# ntc08.net
KiCad netlist of a schematic drawn in EAGLE
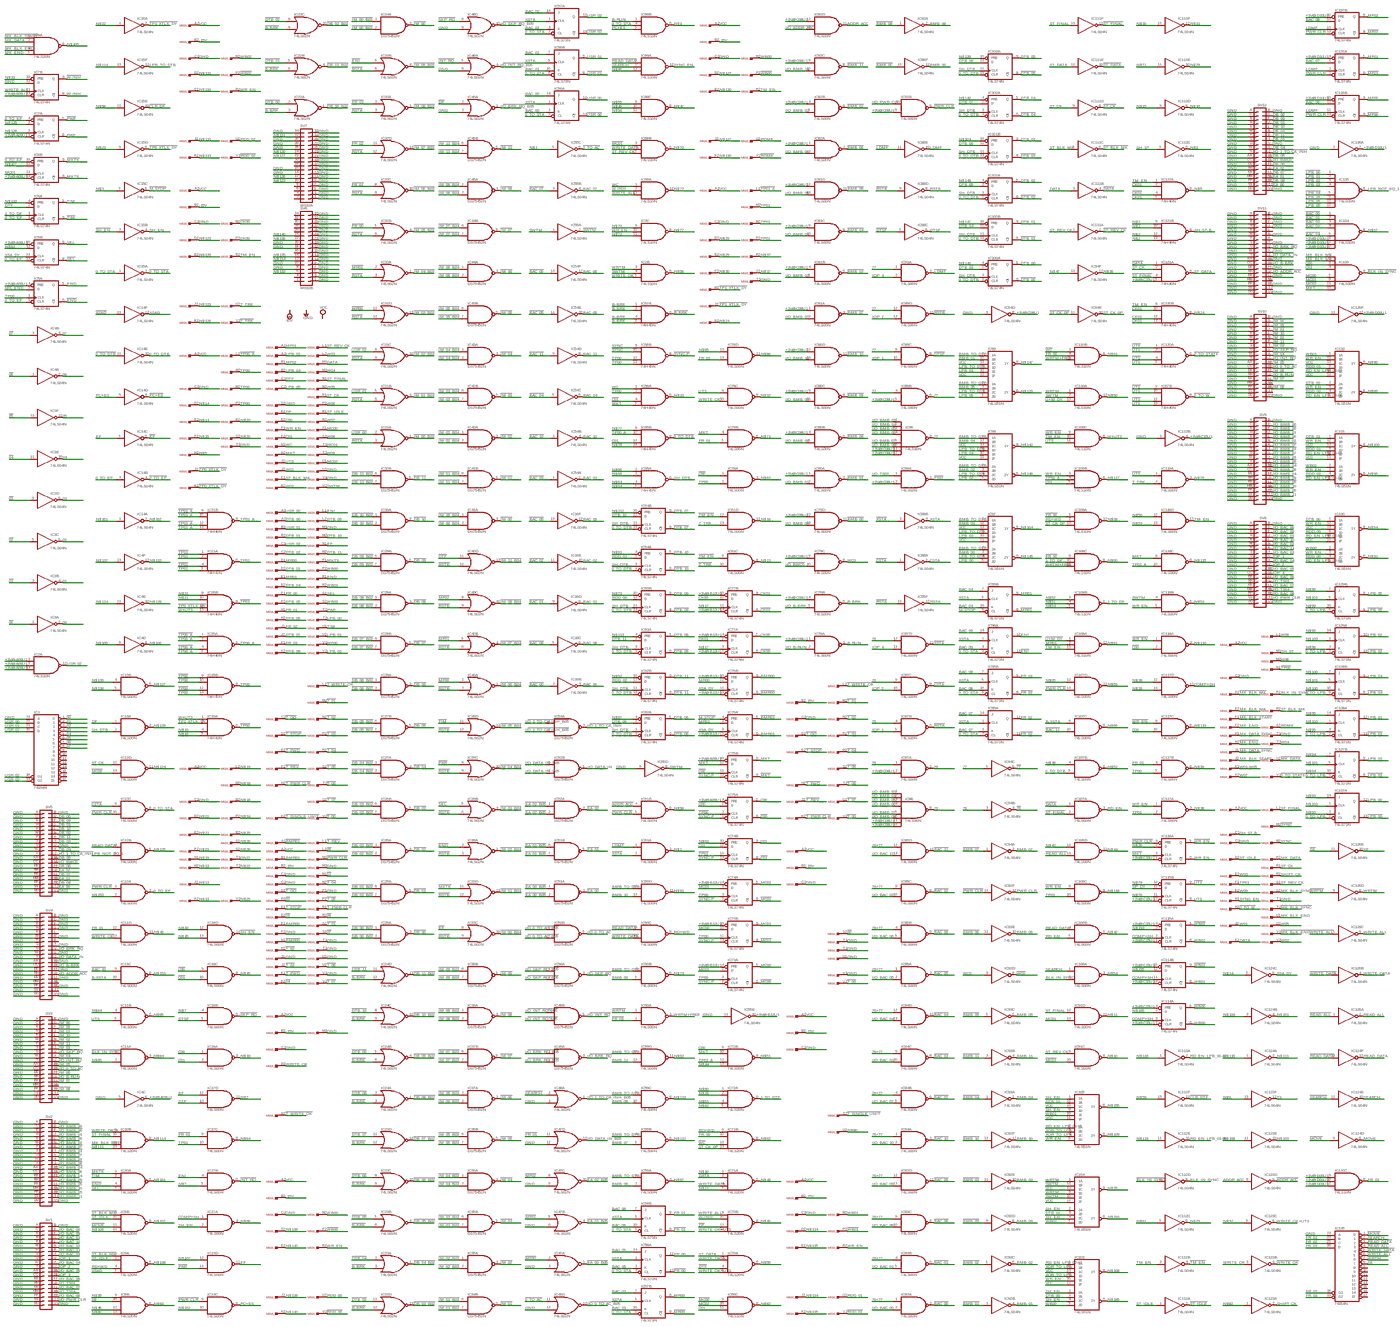
[diagram p0: schematic, sheet 1, overview]
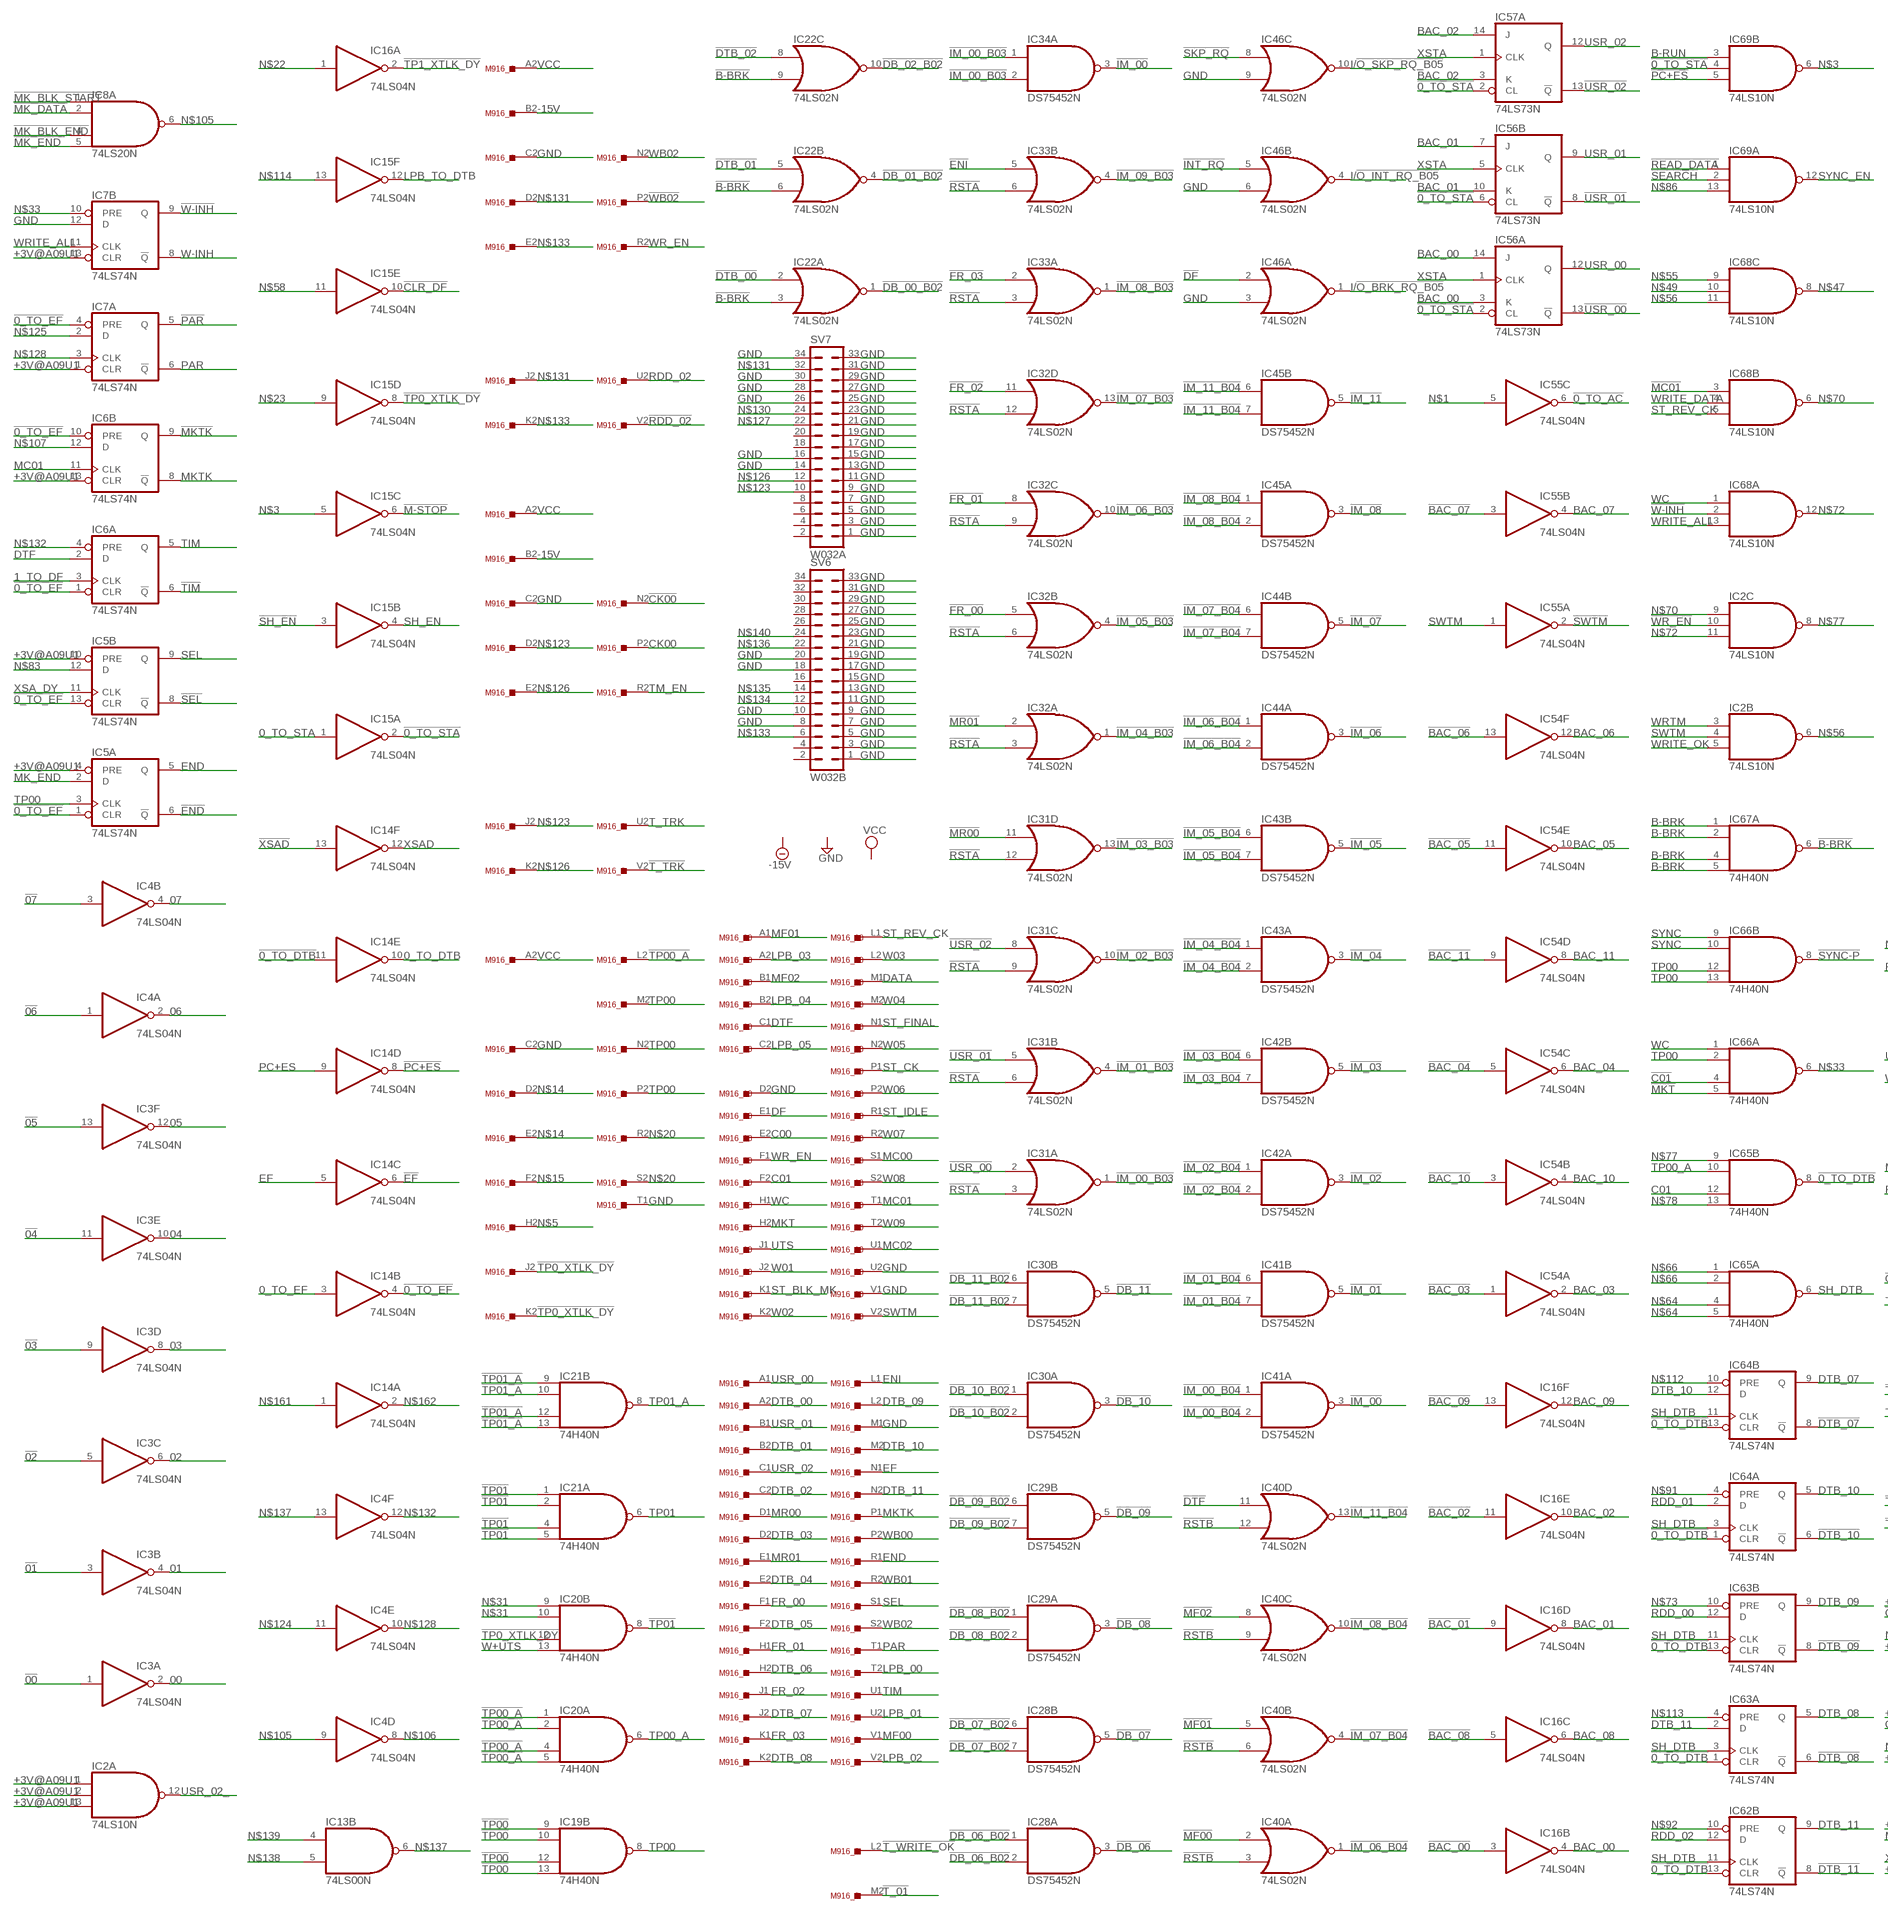
[diagram p1: schematic, sheet 1, part 1 of 4]
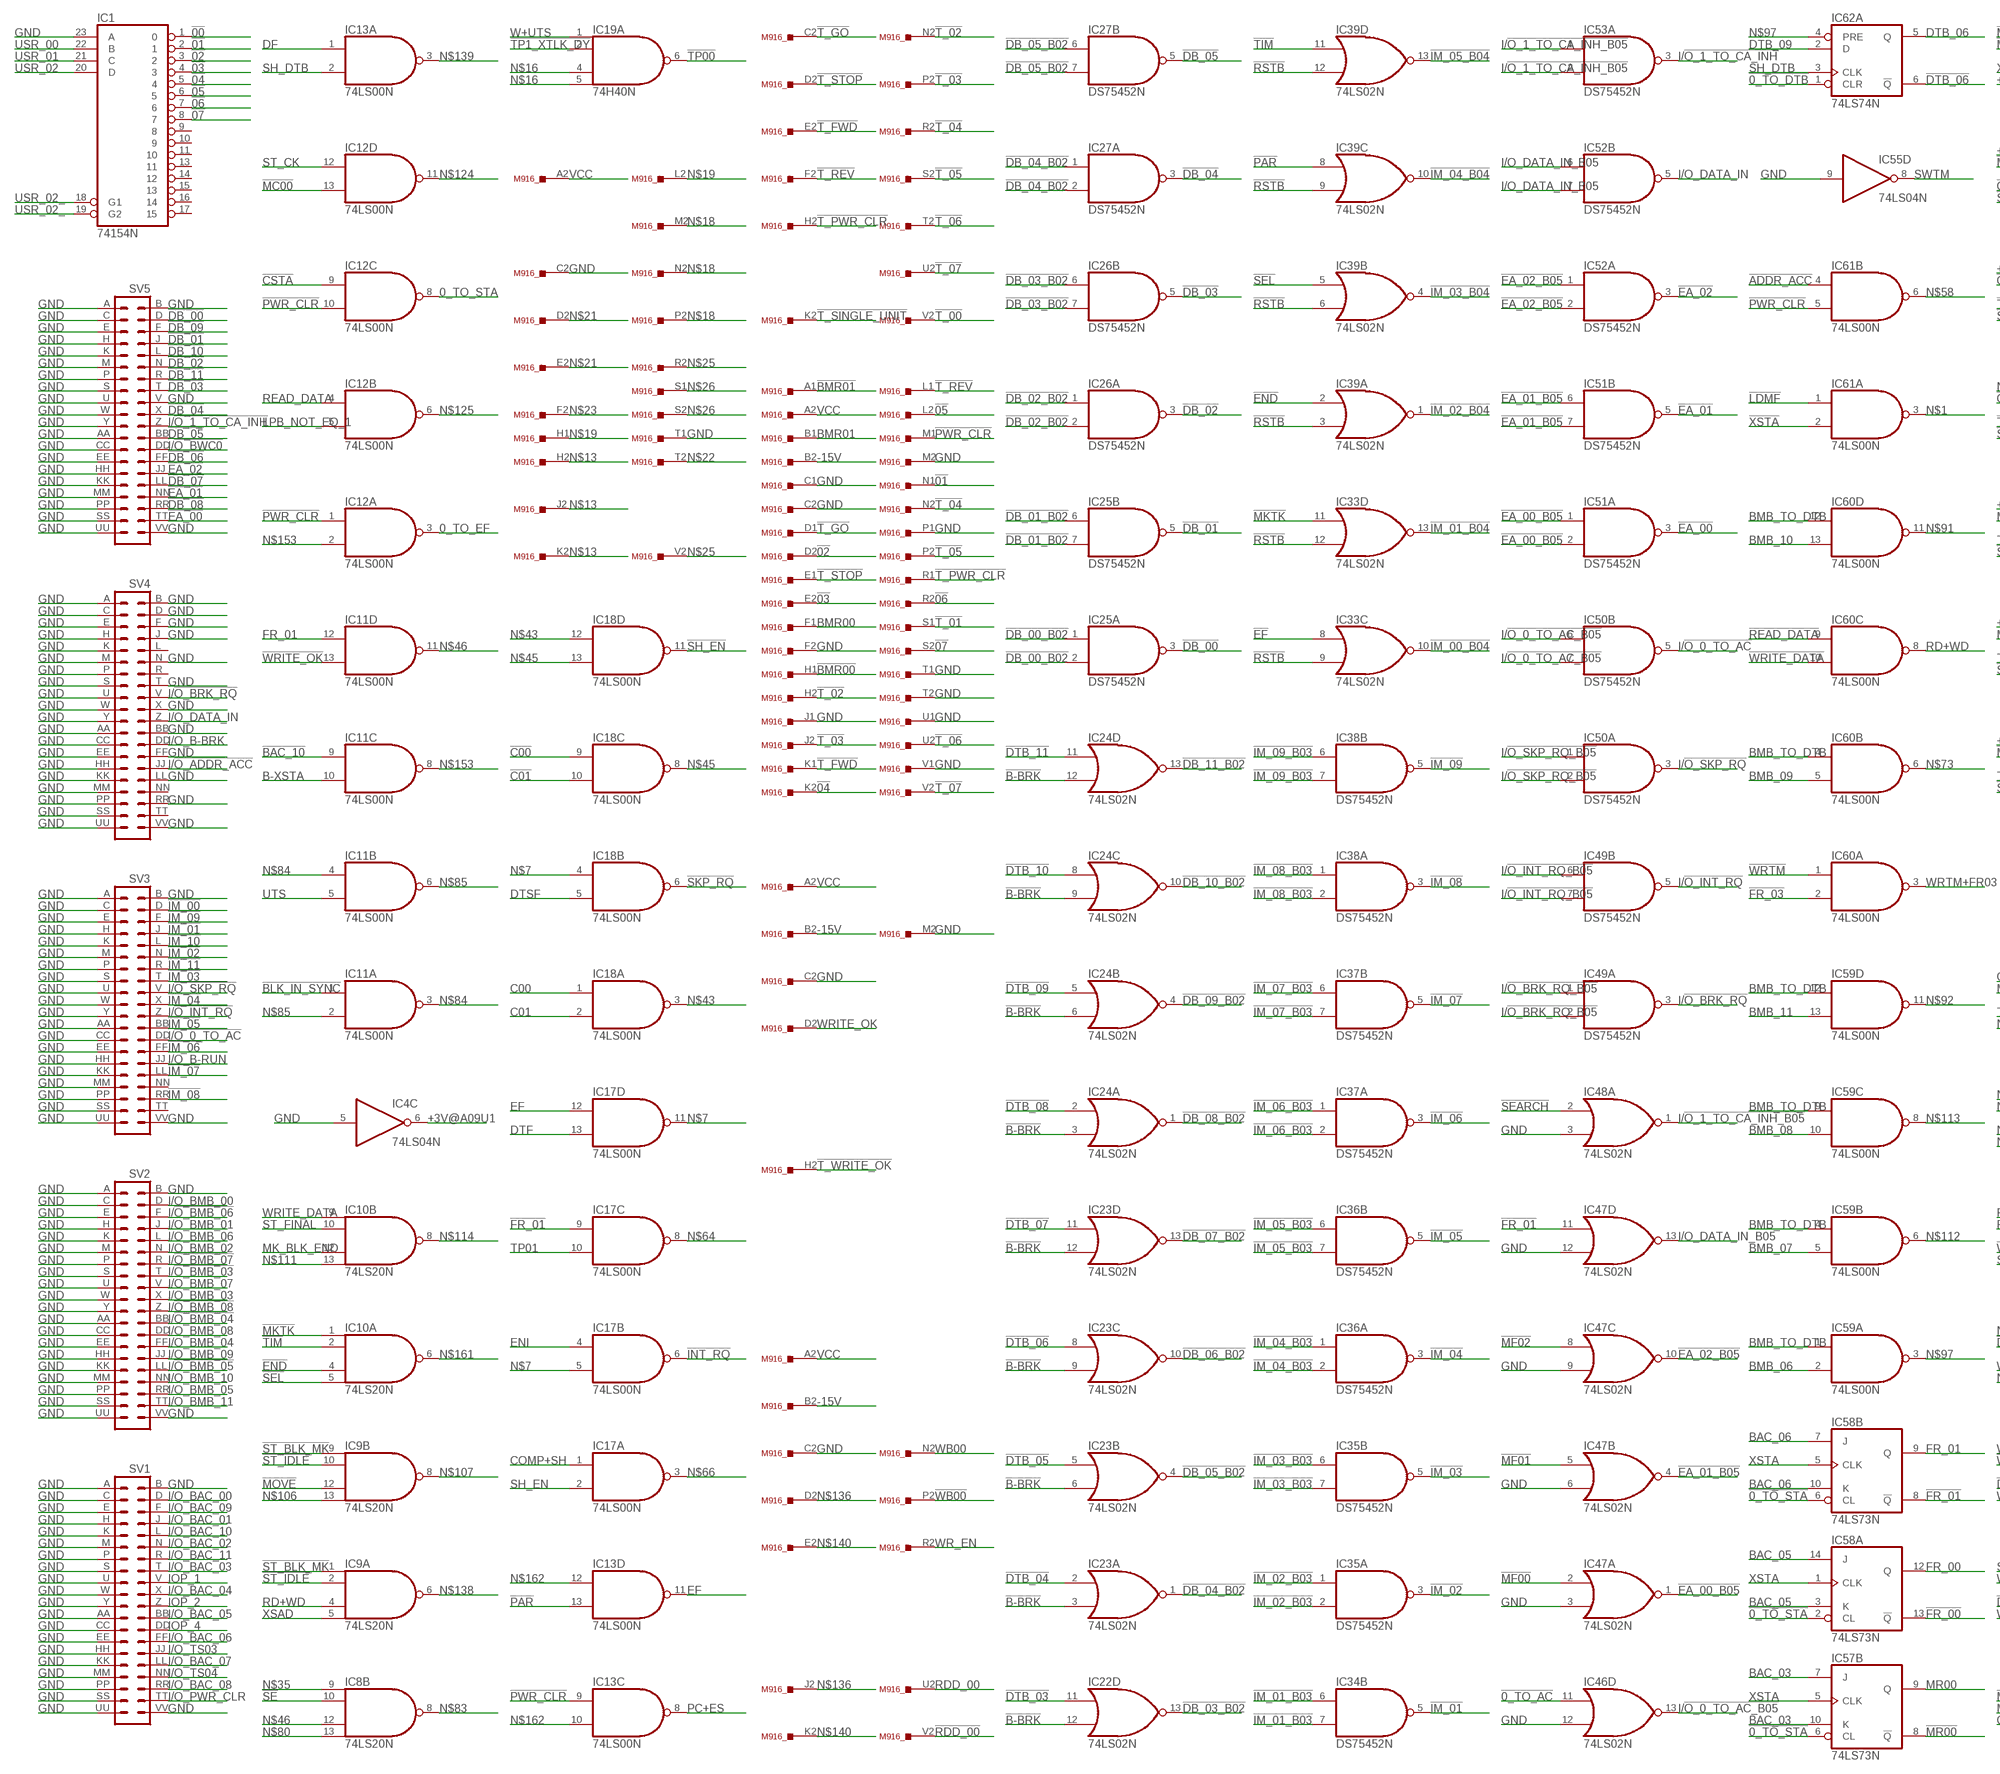
[diagram p2: schematic, sheet 1, part 2 of 4]
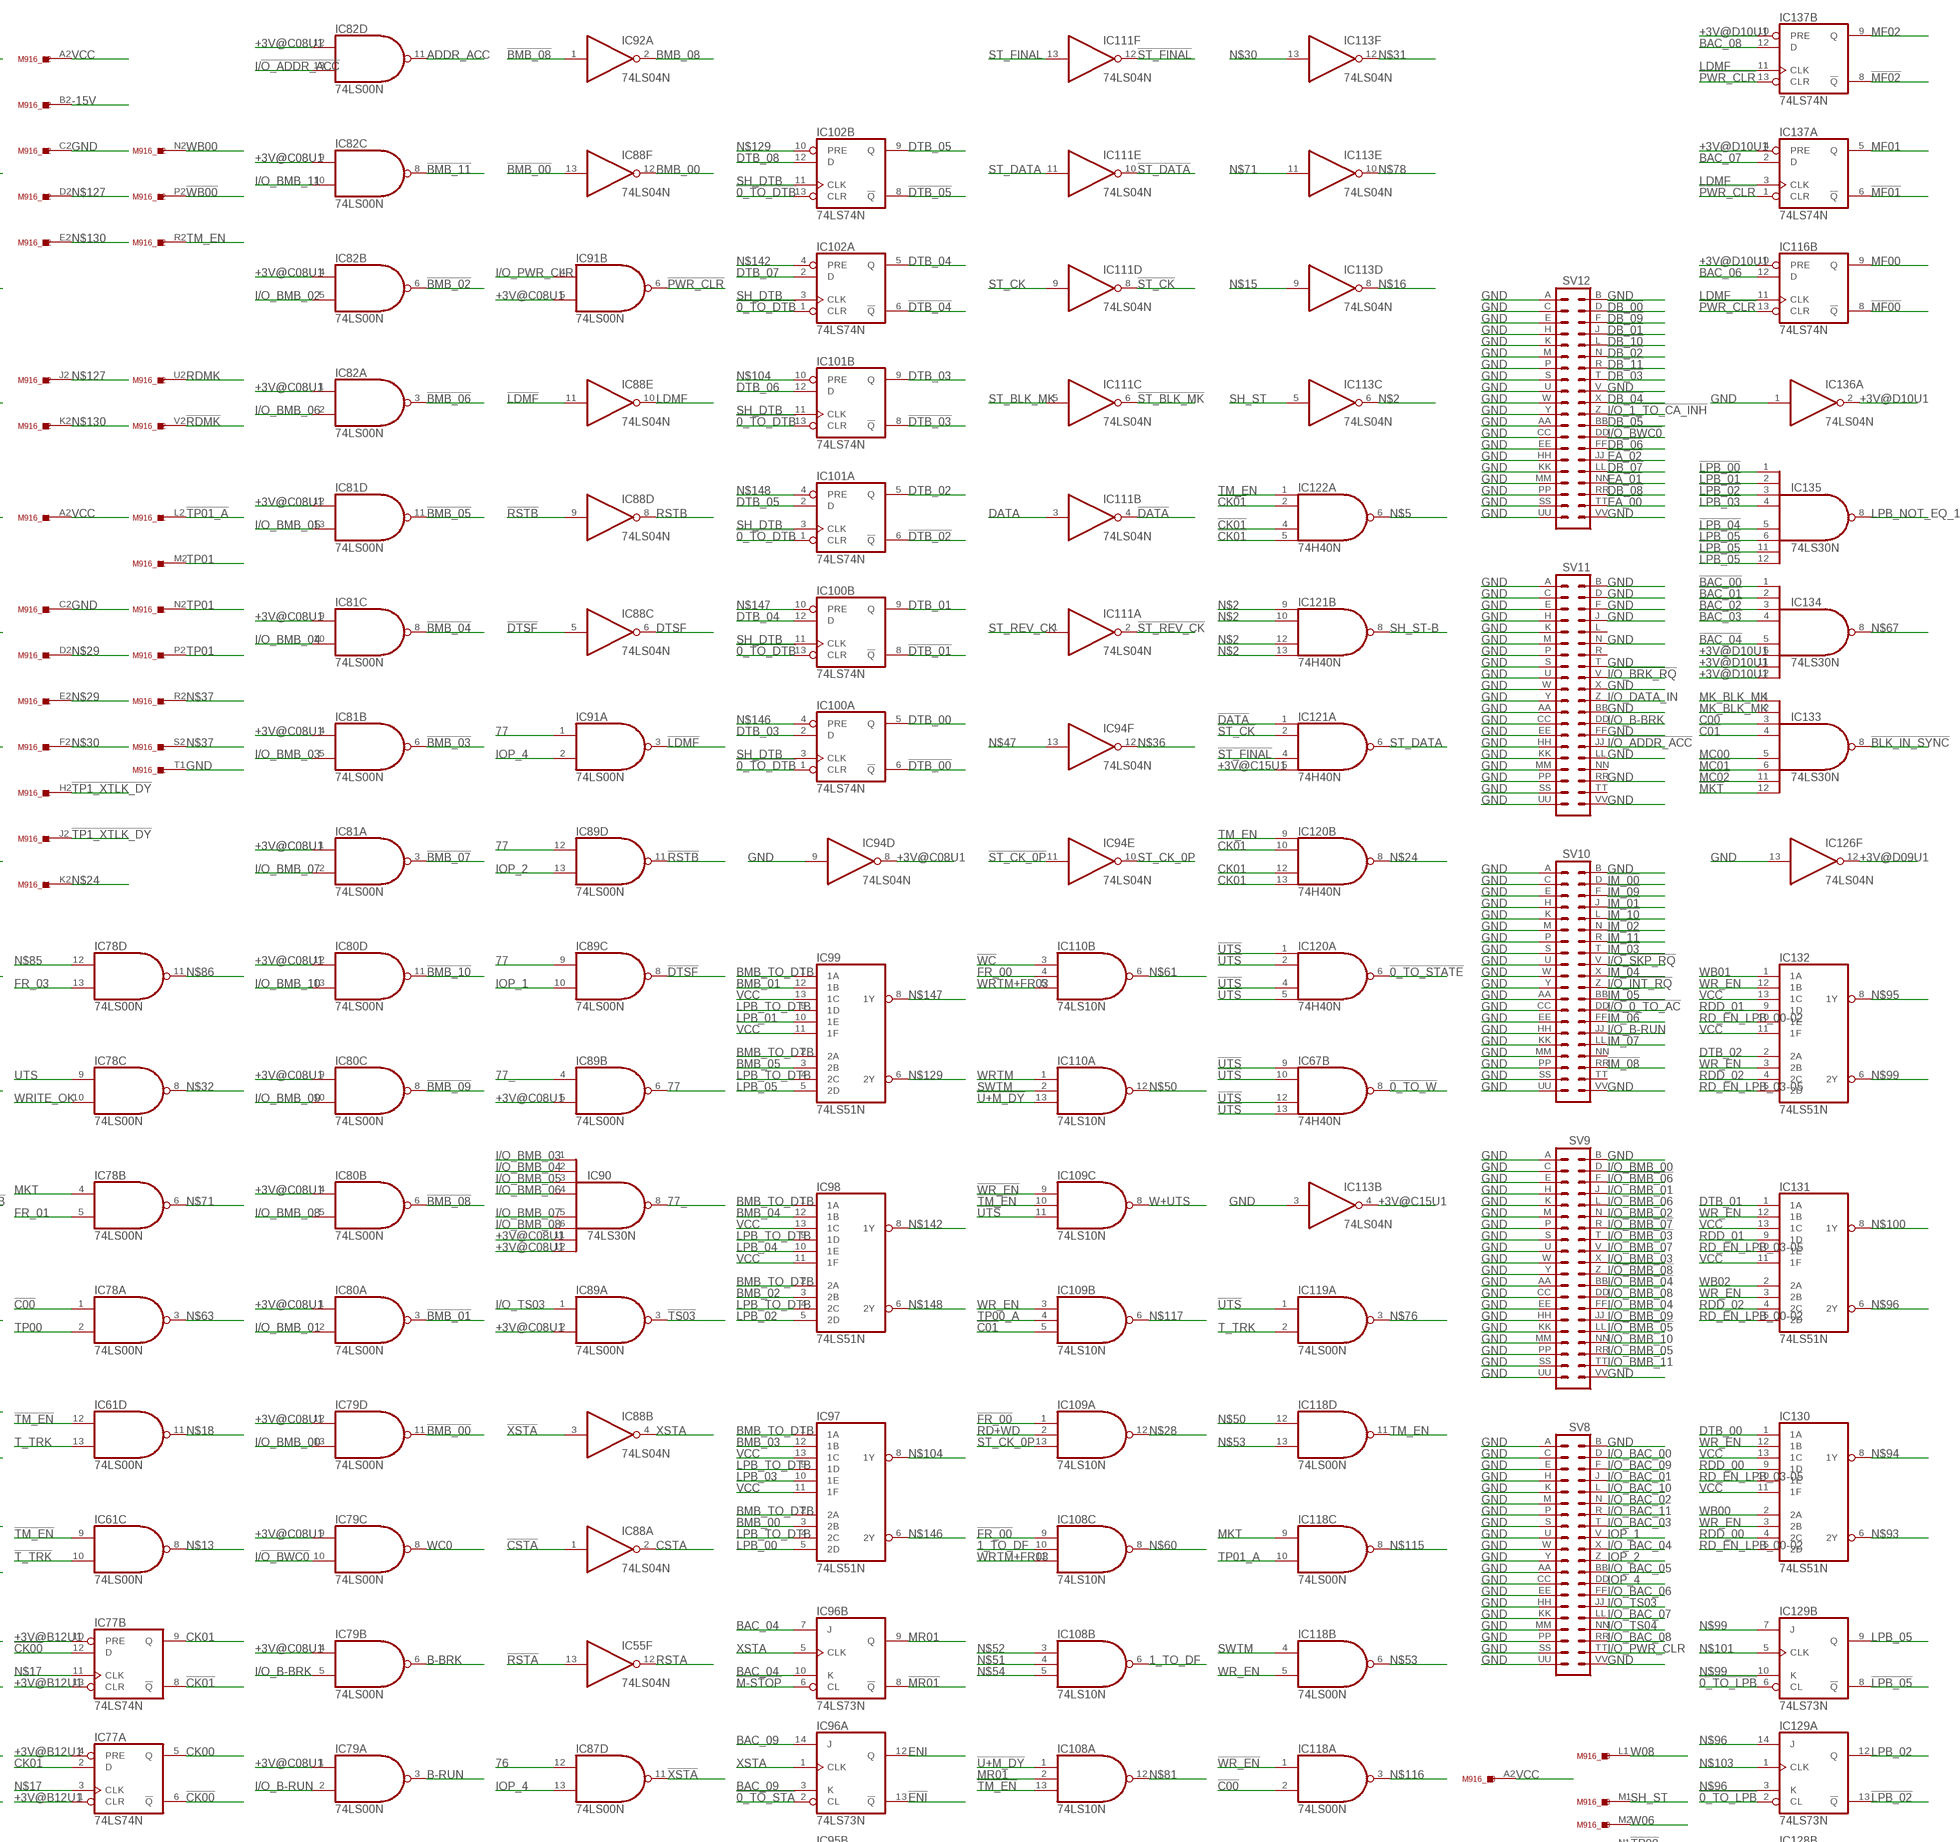
[diagram p3: schematic, sheet 1, part 3 of 4]
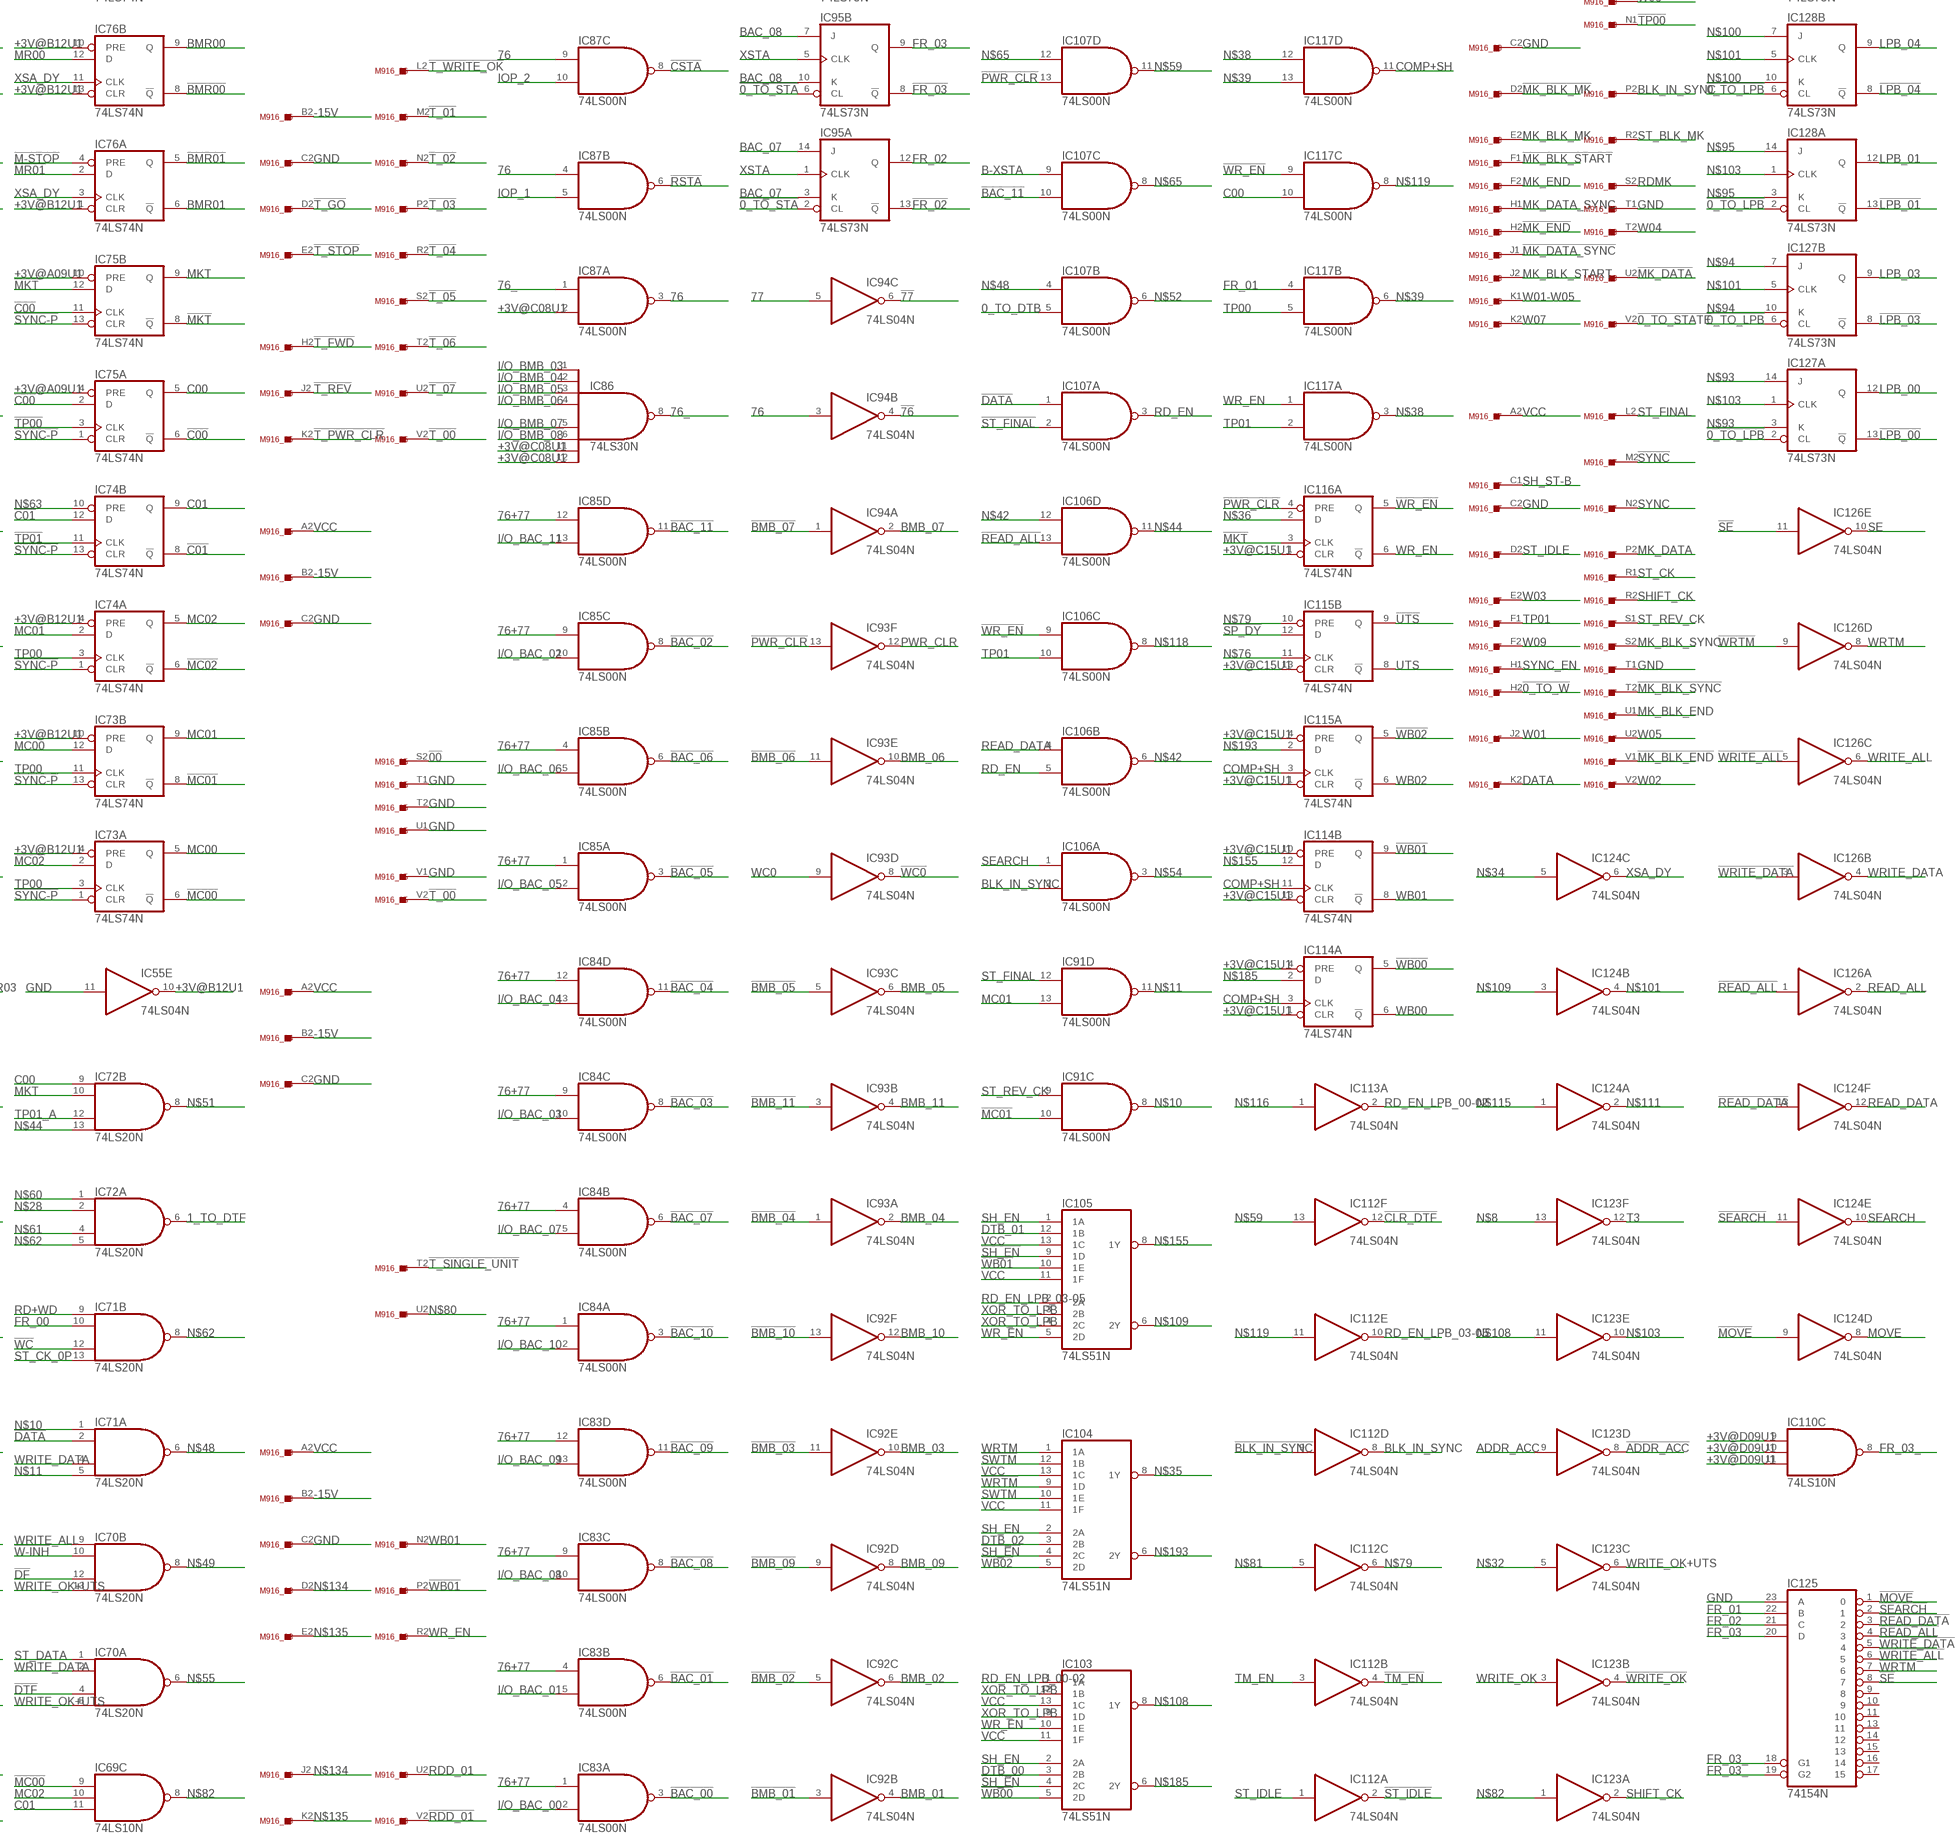
[diagram p4: schematic, sheet 1, part 4 of 4]
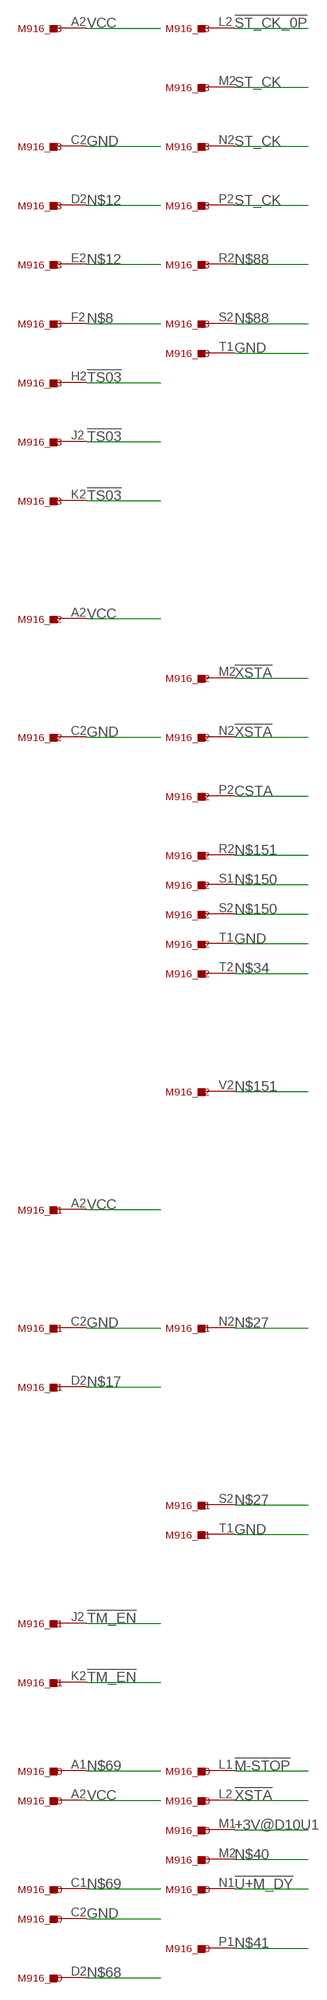
[diagram p5: schematic, sheet 2, part 1 of 2]
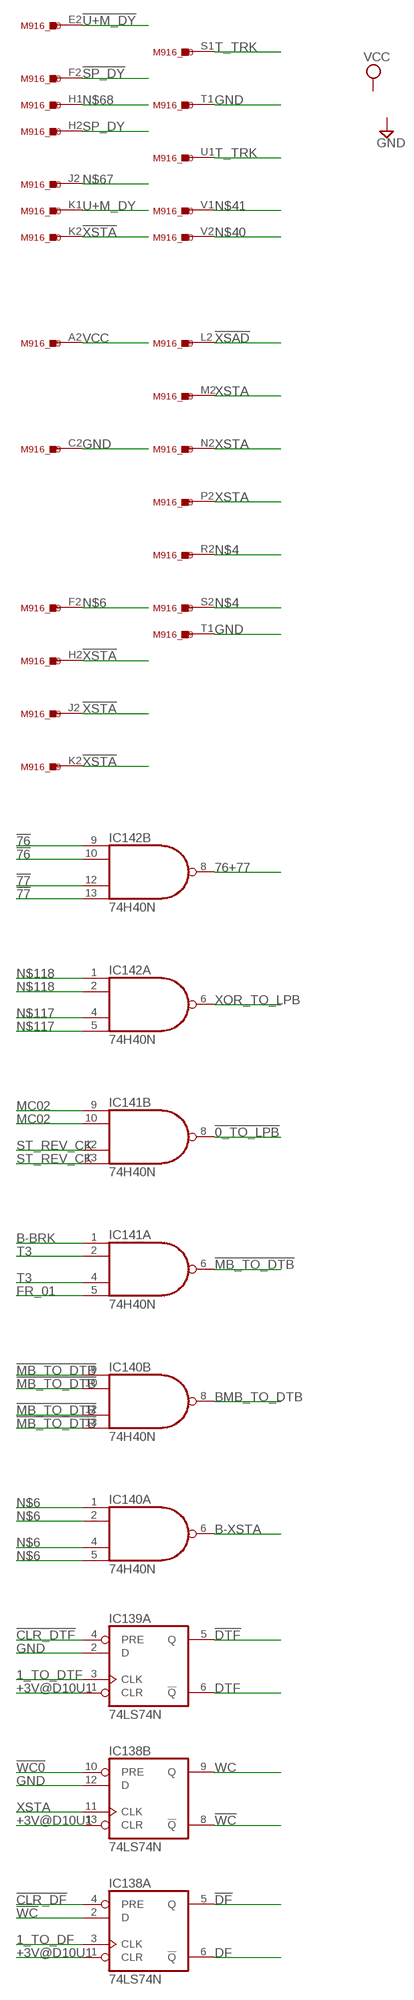
[diagram p6: schematic, sheet 2, part 2 of 2]

(export (version "E")
  (design (tool "Eeschema 10.0.6"))
  (components
    (comp (ref "IC1")
      (value "74154N")
      (footprint "eagle-import:DIL24-6")
      (libsource (lib "eagle-import") (part "74154N"))
    )
    (comp (ref "IC2")
      (value "74LS10N")
      (footprint "eagle-import:DIL14")
      (libsource (lib "eagle-import") (part "7410NLS"))
    )
    (comp (ref "IC3")
      (value "74LS04N")
      (footprint "eagle-import:DIL14")
      (libsource (lib "eagle-import") (part "7404NLS"))
    )
    (comp (ref "IC4")
      (value "74LS04N")
      (footprint "eagle-import:DIL14")
      (libsource (lib "eagle-import") (part "7404NLS"))
    )
    (comp (ref "IC5")
      (value "74LS74N")
      (footprint "eagle-import:DIL14")
      (libsource (lib "eagle-import") (part "7474NLS"))
    )
    (comp (ref "IC6")
      (value "74LS74N")
      (footprint "eagle-import:DIL14")
      (libsource (lib "eagle-import") (part "7474NLS"))
    )
    (comp (ref "IC7")
      (value "74LS74N")
      (footprint "eagle-import:DIL14")
      (libsource (lib "eagle-import") (part "7474NLS"))
    )
    (comp (ref "IC8")
      (value "74LS20N")
      (footprint "eagle-import:DIL14")
      (libsource (lib "eagle-import") (part "7420NLS"))
    )
    (comp (ref "IC9")
      (value "74LS20N")
      (footprint "eagle-import:DIL14")
      (libsource (lib "eagle-import") (part "7420NLS"))
    )
    (comp (ref "IC10")
      (value "74LS20N")
      (footprint "eagle-import:DIL14")
      (libsource (lib "eagle-import") (part "7420NLS"))
    )
    (comp (ref "IC11")
      (value "74LS00N")
      (footprint "eagle-import:DIL14")
      (libsource (lib "eagle-import") (part "7400NLS"))
    )
    (comp (ref "IC12")
      (value "74LS00N")
      (footprint "eagle-import:DIL14")
      (libsource (lib "eagle-import") (part "7400NLS"))
    )
    (comp (ref "IC13")
      (value "74LS00N")
      (footprint "eagle-import:DIL14")
      (libsource (lib "eagle-import") (part "7400NLS"))
    )
    (comp (ref "IC14")
      (value "74LS04N")
      (footprint "eagle-import:DIL14")
      (libsource (lib "eagle-import") (part "7404NLS"))
    )
    (comp (ref "IC15")
      (value "74LS04N")
      (footprint "eagle-import:DIL14")
      (libsource (lib "eagle-import") (part "7404NLS"))
    )
    (comp (ref "IC16")
      (value "74LS04N")
      (footprint "eagle-import:DIL14")
      (libsource (lib "eagle-import") (part "7404NLS"))
    )
    (comp (ref "IC17")
      (value "74LS00N")
      (footprint "eagle-import:DIL14")
      (libsource (lib "eagle-import") (part "7400NLS"))
    )
    (comp (ref "IC18")
      (value "74LS00N")
      (footprint "eagle-import:DIL14")
      (libsource (lib "eagle-import") (part "7400NLS"))
    )
    (comp (ref "IC19")
      (value "74H40N")
      (footprint "eagle-import:DIL14")
      (libsource (lib "eagle-import") (part "7420NS"))
    )
    (comp (ref "IC20")
      (value "74H40N")
      (footprint "eagle-import:DIL14")
      (libsource (lib "eagle-import") (part "7420NS"))
    )
    (comp (ref "IC21")
      (value "74H40N")
      (footprint "eagle-import:DIL14")
      (libsource (lib "eagle-import") (part "7420NS"))
    )
    (comp (ref "IC22")
      (value "74LS02N")
      (footprint "eagle-import:DIL14")
      (libsource (lib "eagle-import") (part "7402NLS"))
    )
    (comp (ref "IC23")
      (value "74LS02N")
      (footprint "eagle-import:DIL14")
      (libsource (lib "eagle-import") (part "7402NLS"))
    )
    (comp (ref "IC24")
      (value "74LS02N")
      (footprint "eagle-import:DIL14")
      (libsource (lib "eagle-import") (part "7402NLS"))
    )
    (comp (ref "IC25")
      (value "DS75452N")
      (footprint "eagle-import:DIL08")
      (libsource (lib "eagle-import") (part "DS75452N"))
    )
    (comp (ref "IC26")
      (value "DS75452N")
      (footprint "eagle-import:DIL08")
      (libsource (lib "eagle-import") (part "DS75452N"))
    )
    (comp (ref "IC27")
      (value "DS75452N")
      (footprint "eagle-import:DIL08")
      (libsource (lib "eagle-import") (part "DS75452N"))
    )
    (comp (ref "IC28")
      (value "DS75452N")
      (footprint "eagle-import:DIL08")
      (libsource (lib "eagle-import") (part "DS75452N"))
    )
    (comp (ref "IC29")
      (value "DS75452N")
      (footprint "eagle-import:DIL08")
      (libsource (lib "eagle-import") (part "DS75452N"))
    )
    (comp (ref "IC30")
      (value "DS75452N")
      (footprint "eagle-import:DIL08")
      (libsource (lib "eagle-import") (part "DS75452N"))
    )
    (comp (ref "IC31")
      (value "74LS02N")
      (footprint "eagle-import:DIL14")
      (libsource (lib "eagle-import") (part "7402NLS"))
    )
    (comp (ref "IC32")
      (value "74LS02N")
      (footprint "eagle-import:DIL14")
      (libsource (lib "eagle-import") (part "7402NLS"))
    )
    (comp (ref "IC33")
      (value "74LS02N")
      (footprint "eagle-import:DIL14")
      (libsource (lib "eagle-import") (part "7402NLS"))
    )
    (comp (ref "IC34")
      (value "DS75452N")
      (footprint "eagle-import:DIL08")
      (libsource (lib "eagle-import") (part "DS75452N"))
    )
    (comp (ref "IC35")
      (value "DS75452N")
      (footprint "eagle-import:DIL08")
      (libsource (lib "eagle-import") (part "DS75452N"))
    )
    (comp (ref "IC36")
      (value "DS75452N")
      (footprint "eagle-import:DIL08")
      (libsource (lib "eagle-import") (part "DS75452N"))
    )
    (comp (ref "IC37")
      (value "DS75452N")
      (footprint "eagle-import:DIL08")
      (libsource (lib "eagle-import") (part "DS75452N"))
    )
    (comp (ref "IC38")
      (value "DS75452N")
      (footprint "eagle-import:DIL08")
      (libsource (lib "eagle-import") (part "DS75452N"))
    )
    (comp (ref "IC39")
      (value "74LS02N")
      (footprint "eagle-import:DIL14")
      (libsource (lib "eagle-import") (part "7402NLS"))
    )
    (comp (ref "IC40")
      (value "74LS02N")
      (footprint "eagle-import:DIL14")
      (libsource (lib "eagle-import") (part "7402NLS"))
    )
    (comp (ref "IC41")
      (value "DS75452N")
      (footprint "eagle-import:DIL08")
      (libsource (lib "eagle-import") (part "DS75452N"))
    )
    (comp (ref "IC42")
      (value "DS75452N")
      (footprint "eagle-import:DIL08")
      (libsource (lib "eagle-import") (part "DS75452N"))
    )
    (comp (ref "IC43")
      (value "DS75452N")
      (footprint "eagle-import:DIL08")
      (libsource (lib "eagle-import") (part "DS75452N"))
    )
    (comp (ref "IC44")
      (value "DS75452N")
      (footprint "eagle-import:DIL08")
      (libsource (lib "eagle-import") (part "DS75452N"))
    )
    (comp (ref "IC45")
      (value "DS75452N")
      (footprint "eagle-import:DIL08")
      (libsource (lib "eagle-import") (part "DS75452N"))
    )
    (comp (ref "IC46")
      (value "74LS02N")
      (footprint "eagle-import:DIL14")
      (libsource (lib "eagle-import") (part "7402NLS"))
    )
    (comp (ref "IC47")
      (value "74LS02N")
      (footprint "eagle-import:DIL14")
      (libsource (lib "eagle-import") (part "7402NLS"))
    )
    (comp (ref "IC48")
      (value "74LS02N")
      (footprint "eagle-import:DIL14")
      (libsource (lib "eagle-import") (part "7402NLS"))
    )
    (comp (ref "IC49")
      (value "DS75452N")
      (footprint "eagle-import:DIL08")
      (libsource (lib "eagle-import") (part "DS75452N"))
    )
    (comp (ref "IC50")
      (value "DS75452N")
      (footprint "eagle-import:DIL08")
      (libsource (lib "eagle-import") (part "DS75452N"))
    )
    (comp (ref "IC51")
      (value "DS75452N")
      (footprint "eagle-import:DIL08")
      (libsource (lib "eagle-import") (part "DS75452N"))
    )
    (comp (ref "IC52")
      (value "DS75452N")
      (footprint "eagle-import:DIL08")
      (libsource (lib "eagle-import") (part "DS75452N"))
    )
    (comp (ref "IC53")
      (value "DS75452N")
      (footprint "eagle-import:DIL08")
      (libsource (lib "eagle-import") (part "DS75452N"))
    )
    (comp (ref "IC54")
      (value "74LS04N")
      (footprint "eagle-import:DIL14")
      (libsource (lib "eagle-import") (part "7404NLS"))
    )
    (comp (ref "IC55")
      (value "74LS04N")
      (footprint "eagle-import:DIL14")
      (libsource (lib "eagle-import") (part "7404NLS"))
    )
    (comp (ref "IC56")
      (value "74LS73N")
      (footprint "eagle-import:DIL14")
      (libsource (lib "eagle-import") (part "7473NLS"))
    )
    (comp (ref "IC57")
      (value "74LS73N")
      (footprint "eagle-import:DIL14")
      (libsource (lib "eagle-import") (part "7473NLS"))
    )
    (comp (ref "IC58")
      (value "74LS73N")
      (footprint "eagle-import:DIL14")
      (libsource (lib "eagle-import") (part "7473NLS"))
    )
    (comp (ref "IC59")
      (value "74LS00N")
      (footprint "eagle-import:DIL14")
      (libsource (lib "eagle-import") (part "7400NLS"))
    )
    (comp (ref "IC60")
      (value "74LS00N")
      (footprint "eagle-import:DIL14")
      (libsource (lib "eagle-import") (part "7400NLS"))
    )
    (comp (ref "IC61")
      (value "74LS00N")
      (footprint "eagle-import:DIL14")
      (libsource (lib "eagle-import") (part "7400NLS"))
    )
    (comp (ref "IC62")
      (value "74LS74N")
      (footprint "eagle-import:DIL14")
      (libsource (lib "eagle-import") (part "7474NLS"))
    )
    (comp (ref "IC63")
      (value "74LS74N")
      (footprint "eagle-import:DIL14")
      (libsource (lib "eagle-import") (part "7474NLS"))
    )
    (comp (ref "IC64")
      (value "74LS74N")
      (footprint "eagle-import:DIL14")
      (libsource (lib "eagle-import") (part "7474NLS"))
    )
    (comp (ref "IC65")
      (value "74H40N")
      (footprint "eagle-import:DIL14")
      (libsource (lib "eagle-import") (part "7420NS"))
    )
    (comp (ref "IC66")
      (value "74H40N")
      (footprint "eagle-import:DIL14")
      (libsource (lib "eagle-import") (part "7420NS"))
    )
    (comp (ref "IC67")
      (value "74H40N")
      (footprint "eagle-import:DIL14")
      (libsource (lib "eagle-import") (part "7420NS"))
    )
    (comp (ref "IC68")
      (value "74LS10N")
      (footprint "eagle-import:DIL14")
      (libsource (lib "eagle-import") (part "7410NLS"))
    )
    (comp (ref "IC69")
      (value "74LS10N")
      (footprint "eagle-import:DIL14")
      (libsource (lib "eagle-import") (part "7410NLS"))
    )
    (comp (ref "IC70")
      (value "74LS20N")
      (footprint "eagle-import:DIL14")
      (libsource (lib "eagle-import") (part "7420NLS"))
    )
    (comp (ref "IC71")
      (value "74LS20N")
      (footprint "eagle-import:DIL14")
      (libsource (lib "eagle-import") (part "7420NLS"))
    )
    (comp (ref "IC72")
      (value "74LS20N")
      (footprint "eagle-import:DIL14")
      (libsource (lib "eagle-import") (part "7420NLS"))
    )
    (comp (ref "IC73")
      (value "74LS74N")
      (footprint "eagle-import:DIL14")
      (libsource (lib "eagle-import") (part "7474NLS"))
    )
    (comp (ref "IC74")
      (value "74LS74N")
      (footprint "eagle-import:DIL14")
      (libsource (lib "eagle-import") (part "7474NLS"))
    )
    (comp (ref "IC75")
      (value "74LS74N")
      (footprint "eagle-import:DIL14")
      (libsource (lib "eagle-import") (part "7474NLS"))
    )
    (comp (ref "IC76")
      (value "74LS74N")
      (footprint "eagle-import:DIL14")
      (libsource (lib "eagle-import") (part "7474NLS"))
    )
    (comp (ref "IC77")
      (value "74LS74N")
      (footprint "eagle-import:DIL14")
      (libsource (lib "eagle-import") (part "7474NLS"))
    )
    (comp (ref "IC78")
      (value "74LS00N")
      (footprint "eagle-import:DIL14")
      (libsource (lib "eagle-import") (part "7400NLS"))
    )
    (comp (ref "IC79")
      (value "74LS00N")
      (footprint "eagle-import:DIL14")
      (libsource (lib "eagle-import") (part "7400NLS"))
    )
    (comp (ref "IC80")
      (value "74LS00N")
      (footprint "eagle-import:DIL14")
      (libsource (lib "eagle-import") (part "7400NLS"))
    )
    (comp (ref "IC81")
      (value "74LS00N")
      (footprint "eagle-import:DIL14")
      (libsource (lib "eagle-import") (part "7400NLS"))
    )
    (comp (ref "IC82")
      (value "74LS00N")
      (footprint "eagle-import:DIL14")
      (libsource (lib "eagle-import") (part "7400NLS"))
    )
    (comp (ref "IC83")
      (value "74LS00N")
      (footprint "eagle-import:DIL14")
      (libsource (lib "eagle-import") (part "7400NLS"))
    )
    (comp (ref "IC84")
      (value "74LS00N")
      (footprint "eagle-import:DIL14")
      (libsource (lib "eagle-import") (part "7400NLS"))
    )
    (comp (ref "IC85")
      (value "74LS00N")
      (footprint "eagle-import:DIL14")
      (libsource (lib "eagle-import") (part "7400NLS"))
    )
    (comp (ref "IC86")
      (value "74LS30N")
      (footprint "eagle-import:DIL14")
      (libsource (lib "eagle-import") (part "7430NLS"))
    )
    (comp (ref "IC87")
      (value "74LS00N")
      (footprint "eagle-import:DIL14")
      (libsource (lib "eagle-import") (part "7400NLS"))
    )
    (comp (ref "IC88")
      (value "74LS04N")
      (footprint "eagle-import:DIL14")
      (libsource (lib "eagle-import") (part "7404NLS"))
    )
    (comp (ref "IC89")
      (value "74LS00N")
      (footprint "eagle-import:DIL14")
      (libsource (lib "eagle-import") (part "7400NLS"))
    )
    (comp (ref "IC90")
      (value "74LS30N")
      (footprint "eagle-import:DIL14")
      (libsource (lib "eagle-import") (part "7430NLS"))
    )
    (comp (ref "IC91")
      (value "74LS00N")
      (footprint "eagle-import:DIL14")
      (libsource (lib "eagle-import") (part "7400NLS"))
    )
    (comp (ref "IC92")
      (value "74LS04N")
      (footprint "eagle-import:DIL14")
      (libsource (lib "eagle-import") (part "7404NLS"))
    )
    (comp (ref "IC93")
      (value "74LS04N")
      (footprint "eagle-import:DIL14")
      (libsource (lib "eagle-import") (part "7404NLS"))
    )
    (comp (ref "IC94")
      (value "74LS04N")
      (footprint "eagle-import:DIL14")
      (libsource (lib "eagle-import") (part "7404NLS"))
    )
    (comp (ref "IC95")
      (value "74LS73N")
      (footprint "eagle-import:DIL14")
      (libsource (lib "eagle-import") (part "7473NLS"))
    )
    (comp (ref "IC96")
      (value "74LS73N")
      (footprint "eagle-import:DIL14")
      (libsource (lib "eagle-import") (part "7473NLS"))
    )
    (comp (ref "IC97")
      (value "74LS51N")
      (footprint "eagle-import:DIL14")
      (libsource (lib "eagle-import") (part "7451NLS"))
    )
    (comp (ref "IC98")
      (value "74LS51N")
      (footprint "eagle-import:DIL14")
      (libsource (lib "eagle-import") (part "7451NLS"))
    )
    (comp (ref "IC99")
      (value "74LS51N")
      (footprint "eagle-import:DIL14")
      (libsource (lib "eagle-import") (part "7451NLS"))
    )
    (comp (ref "IC100")
      (value "74LS74N")
      (footprint "eagle-import:DIL14")
      (libsource (lib "eagle-import") (part "7474NLS"))
    )
    (comp (ref "IC101")
      (value "74LS74N")
      (footprint "eagle-import:DIL14")
      (libsource (lib "eagle-import") (part "7474NLS"))
    )
    (comp (ref "IC102")
      (value "74LS74N")
      (footprint "eagle-import:DIL14")
      (libsource (lib "eagle-import") (part "7474NLS"))
    )
    (comp (ref "IC103")
      (value "74LS51N")
      (footprint "eagle-import:DIL14")
      (libsource (lib "eagle-import") (part "7451NLS"))
    )
    (comp (ref "IC104")
      (value "74LS51N")
      (footprint "eagle-import:DIL14")
      (libsource (lib "eagle-import") (part "7451NLS"))
    )
    (comp (ref "IC105")
      (value "74LS51N")
      (footprint "eagle-import:DIL14")
      (libsource (lib "eagle-import") (part "7451NLS"))
    )
    (comp (ref "IC106")
      (value "74LS00N")
      (footprint "eagle-import:DIL14")
      (libsource (lib "eagle-import") (part "7400NLS"))
    )
    (comp (ref "IC107")
      (value "74LS00N")
      (footprint "eagle-import:DIL14")
      (libsource (lib "eagle-import") (part "7400NLS"))
    )
    (comp (ref "IC108")
      (value "74LS10N")
      (footprint "eagle-import:DIL14")
      (libsource (lib "eagle-import") (part "7410NLS"))
    )
    (comp (ref "IC109")
      (value "74LS10N")
      (footprint "eagle-import:DIL14")
      (libsource (lib "eagle-import") (part "7410NLS"))
    )
    (comp (ref "IC110")
      (value "74LS10N")
      (footprint "eagle-import:DIL14")
      (libsource (lib "eagle-import") (part "7410NLS"))
    )
    (comp (ref "IC111")
      (value "74LS04N")
      (footprint "eagle-import:DIL14")
      (libsource (lib "eagle-import") (part "7404NLS"))
    )
    (comp (ref "IC112")
      (value "74LS04N")
      (footprint "eagle-import:DIL14")
      (libsource (lib "eagle-import") (part "7404NLS"))
    )
    (comp (ref "IC113")
      (value "74LS04N")
      (footprint "eagle-import:DIL14")
      (libsource (lib "eagle-import") (part "7404NLS"))
    )
    (comp (ref "IC114")
      (value "74LS74N")
      (footprint "eagle-import:DIL14")
      (libsource (lib "eagle-import") (part "7474NLS"))
    )
    (comp (ref "IC115")
      (value "74LS74N")
      (footprint "eagle-import:DIL14")
      (libsource (lib "eagle-import") (part "7474NLS"))
    )
    (comp (ref "IC116")
      (value "74LS74N")
      (footprint "eagle-import:DIL14")
      (libsource (lib "eagle-import") (part "7474NLS"))
    )
    (comp (ref "IC117")
      (value "74LS00N")
      (footprint "eagle-import:DIL14")
      (libsource (lib "eagle-import") (part "7400NLS"))
    )
    (comp (ref "IC118")
      (value "74LS00N")
      (footprint "eagle-import:DIL14")
      (libsource (lib "eagle-import") (part "7400NLS"))
    )
    (comp (ref "IC119")
      (value "74LS00N")
      (footprint "eagle-import:DIL14")
      (libsource (lib "eagle-import") (part "7400NLS"))
    )
    (comp (ref "IC120")
      (value "74H40N")
      (footprint "eagle-import:DIL14")
      (libsource (lib "eagle-import") (part "7420NS"))
    )
    (comp (ref "IC121")
      (value "74H40N")
      (footprint "eagle-import:DIL14")
      (libsource (lib "eagle-import") (part "7420NS"))
    )
    (comp (ref "IC122")
      (value "74H40N")
      (footprint "eagle-import:DIL14")
      (libsource (lib "eagle-import") (part "7420NS"))
    )
    (comp (ref "IC123")
      (value "74LS04N")
      (footprint "eagle-import:DIL14")
      (libsource (lib "eagle-import") (part "7404NLS"))
    )
    (comp (ref "IC124")
      (value "74LS04N")
      (footprint "eagle-import:DIL14")
      (libsource (lib "eagle-import") (part "7404NLS"))
    )
    (comp (ref "IC125")
      (value "74154N")
      (footprint "eagle-import:DIL24-6")
      (libsource (lib "eagle-import") (part "74154N"))
    )
    (comp (ref "IC126")
      (value "74LS04N")
      (footprint "eagle-import:DIL14")
      (libsource (lib "eagle-import") (part "7404NLS"))
    )
    (comp (ref "IC127")
      (value "74LS73N")
      (footprint "eagle-import:DIL14")
      (libsource (lib "eagle-import") (part "7473NLS"))
    )
    (comp (ref "IC128")
      (value "74LS73N")
      (footprint "eagle-import:DIL14")
      (libsource (lib "eagle-import") (part "7473NLS"))
    )
    (comp (ref "IC129")
      (value "74LS73N")
      (footprint "eagle-import:DIL14")
      (libsource (lib "eagle-import") (part "7473NLS"))
    )
    (comp (ref "IC130")
      (value "74LS51N")
      (footprint "eagle-import:DIL14")
      (libsource (lib "eagle-import") (part "7451NLS"))
    )
    (comp (ref "IC131")
      (value "74LS51N")
      (footprint "eagle-import:DIL14")
      (libsource (lib "eagle-import") (part "7451NLS"))
    )
    (comp (ref "IC132")
      (value "74LS51N")
      (footprint "eagle-import:DIL14")
      (libsource (lib "eagle-import") (part "7451NLS"))
    )
    (comp (ref "IC133")
      (value "74LS30N")
      (footprint "eagle-import:DIL14")
      (libsource (lib "eagle-import") (part "7430NLS"))
    )
    (comp (ref "IC134")
      (value "74LS30N")
      (footprint "eagle-import:DIL14")
      (libsource (lib "eagle-import") (part "7430NLS"))
    )
    (comp (ref "IC135")
      (value "74LS30N")
      (footprint "eagle-import:DIL14")
      (libsource (lib "eagle-import") (part "7430NLS"))
    )
    (comp (ref "IC136")
      (value "74LS04N")
      (footprint "eagle-import:DIL14")
      (libsource (lib "eagle-import") (part "7404NLS"))
    )
    (comp (ref "IC137")
      (value "74LS74N")
      (footprint "eagle-import:DIL14")
      (libsource (lib "eagle-import") (part "7474NLS"))
    )
    (comp (ref "M916_1")
      (value "M302")
      (footprint "eagle-import:H807")
      (libsource (lib "eagle-import") (part "M916"))
    )
    (comp (ref "M916_2")
      (value "M602")
      (footprint "eagle-import:H807")
      (libsource (lib "eagle-import") (part "M916"))
    )
    (comp (ref "M916_3")
      (value "G888")
      (footprint "eagle-import:H807")
      (libsource (lib "eagle-import") (part "M916"))
    )
    (comp (ref "M916_4")
      (value "M302")
      (footprint "eagle-import:H807")
      (libsource (lib "eagle-import") (part "M916"))
    )
    (comp (ref "M916_5")
      (value "G888")
      (footprint "eagle-import:H807")
      (libsource (lib "eagle-import") (part "M916"))
    )
    (comp (ref "M916_6")
      (value "G888")
      (footprint "eagle-import:H807")
      (libsource (lib "eagle-import") (part "M916"))
    )
    (comp (ref "M916_7")
      (value "M633")
      (footprint "eagle-import:H807")
      (libsource (lib "eagle-import") (part "M916"))
    )
    (comp (ref "M916_8")
      (value "W023")
      (footprint "eagle-import:H807")
      (libsource (lib "eagle-import") (part "M916"))
    )
    (comp (ref "M916_9")
      (value "M916")
      (footprint "eagle-import:H807")
      (libsource (lib "eagle-import") (part "M916"))
    )
    (comp (ref "M916_10")
      (value "M916")
      (footprint "eagle-import:H807")
      (libsource (lib "eagle-import") (part "M916"))
    )
    (comp (ref "M916_11")
      (value "M602")
      (footprint "eagle-import:H807")
      (libsource (lib "eagle-import") (part "M916"))
    )
    (comp (ref "M916_12")
      (value "G888")
      (footprint "eagle-import:H807")
      (libsource (lib "eagle-import") (part "M916"))
    )
    (comp (ref "M916_13")
      (value "G888")
      (footprint "eagle-import:H807")
      (libsource (lib "eagle-import") (part "M916"))
    )
    (comp (ref "M916_14")
      (value "G879")
      (footprint "eagle-import:H807")
      (libsource (lib "eagle-import") (part "M916"))
    )
    (comp (ref "M916_15")
      (value "M633")
      (footprint "eagle-import:H807")
      (libsource (lib "eagle-import") (part "M916"))
    )
    (comp (ref "M916_16")
      (value "W005")
      (footprint "eagle-import:H807")
      (libsource (lib "eagle-import") (part "M916"))
    )
    (comp (ref "M916_17")
      (value "M228B")
      (footprint "eagle-import:H807")
      (libsource (lib "eagle-import") (part "M916"))
    )
    (comp (ref "M916_18")
      (value "M228A")
      (footprint "eagle-import:H807")
      (libsource (lib "eagle-import") (part "M916"))
    )
    (comp (ref "SV1")
      (value "DEC40PINV")
      (footprint "eagle-import:DEC40PINV")
      (libsource (lib "eagle-import") (part "DEC40PINV"))
    )
    (comp (ref "SV2")
      (value "DEC40PINV")
      (footprint "eagle-import:DEC40PINV")
      (libsource (lib "eagle-import") (part "DEC40PINV"))
    )
    (comp (ref "SV3")
      (value "DEC40PINV")
      (footprint "eagle-import:DEC40PINV")
      (libsource (lib "eagle-import") (part "DEC40PINV"))
    )
    (comp (ref "SV4")
      (value "DEC40PINV")
      (footprint "eagle-import:DEC40PINV")
      (libsource (lib "eagle-import") (part "DEC40PINV"))
    )
    (comp (ref "SV5")
      (value "DEC40PINV")
      (footprint "eagle-import:DEC40PINV")
      (libsource (lib "eagle-import") (part "DEC40PINV"))
    )
    (comp (ref "SV6")
      (value "W032B")
      (footprint "eagle-import:MA17-2")
      (libsource (lib "eagle-import") (part "MA17-2"))
    )
    (comp (ref "SV7")
      (value "W032A")
      (footprint "eagle-import:MA17-2")
      (libsource (lib "eagle-import") (part "MA17-2"))
    )
    (comp (ref "SV8")
      (value "DEC40PINV")
      (footprint "eagle-import:DEC40PINV")
      (libsource (lib "eagle-import") (part "DEC40PINV"))
    )
    (comp (ref "SV9")
      (value "DEC40PINV")
      (footprint "eagle-import:DEC40PINV")
      (libsource (lib "eagle-import") (part "DEC40PINV"))
    )
    (comp (ref "SV10")
      (value "DEC40PINV")
      (footprint "eagle-import:DEC40PINV")
      (libsource (lib "eagle-import") (part "DEC40PINV"))
    )
    (comp (ref "SV11")
      (value "DEC40PINV")
      (footprint "eagle-import:DEC40PINV")
      (libsource (lib "eagle-import") (part "DEC40PINV"))
    )
    (comp (ref "SV12")
      (value "DEC40PINV")
      (footprint "eagle-import:DEC40PINV")
      (libsource (lib "eagle-import") (part "DEC40PINV"))
    )
    (comp (ref "IC138")
      (value "74LS74N")
      (footprint "eagle-import:DIL14")
      (libsource (lib "eagle-import") (part "7474NLS"))
    )
    (comp (ref "IC139")
      (value "74LS74N")
      (footprint "eagle-import:DIL14")
      (libsource (lib "eagle-import") (part "7474NLS"))
    )
    (comp (ref "IC140")
      (value "74H40N")
      (footprint "eagle-import:DIL14")
      (libsource (lib "eagle-import") (part "7420NS"))
    )
    (comp (ref "IC141")
      (value "74H40N")
      (footprint "eagle-import:DIL14")
      (libsource (lib "eagle-import") (part "7420NS"))
    )
    (comp (ref "IC142")
      (value "74H40N")
      (footprint "eagle-import:DIL14")
      (libsource (lib "eagle-import") (part "7420NS"))
    )
    (comp (ref "M916_19")
      (value "M602")
      (footprint "eagle-import:H807")
      (libsource (lib "eagle-import") (part "M916"))
    )
    (comp (ref "M916_20")
      (value "M307")
      (footprint "eagle-import:H807")
      (libsource (lib "eagle-import") (part "M916"))
    )
    (comp (ref "M916_21")
      (value "M401")
      (footprint "eagle-import:H807")
      (libsource (lib "eagle-import") (part "M916"))
    )
    (comp (ref "M916_22")
      (value "M302")
      (footprint "eagle-import:H807")
      (libsource (lib "eagle-import") (part "M916"))
    )
    (comp (ref "M916_23")
      (value "M602")
      (footprint "eagle-import:H807")
      (libsource (lib "eagle-import") (part "M916"))
    )
  )
  (nets
    (net (code "1") (name "+3V@A09U1") (class "Default")
      (node (ref "IC2") (pin "1") (pinfunction "I0_1") (pintype "input"))
      (node (ref "IC2") (pin "13") (pinfunction "I2_13") (pintype "input"))
      (node (ref "IC2") (pin "2") (pinfunction "I1_2") (pintype "input"))
      (node (ref "IC4") (pin "6") (pinfunction "O_6") (pintype "output"))
      (node (ref "IC5") (pin "10") (pinfunction "PRE_10") (pintype "input"))
      (node (ref "IC5") (pin "4") (pinfunction "PRE_4") (pintype "input"))
      (node (ref "IC6") (pin "13") (pinfunction "CLR_13") (pintype "input"))
      (node (ref "IC7") (pin "1") (pinfunction "CLR_1") (pintype "input"))
      (node (ref "IC7") (pin "13") (pinfunction "CLR_13") (pintype "input"))
      (node (ref "IC75") (pin "10") (pinfunction "PRE_10") (pintype "input"))
      (node (ref "IC75") (pin "4") (pinfunction "PRE_4") (pintype "input"))
    )
    (net (code "2") (name "+3V@B12U1") (class "Default")
      (node (ref "IC55") (pin "10") (pinfunction "O_10") (pintype "output"))
      (node (ref "IC73") (pin "10") (pinfunction "PRE_10") (pintype "input"))
      (node (ref "IC73") (pin "4") (pinfunction "PRE_4") (pintype "input"))
      (node (ref "IC74") (pin "4") (pinfunction "PRE_4") (pintype "input"))
      (node (ref "IC76") (pin "1") (pinfunction "CLR_1") (pintype "input"))
      (node (ref "IC76") (pin "10") (pinfunction "PRE_10") (pintype "input"))
      (node (ref "IC76") (pin "13") (pinfunction "CLR_13") (pintype "input"))
      (node (ref "IC77") (pin "1") (pinfunction "CLR_1") (pintype "input"))
      (node (ref "IC77") (pin "10") (pinfunction "PRE_10") (pintype "input"))
      (node (ref "IC77") (pin "13") (pinfunction "CLR_13") (pintype "input"))
      (node (ref "IC77") (pin "4") (pinfunction "PRE_4") (pintype "input"))
    )
    (net (code "3") (name "+3V@C08U1") (class "Default")
      (node (ref "IC79") (pin "1") (pinfunction "I0_1") (pintype "input"))
      (node (ref "IC79") (pin "12") (pinfunction "I0_12") (pintype "input"))
      (node (ref "IC79") (pin "4") (pinfunction "I0_4") (pintype "input"))
      (node (ref "IC79") (pin "9") (pinfunction "I0_9") (pintype "input"))
      (node (ref "IC80") (pin "1") (pinfunction "I0_1") (pintype "input"))
      (node (ref "IC80") (pin "12") (pinfunction "I0_12") (pintype "input"))
      (node (ref "IC80") (pin "4") (pinfunction "I0_4") (pintype "input"))
      (node (ref "IC80") (pin "9") (pinfunction "I0_9") (pintype "input"))
      (node (ref "IC81") (pin "1") (pinfunction "I0_1") (pintype "input"))
      (node (ref "IC81") (pin "12") (pinfunction "I0_12") (pintype "input"))
      (node (ref "IC81") (pin "4") (pinfunction "I0_4") (pintype "input"))
      (node (ref "IC81") (pin "9") (pinfunction "I0_9") (pintype "input"))
      (node (ref "IC82") (pin "1") (pinfunction "I0_1") (pintype "input"))
      (node (ref "IC82") (pin "12") (pinfunction "I0_12") (pintype "input"))
      (node (ref "IC82") (pin "4") (pinfunction "I0_4") (pintype "input"))
      (node (ref "IC82") (pin "9") (pinfunction "I0_9") (pintype "input"))
      (node (ref "IC86") (pin "11") (pinfunction "I6_11") (pintype "input"))
      (node (ref "IC86") (pin "12") (pinfunction "I7_12") (pintype "input"))
      (node (ref "IC87") (pin "2") (pinfunction "I1_2") (pintype "input"))
      (node (ref "IC89") (pin "2") (pinfunction "I1_2") (pintype "input"))
      (node (ref "IC89") (pin "5") (pinfunction "I1_5") (pintype "input"))
      (node (ref "IC90") (pin "11") (pinfunction "I6_11") (pintype "input"))
      (node (ref "IC90") (pin "12") (pinfunction "I7_12") (pintype "input"))
      (node (ref "IC91") (pin "5") (pinfunction "I1_5") (pintype "input"))
      (node (ref "IC94") (pin "8") (pinfunction "O_8") (pintype "output"))
    )
    (net (code "4") (name "+3V@C15U1") (class "Default")
      (node (ref "IC113") (pin "4") (pinfunction "O_4") (pintype "output"))
      (node (ref "IC114") (pin "1") (pinfunction "CLR_1") (pintype "input"))
      (node (ref "IC114") (pin "10") (pinfunction "PRE_10") (pintype "input"))
      (node (ref "IC114") (pin "13") (pinfunction "CLR_13") (pintype "input"))
      (node (ref "IC114") (pin "4") (pinfunction "PRE_4") (pintype "input"))
      (node (ref "IC115") (pin "1") (pinfunction "CLR_1") (pintype "input"))
      (node (ref "IC115") (pin "13") (pinfunction "CLR_13") (pintype "input"))
      (node (ref "IC115") (pin "4") (pinfunction "PRE_4") (pintype "input"))
      (node (ref "IC116") (pin "1") (pinfunction "CLR_1") (pintype "input"))
      (node (ref "IC121") (pin "5") (pinfunction "I3_5") (pintype "input"))
    )
    (net (code "5") (name "+3V@D09U1") (class "Default")
      (node (ref "IC110") (pin "10") (pinfunction "I1_10") (pintype "input"))
      (node (ref "IC110") (pin "11") (pinfunction "I2_11") (pintype "input"))
      (node (ref "IC110") (pin "9") (pinfunction "I0_9") (pintype "input"))
      (node (ref "IC126") (pin "12") (pinfunction "O_12") (pintype "output"))
    )
    (net (code "6") (name "+3V@D10U1") (class "Default")
      (node (ref "IC116") (pin "10") (pinfunction "PRE_10") (pintype "input"))
      (node (ref "IC134") (pin "11") (pinfunction "I6_11") (pintype "input"))
      (node (ref "IC134") (pin "12") (pinfunction "I7_12") (pintype "input"))
      (node (ref "IC134") (pin "6") (pinfunction "I5_6") (pintype "input"))
      (node (ref "IC136") (pin "2") (pinfunction "O_2") (pintype "output"))
      (node (ref "IC137") (pin "10") (pinfunction "PRE_10") (pintype "input"))
      (node (ref "IC137") (pin "4") (pinfunction "PRE_4") (pintype "input"))
      (node (ref "IC138") (pin "1") (pinfunction "CLR_1") (pintype "input"))
      (node (ref "IC138") (pin "13") (pinfunction "CLR_13") (pintype "input"))
      (node (ref "IC139") (pin "1") (pinfunction "CLR_1") (pintype "input"))
      (node (ref "M916_20") (pin "M1") (pinfunction "P$2_M1") (pintype "bidirectional"))
    )
    (net (code "7") (name "-15V") (class "Default")
      (node (ref "M916_12") (pin "B2") (pinfunction "P$2_B2") (pintype "bidirectional"))
      (node (ref "M916_13") (pin "B2") (pinfunction "P$2_B2") (pintype "bidirectional"))
      (node (ref "M916_14") (pin "B2") (pinfunction "P$2_B2") (pintype "bidirectional"))
      (node (ref "M916_15") (pin "B2") (pinfunction "P$2_B2") (pintype "bidirectional"))
      (node (ref "M916_16") (pin "B2") (pinfunction "P$2_B2") (pintype "bidirectional"))
      (node (ref "M916_3") (pin "B2") (pinfunction "P$2_B2") (pintype "bidirectional"))
      (node (ref "M916_4") (pin "B2") (pinfunction "P$2_B2") (pintype "bidirectional"))
      (node (ref "M916_5") (pin "B2") (pinfunction "P$2_B2") (pintype "bidirectional"))
      (node (ref "M916_6") (pin "B2") (pinfunction "P$2_B2") (pintype "bidirectional"))
      (node (ref "M916_7") (pin "B2") (pinfunction "P$2_B2") (pintype "bidirectional"))
    )
    (net (code "8") (name "00") (class "Default")
      (node (ref "IC3") (pin "2") (pinfunction "O_2") (pintype "output"))
    )
    (net (code "9") (name "0_TO_DTB") (class "Default")
      (node (ref "IC107") (pin "5") (pinfunction "I1_5") (pintype "input"))
      (node (ref "IC14") (pin "10") (pinfunction "O_10") (pintype "output"))
    )
    (net (code "10") (name "0_TO_EF") (class "Default")
      (node (ref "IC12") (pin "3") (pinfunction "O_3") (pintype "output"))
      (node (ref "IC14") (pin "3") (pinfunction "I_3") (pintype "input"))
    )
    (net (code "11") (name "0_TO_STA") (class "Default")
      (node (ref "IC12") (pin "8") (pinfunction "O_8") (pintype "output"))
      (node (ref "IC15") (pin "1") (pinfunction "I_1") (pintype "input"))
    )
    (net (code "12") (name "01") (class "Default")
      (node (ref "IC3") (pin "4") (pinfunction "O_4") (pintype "output"))
    )
    (net (code "13") (name "1_TO_DF") (class "Default")
      (node (ref "IC108") (pin "10") (pinfunction "I1_10") (pintype "input"))
      (node (ref "IC108") (pin "6") (pinfunction "O_6") (pintype "output"))
      (node (ref "IC138") (pin "3") (pinfunction "CLK_3") (pintype "input"))
      (node (ref "IC6") (pin "3") (pinfunction "CLK_3") (pintype "input"))
    )
    (net (code "14") (name "1_TO_DTF") (class "Default")
      (node (ref "IC139") (pin "3") (pinfunction "CLK_3") (pintype "input"))
      (node (ref "IC72") (pin "6") (pinfunction "O_6") (pintype "output"))
    )
    (net (code "15") (name "02") (class "Default")
      (node (ref "IC3") (pin "6") (pinfunction "O_6") (pintype "output"))
    )
    (net (code "16") (name "03") (class "Default")
      (node (ref "IC3") (pin "8") (pinfunction "O_8") (pintype "output"))
    )
    (net (code "17") (name "04") (class "Default")
      (node (ref "IC3") (pin "10") (pinfunction "O_10") (pintype "output"))
    )
    (net (code "18") (name "05") (class "Default")
      (node (ref "IC3") (pin "12") (pinfunction "O_12") (pintype "output"))
    )
    (net (code "19") (name "06") (class "Default")
      (node (ref "IC4") (pin "2") (pinfunction "O_2") (pintype "output"))
    )
    (net (code "20") (name "07") (class "Default")
      (node (ref "IC4") (pin "4") (pinfunction "O_4") (pintype "output"))
    )
    (net (code "21") (name "76") (class "Default")
      (node (ref "IC87") (pin "12") (pinfunction "I0_12") (pintype "input"))
      (node (ref "IC87") (pin "3") (pinfunction "O_3") (pintype "output"))
      (node (ref "IC87") (pin "4") (pinfunction "I0_4") (pintype "input"))
      (node (ref "IC87") (pin "9") (pinfunction "I0_9") (pintype "input"))
      (node (ref "IC94") (pin "3") (pinfunction "I_3") (pintype "input"))
    )
    (net (code "22") (name "76+77") (class "Default")
      (node (ref "IC142") (pin "8") (pinfunction "O_8") (pintype "output"))
      (node (ref "IC83") (pin "1") (pinfunction "I0_1") (pintype "input"))
      (node (ref "IC83") (pin "12") (pinfunction "I0_12") (pintype "input"))
      (node (ref "IC83") (pin "4") (pinfunction "I0_4") (pintype "input"))
      (node (ref "IC83") (pin "9") (pinfunction "I0_9") (pintype "input"))
      (node (ref "IC84") (pin "1") (pinfunction "I0_1") (pintype "input"))
      (node (ref "IC84") (pin "12") (pinfunction "I0_12") (pintype "input"))
      (node (ref "IC84") (pin "4") (pinfunction "I0_4") (pintype "input"))
      (node (ref "IC84") (pin "9") (pinfunction "I0_9") (pintype "input"))
      (node (ref "IC85") (pin "1") (pinfunction "I0_1") (pintype "input"))
      (node (ref "IC85") (pin "12") (pinfunction "I0_12") (pintype "input"))
      (node (ref "IC85") (pin "4") (pinfunction "I0_4") (pintype "input"))
      (node (ref "IC85") (pin "9") (pinfunction "I0_9") (pintype "input"))
    )
    (net (code "23") (name "76_") (class "Default")
      (node (ref "IC86") (pin "8") (pinfunction "O_8") (pintype "output"))
      (node (ref "IC87") (pin "1") (pinfunction "I0_1") (pintype "input"))
    )
    (net (code "24") (name "77") (class "Default")
      (node (ref "IC89") (pin "12") (pinfunction "I0_12") (pintype "input"))
      (node (ref "IC89") (pin "6") (pinfunction "O_6") (pintype "output"))
      (node (ref "IC89") (pin "9") (pinfunction "I0_9") (pintype "input"))
      (node (ref "IC91") (pin "1") (pinfunction "I0_1") (pintype "input"))
      (node (ref "IC94") (pin "5") (pinfunction "I_5") (pintype "input"))
    )
    (net (code "25") (name "77_") (class "Default")
      (node (ref "IC89") (pin "4") (pinfunction "I0_4") (pintype "input"))
      (node (ref "IC90") (pin "8") (pinfunction "O_8") (pintype "output"))
    )
    (net (code "26") (name "ADDR_ACC") (class "Default")
      (node (ref "IC123") (pin "9") (pinfunction "I_9") (pintype "input"))
      (node (ref "IC82") (pin "11") (pinfunction "O_11") (pintype "output"))
    )
    (net (code "27") (name "B-BRK") (class "Default")
      (node (ref "IC141") (pin "1") (pinfunction "I0_1") (pintype "input"))
      (node (ref "IC67") (pin "1") (pinfunction "I0_1") (pintype "input"))
      (node (ref "IC67") (pin "2") (pinfunction "I1_2") (pintype "input"))
      (node (ref "IC67") (pin "4") (pinfunction "I2_4") (pintype "input"))
      (node (ref "IC67") (pin "5") (pinfunction "I3_5") (pintype "input"))
      (node (ref "IC79") (pin "6") (pinfunction "O_6") (pintype "output"))
    )
    (net (code "28") (name "B-RUN") (class "Default")
      (node (ref "IC69") (pin "3") (pinfunction "I0_3") (pintype "input"))
      (node (ref "IC79") (pin "3") (pinfunction "O_3") (pintype "output"))
    )
    (net (code "29") (name "B-XSTA") (class "Default")
      (node (ref "IC107") (pin "9") (pinfunction "I0_9") (pintype "input"))
      (node (ref "IC11") (pin "10") (pinfunction "I1_10") (pintype "input"))
      (node (ref "IC140") (pin "6") (pinfunction "O_6") (pintype "output"))
    )
    (net (code "30") (name "BAC_00") (class "Default")
      (node (ref "IC16") (pin "4") (pinfunction "O_4") (pintype "output"))
      (node (ref "IC56") (pin "14") (pinfunction "J_14") (pintype "input"))
      (node (ref "IC56") (pin "3") (pinfunction "K_3") (pintype "input"))
    )
    (net (code "31") (name "BAC_01") (class "Default")
      (node (ref "IC16") (pin "8") (pinfunction "O_8") (pintype "output"))
      (node (ref "IC56") (pin "10") (pinfunction "K_10") (pintype "input"))
      (node (ref "IC56") (pin "7") (pinfunction "J_7") (pintype "input"))
    )
    (net (code "32") (name "BAC_02") (class "Default")
      (node (ref "IC16") (pin "10") (pinfunction "O_10") (pintype "output"))
      (node (ref "IC57") (pin "14") (pinfunction "J_14") (pintype "input"))
      (node (ref "IC57") (pin "3") (pinfunction "K_3") (pintype "input"))
    )
    (net (code "33") (name "BAC_03") (class "Default")
      (node (ref "IC54") (pin "2") (pinfunction "O_2") (pintype "output"))
      (node (ref "IC57") (pin "10") (pinfunction "K_10") (pintype "input"))
      (node (ref "IC57") (pin "7") (pinfunction "J_7") (pintype "input"))
    )
    (net (code "34") (name "BAC_04") (class "Default")
      (node (ref "IC54") (pin "6") (pinfunction "O_6") (pintype "output"))
      (node (ref "IC96") (pin "10") (pinfunction "K_10") (pintype "input"))
      (node (ref "IC96") (pin "7") (pinfunction "J_7") (pintype "input"))
    )
    (net (code "35") (name "BAC_05") (class "Default")
      (node (ref "IC54") (pin "10") (pinfunction "O_10") (pintype "output"))
      (node (ref "IC58") (pin "14") (pinfunction "J_14") (pintype "input"))
      (node (ref "IC58") (pin "3") (pinfunction "K_3") (pintype "input"))
    )
    (net (code "36") (name "BAC_06") (class "Default")
      (node (ref "IC116") (pin "12") (pinfunction "D_12") (pintype "input"))
      (node (ref "IC54") (pin "12") (pinfunction "O_12") (pintype "output"))
      (node (ref "IC58") (pin "10") (pinfunction "K_10") (pintype "input"))
      (node (ref "IC58") (pin "7") (pinfunction "J_7") (pintype "input"))
    )
    (net (code "37") (name "BAC_07") (class "Default")
      (node (ref "IC137") (pin "2") (pinfunction "D_2") (pintype "input"))
      (node (ref "IC55") (pin "4") (pinfunction "O_4") (pintype "output"))
      (node (ref "IC95") (pin "14") (pinfunction "J_14") (pintype "input"))
      (node (ref "IC95") (pin "3") (pinfunction "K_3") (pintype "input"))
    )
    (net (code "38") (name "BAC_08") (class "Default")
      (node (ref "IC137") (pin "12") (pinfunction "D_12") (pintype "input"))
      (node (ref "IC16") (pin "6") (pinfunction "O_6") (pintype "output"))
      (node (ref "IC95") (pin "10") (pinfunction "K_10") (pintype "input"))
      (node (ref "IC95") (pin "7") (pinfunction "J_7") (pintype "input"))
    )
    (net (code "39") (name "BAC_09") (class "Default")
      (node (ref "IC16") (pin "12") (pinfunction "O_12") (pintype "output"))
      (node (ref "IC96") (pin "14") (pinfunction "J_14") (pintype "input"))
      (node (ref "IC96") (pin "3") (pinfunction "K_3") (pintype "input"))
    )
    (net (code "40") (name "BAC_10") (class "Default")
      (node (ref "IC54") (pin "4") (pinfunction "O_4") (pintype "output"))
    )
    (net (code "41") (name "BAC_11") (class "Default")
      (node (ref "IC54") (pin "8") (pinfunction "O_8") (pintype "output"))
    )
    (net (code "42") (name "BLK_IN_SYNC") (class "Default")
      (node (ref "IC106") (pin "2") (pinfunction "I1_2") (pintype "input"))
      (node (ref "IC112") (pin "8") (pinfunction "O_8") (pintype "output"))
      (node (ref "M916_18") (pin "P2") (pinfunction "P$2_P2") (pintype "bidirectional"))
    )
    (net (code "43") (name "BMB_00") (class "Default")
      (node (ref "IC88") (pin "12") (pinfunction "O_12") (pintype "output"))
      (node (ref "IC97") (pin "3") (pinfunction "2B_3") (pintype "input"))
    )
    (net (code "44") (name "BMB_01") (class "Default")
      (node (ref "IC92") (pin "4") (pinfunction "O_4") (pintype "output"))
      (node (ref "IC99") (pin "12") (pinfunction "1B_12") (pintype "input"))
    )
    (net (code "45") (name "BMB_02") (class "Default")
      (node (ref "IC92") (pin "6") (pinfunction "O_6") (pintype "output"))
      (node (ref "IC98") (pin "3") (pinfunction "2B_3") (pintype "input"))
    )
    (net (code "46") (name "BMB_03") (class "Default")
      (node (ref "IC92") (pin "10") (pinfunction "O_10") (pintype "output"))
      (node (ref "IC97") (pin "12") (pinfunction "1B_12") (pintype "input"))
    )
    (net (code "47") (name "BMB_04") (class "Default")
      (node (ref "IC93") (pin "2") (pinfunction "O_2") (pintype "output"))
      (node (ref "IC98") (pin "12") (pinfunction "1B_12") (pintype "input"))
    )
    (net (code "48") (name "BMB_05") (class "Default")
      (node (ref "IC93") (pin "6") (pinfunction "O_6") (pintype "output"))
      (node (ref "IC99") (pin "3") (pinfunction "2B_3") (pintype "input"))
    )
    (net (code "49") (name "BMB_06") (class "Default")
      (node (ref "IC59") (pin "2") (pinfunction "I1_2") (pintype "input"))
      (node (ref "IC93") (pin "10") (pinfunction "O_10") (pintype "output"))
    )
    (net (code "50") (name "BMB_07") (class "Default")
      (node (ref "IC59") (pin "5") (pinfunction "I1_5") (pintype "input"))
      (node (ref "IC94") (pin "2") (pinfunction "O_2") (pintype "output"))
    )
    (net (code "51") (name "BMB_08") (class "Default")
      (node (ref "IC59") (pin "10") (pinfunction "I1_10") (pintype "input"))
      (node (ref "IC92") (pin "2") (pinfunction "O_2") (pintype "output"))
    )
    (net (code "52") (name "BMB_09") (class "Default")
      (node (ref "IC60") (pin "5") (pinfunction "I1_5") (pintype "input"))
      (node (ref "IC92") (pin "8") (pinfunction "O_8") (pintype "output"))
    )
    (net (code "53") (name "BMB_10") (class "Default")
      (node (ref "IC60") (pin "13") (pinfunction "I1_13") (pintype "input"))
      (node (ref "IC92") (pin "12") (pinfunction "O_12") (pintype "output"))
    )
    (net (code "54") (name "BMB_11") (class "Default")
      (node (ref "IC59") (pin "13") (pinfunction "I1_13") (pintype "input"))
      (node (ref "IC93") (pin "4") (pinfunction "O_4") (pintype "output"))
    )
    (net (code "55") (name "BMB_TO_DTB") (class "Default")
      (node (ref "IC140") (pin "8") (pinfunction "O_8") (pintype "output"))
      (node (ref "IC59") (pin "1") (pinfunction "I0_1") (pintype "input"))
      (node (ref "IC59") (pin "12") (pinfunction "I0_12") (pintype "input"))
      (node (ref "IC59") (pin "4") (pinfunction "I0_4") (pintype "input"))
      (node (ref "IC59") (pin "9") (pinfunction "I0_9") (pintype "input"))
      (node (ref "IC60") (pin "12") (pinfunction "I0_12") (pintype "input"))
      (node (ref "IC60") (pin "4") (pinfunction "I0_4") (pintype "input"))
      (node (ref "IC97") (pin "1") (pinfunction "1A_1") (pintype "input"))
      (node (ref "IC97") (pin "2") (pinfunction "2A_2") (pintype "input"))
      (node (ref "IC98") (pin "1") (pinfunction "1A_1") (pintype "input"))
      (node (ref "IC98") (pin "2") (pinfunction "2A_2") (pintype "input"))
      (node (ref "IC99") (pin "1") (pinfunction "1A_1") (pintype "input"))
      (node (ref "IC99") (pin "2") (pinfunction "2A_2") (pintype "input"))
    )
    (net (code "56") (name "BMR00") (class "Default")
      (node (ref "IC76") (pin "9") (pinfunction "Q_9") (pintype "output"))
      (node (ref "M916_7") (pin "F1") (pinfunction "P$2_F1") (pintype "bidirectional"))
    )
    (net (code "57") (name "BMR01") (class "Default")
      (node (ref "IC76") (pin "6") (pinfunction "~{Q}_6") (pintype "output"))
      (node (ref "M916_7") (pin "B1") (pinfunction "P$2_B1") (pintype "bidirectional"))
    )
    (net (code "58") (name "C00") (class "Default")
      (node (ref "IC117") (pin "10") (pinfunction "I1_10") (pintype "input"))
      (node (ref "IC133") (pin "3") (pinfunction "I2_3") (pintype "input"))
      (node (ref "IC18") (pin "1") (pinfunction "I0_1") (pintype "input"))
      (node (ref "IC72") (pin "9") (pinfunction "I0_9") (pintype "input"))
      (node (ref "IC75") (pin "5") (pinfunction "Q_5") (pintype "output"))
      (node (ref "M916_10") (pin "E2") (pinfunction "P$2_E2") (pintype "bidirectional"))
    )
    (net (code "59") (name "C01") (class "Default")
      (node (ref "IC18") (pin "2") (pinfunction "I1_2") (pintype "input"))
      (node (ref "IC65") (pin "12") (pinfunction "I2_12") (pintype "input"))
      (node (ref "IC69") (pin "11") (pinfunction "I2_11") (pintype "input"))
      (node (ref "IC74") (pin "9") (pinfunction "Q_9") (pintype "output"))
      (node (ref "M916_10") (pin "F2") (pinfunction "P$2_F2") (pintype "bidirectional"))
    )
    (net (code "60") (name "CK00") (class "Default")
      (node (ref "IC77") (pin "5") (pinfunction "Q_5") (pintype "output"))
      (node (ref "M916_3") (pin "P2") (pinfunction "P$2_P2") (pintype "bidirectional"))
    )
    (net (code "61") (name "CK01") (class "Default")
      (node (ref "IC120") (pin "10") (pinfunction "I1_10") (pintype "input"))
      (node (ref "IC120") (pin "12") (pinfunction "I2_12") (pintype "input"))
      (node (ref "IC120") (pin "13") (pinfunction "I3_13") (pintype "input"))
      (node (ref "IC77") (pin "2") (pinfunction "D_2") (pintype "input"))
      (node (ref "IC77") (pin "9") (pinfunction "Q_9") (pintype "output"))
    )
    (net (code "62") (name "COMP+SH") (class "Default")
      (node (ref "IC114") (pin "11") (pinfunction "CLK_11") (pintype "input"))
      (node (ref "IC114") (pin "3") (pinfunction "CLK_3") (pintype "input"))
      (node (ref "IC115") (pin "3") (pinfunction "CLK_3") (pintype "input"))
      (node (ref "IC117") (pin "11") (pinfunction "O_11") (pintype "output"))
      (node (ref "IC17") (pin "1") (pinfunction "I0_1") (pintype "input"))
    )
    (net (code "63") (name "CSTA") (class "Default")
      (node (ref "IC88") (pin "2") (pinfunction "O_2") (pintype "output"))
      (node (ref "M916_22") (pin "P2") (pinfunction "P$2_P2") (pintype "bidirectional"))
    )
    (net (code "64") (name "DATA") (class "Default")
      (node (ref "IC111") (pin "3") (pinfunction "I_3") (pintype "input"))
      (node (ref "M916_10") (pin "M1") (pinfunction "P$2_M1") (pintype "bidirectional"))
      (node (ref "M916_17") (pin "K2") (pinfunction "P$2_K2") (pintype "bidirectional"))
    )
    (net (code "65") (name "DF") (class "Default")
      (node (ref "IC13") (pin "1") (pinfunction "I0_1") (pintype "input"))
      (node (ref "IC138") (pin "6") (pinfunction "~{Q}_6") (pintype "output"))
      (node (ref "M916_10") (pin "E1") (pinfunction "P$2_E1") (pintype "bidirectional"))
    )
    (net (code "66") (name "DTB_00") (class "Default")
      (node (ref "IC100") (pin "5") (pinfunction "Q_5") (pintype "output"))
      (node (ref "IC103") (pin "3") (pinfunction "2B_3") (pintype "input"))
      (node (ref "IC130") (pin "1") (pinfunction "1A_1") (pintype "input"))
      (node (ref "M916_9") (pin "A2") (pinfunction "P$2_A2") (pintype "bidirectional"))
    )
    (net (code "67") (name "DTB_01") (class "Default")
      (node (ref "IC100") (pin "9") (pinfunction "Q_9") (pintype "output"))
      (node (ref "IC105") (pin "12") (pinfunction "1B_12") (pintype "input"))
      (node (ref "IC131") (pin "1") (pinfunction "1A_1") (pintype "input"))
      (node (ref "M916_9") (pin "B2") (pinfunction "P$2_B2") (pintype "bidirectional"))
    )
    (net (code "68") (name "DTB_02") (class "Default")
      (node (ref "IC101") (pin "5") (pinfunction "Q_5") (pintype "output"))
      (node (ref "IC104") (pin "3") (pinfunction "2B_3") (pintype "input"))
      (node (ref "IC132") (pin "2") (pinfunction "2A_2") (pintype "input"))
      (node (ref "M916_9") (pin "C2") (pinfunction "P$2_C2") (pintype "bidirectional"))
    )
    (net (code "69") (name "DTB_03") (class "Default")
      (node (ref "IC100") (pin "2") (pinfunction "D_2") (pintype "input"))
      (node (ref "IC101") (pin "9") (pinfunction "Q_9") (pintype "output"))
      (node (ref "M916_9") (pin "D2") (pinfunction "P$2_D2") (pintype "bidirectional"))
    )
    (net (code "70") (name "DTB_04") (class "Default")
      (node (ref "IC100") (pin "12") (pinfunction "D_12") (pintype "input"))
      (node (ref "IC102") (pin "5") (pinfunction "Q_5") (pintype "output"))
      (node (ref "M916_9") (pin "E2") (pinfunction "P$2_E2") (pintype "bidirectional"))
    )
    (net (code "71") (name "DTB_05") (class "Default")
      (node (ref "IC101") (pin "2") (pinfunction "D_2") (pintype "input"))
      (node (ref "IC102") (pin "9") (pinfunction "Q_9") (pintype "output"))
      (node (ref "M916_9") (pin "F2") (pinfunction "P$2_F2") (pintype "bidirectional"))
    )
    (net (code "72") (name "DTB_06") (class "Default")
      (node (ref "IC101") (pin "12") (pinfunction "D_12") (pintype "input"))
      (node (ref "IC62") (pin "5") (pinfunction "Q_5") (pintype "output"))
      (node (ref "M916_9") (pin "H2") (pinfunction "P$2_H2") (pintype "bidirectional"))
    )
    (net (code "73") (name "DTB_07") (class "Default")
      (node (ref "IC102") (pin "2") (pinfunction "D_2") (pintype "input"))
      (node (ref "IC64") (pin "9") (pinfunction "Q_9") (pintype "output"))
      (node (ref "M916_9") (pin "J2") (pinfunction "P$2_J2") (pintype "bidirectional"))
    )
    (net (code "74") (name "DTB_08") (class "Default")
      (node (ref "IC102") (pin "12") (pinfunction "D_12") (pintype "input"))
      (node (ref "IC63") (pin "5") (pinfunction "Q_5") (pintype "output"))
      (node (ref "M916_9") (pin "K2") (pinfunction "P$2_K2") (pintype "bidirectional"))
    )
    (net (code "75") (name "DTB_09") (class "Default")
      (node (ref "IC62") (pin "2") (pinfunction "D_2") (pintype "input"))
      (node (ref "IC63") (pin "9") (pinfunction "Q_9") (pintype "output"))
      (node (ref "M916_9") (pin "L2") (pinfunction "P$2_L2") (pintype "bidirectional"))
    )
    (net (code "76") (name "DTB_10") (class "Default")
      (node (ref "IC64") (pin "12") (pinfunction "D_12") (pintype "input"))
      (node (ref "IC64") (pin "5") (pinfunction "Q_5") (pintype "output"))
      (node (ref "M916_9") (pin "M2") (pinfunction "P$2_M2") (pintype "bidirectional"))
    )
    (net (code "77") (name "DTB_11") (class "Default")
      (node (ref "IC62") (pin "9") (pinfunction "Q_9") (pintype "output"))
      (node (ref "IC63") (pin "2") (pinfunction "D_2") (pintype "input"))
      (node (ref "M916_9") (pin "N2") (pinfunction "P$2_N2") (pintype "bidirectional"))
    )
    (net (code "78") (name "DTF") (class "Default")
      (node (ref "IC139") (pin "6") (pinfunction "~{Q}_6") (pintype "output"))
      (node (ref "IC17") (pin "13") (pinfunction "I1_13") (pintype "input"))
      (node (ref "IC6") (pin "2") (pinfunction "D_2") (pintype "input"))
      (node (ref "M916_10") (pin "C1") (pinfunction "P$2_C1") (pintype "bidirectional"))
    )
    (net (code "79") (name "DTSF") (class "Default")
      (node (ref "IC18") (pin "5") (pinfunction "I1_5") (pintype "input"))
      (node (ref "IC88") (pin "6") (pinfunction "O_6") (pintype "output"))
    )
    (net (code "80") (name "EF") (class "Default")
      (node (ref "IC13") (pin "11") (pinfunction "O_11") (pintype "output"))
      (node (ref "IC14") (pin "5") (pinfunction "I_5") (pintype "input"))
      (node (ref "IC17") (pin "12") (pinfunction "I0_12") (pintype "input"))
      (node (ref "M916_9") (pin "N1") (pinfunction "P$2_N1") (pintype "bidirectional"))
    )
    (net (code "81") (name "END") (class "Default")
      (node (ref "IC5") (pin "5") (pinfunction "Q_5") (pintype "output"))
      (node (ref "M916_9") (pin "R1") (pinfunction "P$2_R1") (pintype "bidirectional"))
    )
    (net (code "82") (name "ENI") (class "Default")
      (node (ref "IC17") (pin "4") (pinfunction "I0_4") (pintype "input"))
      (node (ref "IC96") (pin "12") (pinfunction "Q_12") (pintype "output"))
      (node (ref "M916_9") (pin "L1") (pinfunction "P$2_L1") (pintype "bidirectional"))
    )
    (net (code "83") (name "FR_00") (class "Default")
      (node (ref "IC110") (pin "4") (pinfunction "I1_4") (pintype "input"))
      (node (ref "IC58") (pin "12") (pinfunction "Q_12") (pintype "output"))
      (node (ref "IC71") (pin "10") (pinfunction "I1_10") (pintype "input"))
      (node (ref "M916_9") (pin "F1") (pinfunction "P$2_F1") (pintype "bidirectional"))
    )
    (net (code "84") (name "FR_01") (class "Default")
      (node (ref "IC11") (pin "12") (pinfunction "I0_12") (pintype "input"))
      (node (ref "IC117") (pin "4") (pinfunction "I0_4") (pintype "input"))
      (node (ref "IC125") (pin "22") (pinfunction "B_22") (pintype "input"))
      (node (ref "IC141") (pin "5") (pinfunction "I3_5") (pintype "input"))
      (node (ref "IC58") (pin "9") (pinfunction "Q_9") (pintype "output"))
      (node (ref "IC78") (pin "5") (pinfunction "I1_5") (pintype "input"))
      (node (ref "M916_9") (pin "H1") (pinfunction "P$2_H1") (pintype "bidirectional"))
    )
    (net (code "85") (name "FR_02") (class "Default")
      (node (ref "IC125") (pin "21") (pinfunction "C_21") (pintype "input"))
      (node (ref "IC95") (pin "12") (pinfunction "Q_12") (pintype "output"))
      (node (ref "M916_9") (pin "J1") (pinfunction "P$2_J1") (pintype "bidirectional"))
    )
    (net (code "86") (name "FR_03") (class "Default")
      (node (ref "IC125") (pin "20") (pinfunction "D_20") (pintype "input"))
      (node (ref "IC78") (pin "13") (pinfunction "I1_13") (pintype "input"))
      (node (ref "IC95") (pin "9") (pinfunction "Q_9") (pintype "output"))
      (node (ref "M916_9") (pin "K1") (pinfunction "P$2_K1") (pintype "bidirectional"))
    )
    (net (code "87") (name "FR_03_") (class "Default")
      (node (ref "IC110") (pin "8") (pinfunction "O_8") (pintype "output"))
      (node (ref "IC125") (pin "18") (pinfunction "G1_18") (pintype "input"))
      (node (ref "IC125") (pin "19") (pinfunction "G2_19") (pintype "input"))
    )
    (net (code "88") (name "GND") (class "Default")
      (node (ref "IC1") (pin "23") (pinfunction "A_23") (pintype "input"))
      (node (ref "IC113") (pin "3") (pinfunction "I_3") (pintype "input"))
      (node (ref "IC125") (pin "23") (pinfunction "A_23") (pintype "input"))
      (node (ref "IC126") (pin "13") (pinfunction "I_13") (pintype "input"))
      (node (ref "IC136") (pin "1") (pinfunction "I_1") (pintype "input"))
      (node (ref "IC138") (pin "12") (pinfunction "D_12") (pintype "input"))
      (node (ref "IC139") (pin "2") (pinfunction "D_2") (pintype "input"))
      (node (ref "IC4") (pin "5") (pinfunction "I_5") (pintype "input"))
      (node (ref "IC46") (pin "12") (pinfunction "I1_12") (pintype "input"))
      (node (ref "IC46") (pin "3") (pinfunction "I1_3") (pintype "input"))
      (node (ref "IC46") (pin "6") (pinfunction "I1_6") (pintype "input"))
      (node (ref "IC46") (pin "9") (pinfunction "I1_9") (pintype "input"))
      (node (ref "IC47") (pin "12") (pinfunction "I1_12") (pintype "input"))
      (node (ref "IC47") (pin "3") (pinfunction "I1_3") (pintype "input"))
      (node (ref "IC47") (pin "6") (pinfunction "I1_6") (pintype "input"))
      (node (ref "IC47") (pin "9") (pinfunction "I1_9") (pintype "input"))
      (node (ref "IC48") (pin "3") (pinfunction "I1_3") (pintype "input"))
      (node (ref "IC55") (pin "11") (pinfunction "I_11") (pintype "input"))
      (node (ref "IC55") (pin "9") (pinfunction "I_9") (pintype "input"))
      (node (ref "IC7") (pin "12") (pinfunction "D_12") (pintype "input"))
      (node (ref "IC94") (pin "9") (pinfunction "I_9") (pintype "input"))
      (node (ref "M916_1") (pin "C2") (pinfunction "P$2_C2") (pintype "bidirectional"))
      (node (ref "M916_1") (pin "T1") (pinfunction "P$2_T1") (pintype "bidirectional"))
      (node (ref "M916_10") (pin "D2") (pinfunction "P$2_D2") (pintype "bidirectional"))
      (node (ref "M916_10") (pin "U2") (pinfunction "P$2_U2") (pintype "bidirectional"))
      (node (ref "M916_10") (pin "V1") (pinfunction "P$2_V1") (pintype "bidirectional"))
      (node (ref "M916_11") (pin "C2") (pinfunction "P$2_C2") (pintype "bidirectional"))
      (node (ref "M916_11") (pin "T1") (pinfunction "P$2_T1") (pintype "bidirectional"))
      (node (ref "M916_12") (pin "C2") (pinfunction "P$2_C2") (pintype "bidirectional"))
      (node (ref "M916_13") (pin "C2") (pinfunction "P$2_C2") (pintype "bidirectional"))
      (node (ref "M916_14") (pin "C2") (pinfunction "P$2_C2") (pintype "bidirectional"))
      (node (ref "M916_15") (pin "C2") (pinfunction "P$2_C2") (pintype "bidirectional"))
      (node (ref "M916_15") (pin "T1") (pinfunction "P$2_T1") (pintype "bidirectional"))
      (node (ref "M916_15") (pin "T2") (pinfunction "P$2_T2") (pintype "bidirectional"))
      (node (ref "M916_15") (pin "U1") (pinfunction "P$2_U1") (pintype "bidirectional"))
      (node (ref "M916_15") (pin "V1") (pinfunction "P$2_V1") (pintype "bidirectional"))
      (node (ref "M916_16") (pin "C2") (pinfunction "P$2_C2") (pintype "bidirectional"))
      (node (ref "M916_17") (pin "C2") (pinfunction "P$2_C2") (pintype "bidirectional"))
      (node (ref "M916_17") (pin "T1") (pinfunction "P$2_T1") (pintype "bidirectional"))
      (node (ref "M916_18") (pin "C2") (pinfunction "P$2_C2") (pintype "bidirectional"))
      (node (ref "M916_18") (pin "T1") (pinfunction "P$2_T1") (pintype "bidirectional"))
      (node (ref "M916_19") (pin "C2") (pinfunction "P$2_C2") (pintype "bidirectional"))
      (node (ref "M916_19") (pin "T1") (pinfunction "P$2_T1") (pintype "bidirectional"))
      (node (ref "M916_2") (pin "C2") (pinfunction "P$2_C2") (pintype "bidirectional"))
      (node (ref "M916_2") (pin "T1") (pinfunction "P$2_T1") (pintype "bidirectional"))
      (node (ref "M916_20") (pin "C2") (pinfunction "P$2_C2") (pintype "bidirectional"))
      (node (ref "M916_20") (pin "T1") (pinfunction "P$2_T1") (pintype "bidirectional"))
      (node (ref "M916_21") (pin "C2") (pinfunction "P$2_C2") (pintype "bidirectional"))
      (node (ref "M916_21") (pin "T1") (pinfunction "P$2_T1") (pintype "bidirectional"))
      (node (ref "M916_22") (pin "C2") (pinfunction "P$2_C2") (pintype "bidirectional"))
      (node (ref "M916_22") (pin "T1") (pinfunction "P$2_T1") (pintype "bidirectional"))
      (node (ref "M916_23") (pin "C2") (pinfunction "P$2_C2") (pintype "bidirectional"))
      (node (ref "M916_23") (pin "T1") (pinfunction "P$2_T1") (pintype "bidirectional"))
      (node (ref "M916_3") (pin "C2") (pinfunction "P$2_C2") (pintype "bidirectional"))
      (node (ref "M916_4") (pin "C2") (pinfunction "P$2_C2") (pintype "bidirectional"))
      (node (ref "M916_5") (pin "C2") (pinfunction "P$2_C2") (pintype "bidirectional"))
      (node (ref "M916_6") (pin "C2") (pinfunction "P$2_C2") (pintype "bidirectional"))
      (node (ref "M916_6") (pin "M2") (pinfunction "P$2_M2") (pintype "bidirectional"))
      (node (ref "M916_7") (pin "C1") (pinfunction "P$2_C1") (pintype "bidirectional"))
      (node (ref "M916_7") (pin "C2") (pinfunction "P$2_C2") (pintype "bidirectional"))
      (node (ref "M916_7") (pin "F2") (pinfunction "P$2_F2") (pintype "bidirectional"))
      (node (ref "M916_7") (pin "J1") (pinfunction "P$2_J1") (pintype "bidirectional"))
      (node (ref "M916_7") (pin "M2") (pinfunction "P$2_M2") (pintype "bidirectional"))
      (node (ref "M916_7") (pin "P1") (pinfunction "P$2_P1") (pintype "bidirectional"))
      (node (ref "M916_7") (pin "T1") (pinfunction "P$2_T1") (pintype "bidirectional"))
      (node (ref "M916_7") (pin "T2") (pinfunction "P$2_T2") (pintype "bidirectional"))
      (node (ref "M916_7") (pin "U1") (pinfunction "P$2_U1") (pintype "bidirectional"))
      (node (ref "M916_7") (pin "V1") (pinfunction "P$2_V1") (pintype "bidirectional"))
      (node (ref "M916_9") (pin "M1") (pinfunction "P$2_M1") (pintype "bidirectional"))
      (node (ref "SV1") (pin "A") (pinfunction "1_A") (pintype "bidirectional"))
      (node (ref "SV1") (pin "AA") (pinfunction "23_AA") (pintype "bidirectional"))
      (node (ref "SV1") (pin "B") (pinfunction "2_B") (pintype "bidirectional"))
      (node (ref "SV1") (pin "C") (pinfunction "3_C") (pintype "bidirectional"))
      (node (ref "SV1") (pin "CC") (pinfunction "25_CC") (pintype "bidirectional"))
      (node (ref "SV1") (pin "E") (pinfunction "5_E") (pintype "bidirectional"))
      (node (ref "SV1") (pin "EE") (pinfunction "27_EE") (pintype "bidirectional"))
      (node (ref "SV1") (pin "H") (pinfunction "7_H") (pintype "bidirectional"))
      (node (ref "SV1") (pin "HH") (pinfunction "29_HH") (pintype "bidirectional"))
      (node (ref "SV1") (pin "K") (pinfunction "9_K") (pintype "bidirectional"))
      (node (ref "SV1") (pin "KK") (pinfunction "31_KK") (pintype "bidirectional"))
      (node (ref "SV1") (pin "M") (pinfunction "11_M") (pintype "bidirectional"))
      (node (ref "SV1") (pin "MM") (pinfunction "33_MM") (pintype "bidirectional"))
      (node (ref "SV1") (pin "P") (pinfunction "13_P") (pintype "bidirectional"))
      (node (ref "SV1") (pin "PP") (pinfunction "35_PP") (pintype "bidirectional"))
      (node (ref "SV1") (pin "S") (pinfunction "15_S") (pintype "bidirectional"))
      (node (ref "SV1") (pin "SS") (pinfunction "37_SS") (pintype "bidirectional"))
      (node (ref "SV1") (pin "U") (pinfunction "17_U") (pintype "bidirectional"))
      (node (ref "SV1") (pin "UU") (pinfunction "39_UU") (pintype "bidirectional"))
      (node (ref "SV1") (pin "VV") (pinfunction "40_VV") (pintype "bidirectional"))
      (node (ref "SV1") (pin "W") (pinfunction "19_W") (pintype "bidirectional"))
      (node (ref "SV1") (pin "Y") (pinfunction "21_Y") (pintype "bidirectional"))
      (node (ref "SV10") (pin "A") (pinfunction "1_A") (pintype "bidirectional"))
      (node (ref "SV10") (pin "AA") (pinfunction "23_AA") (pintype "bidirectional"))
      (node (ref "SV10") (pin "B") (pinfunction "2_B") (pintype "bidirectional"))
      (node (ref "SV10") (pin "C") (pinfunction "3_C") (pintype "bidirectional"))
      (node (ref "SV10") (pin "CC") (pinfunction "25_CC") (pintype "bidirectional"))
      (node (ref "SV10") (pin "E") (pinfunction "5_E") (pintype "bidirectional"))
      (node (ref "SV10") (pin "EE") (pinfunction "27_EE") (pintype "bidirectional"))
      (node (ref "SV10") (pin "H") (pinfunction "7_H") (pintype "bidirectional"))
      (node (ref "SV10") (pin "HH") (pinfunction "29_HH") (pintype "bidirectional"))
      (node (ref "SV10") (pin "K") (pinfunction "9_K") (pintype "bidirectional"))
      (node (ref "SV10") (pin "KK") (pinfunction "31_KK") (pintype "bidirectional"))
      (node (ref "SV10") (pin "M") (pinfunction "11_M") (pintype "bidirectional"))
      (node (ref "SV10") (pin "MM") (pinfunction "33_MM") (pintype "bidirectional"))
      (node (ref "SV10") (pin "P") (pinfunction "13_P") (pintype "bidirectional"))
      (node (ref "SV10") (pin "PP") (pinfunction "35_PP") (pintype "bidirectional"))
      (node (ref "SV10") (pin "S") (pinfunction "15_S") (pintype "bidirectional"))
      (node (ref "SV10") (pin "SS") (pinfunction "37_SS") (pintype "bidirectional"))
      (node (ref "SV10") (pin "U") (pinfunction "17_U") (pintype "bidirectional"))
      (node (ref "SV10") (pin "UU") (pinfunction "39_UU") (pintype "bidirectional"))
      (node (ref "SV10") (pin "VV") (pinfunction "40_VV") (pintype "bidirectional"))
      (node (ref "SV10") (pin "W") (pinfunction "19_W") (pintype "bidirectional"))
      (node (ref "SV10") (pin "Y") (pinfunction "21_Y") (pintype "bidirectional"))
      (node (ref "SV11") (pin "A") (pinfunction "1_A") (pintype "bidirectional"))
      (node (ref "SV11") (pin "AA") (pinfunction "23_AA") (pintype "bidirectional"))
      (node (ref "SV11") (pin "B") (pinfunction "2_B") (pintype "bidirectional"))
      (node (ref "SV11") (pin "BB") (pinfunction "24_BB") (pintype "bidirectional"))
      (node (ref "SV11") (pin "C") (pinfunction "3_C") (pintype "bidirectional"))
      (node (ref "SV11") (pin "CC") (pinfunction "25_CC") (pintype "bidirectional"))
      (node (ref "SV11") (pin "D") (pinfunction "4_D") (pintype "bidirectional"))
      (node (ref "SV11") (pin "E") (pinfunction "5_E") (pintype "bidirectional"))
      (node (ref "SV11") (pin "EE") (pinfunction "27_EE") (pintype "bidirectional"))
      (node (ref "SV11") (pin "F") (pinfunction "6_F") (pintype "bidirectional"))
      (node (ref "SV11") (pin "FF") (pinfunction "28_FF") (pintype "bidirectional"))
      (node (ref "SV11") (pin "H") (pinfunction "7_H") (pintype "bidirectional"))
      (node (ref "SV11") (pin "HH") (pinfunction "29_HH") (pintype "bidirectional"))
      (node (ref "SV11") (pin "J") (pinfunction "8_J") (pintype "bidirectional"))
      (node (ref "SV11") (pin "K") (pinfunction "9_K") (pintype "bidirectional"))
      (node (ref "SV11") (pin "KK") (pinfunction "31_KK") (pintype "bidirectional"))
      (node (ref "SV11") (pin "LL") (pinfunction "32_LL") (pintype "bidirectional"))
      (node (ref "SV11") (pin "M") (pinfunction "11_M") (pintype "bidirectional"))
      (node (ref "SV11") (pin "MM") (pinfunction "33_MM") (pintype "bidirectional"))
      (node (ref "SV11") (pin "N") (pinfunction "12_N") (pintype "bidirectional"))
      (node (ref "SV11") (pin "P") (pinfunction "13_P") (pintype "bidirectional"))
      (node (ref "SV11") (pin "PP") (pinfunction "35_PP") (pintype "bidirectional"))
      (node (ref "SV11") (pin "RR") (pinfunction "36_RR") (pintype "bidirectional"))
      (node (ref "SV11") (pin "S") (pinfunction "15_S") (pintype "bidirectional"))
      (node (ref "SV11") (pin "SS") (pinfunction "37_SS") (pintype "bidirectional"))
      (node (ref "SV11") (pin "T") (pinfunction "16_T") (pintype "bidirectional"))
      (node (ref "SV11") (pin "U") (pinfunction "17_U") (pintype "bidirectional"))
      (node (ref "SV11") (pin "UU") (pinfunction "39_UU") (pintype "bidirectional"))
      (node (ref "SV11") (pin "VV") (pinfunction "40_VV") (pintype "bidirectional"))
      (node (ref "SV11") (pin "W") (pinfunction "19_W") (pintype "bidirectional"))
      (node (ref "SV11") (pin "X") (pinfunction "20_X") (pintype "bidirectional"))
      (node (ref "SV11") (pin "Y") (pinfunction "21_Y") (pintype "bidirectional"))
      (node (ref "SV12") (pin "A") (pinfunction "1_A") (pintype "bidirectional"))
      (node (ref "SV12") (pin "AA") (pinfunction "23_AA") (pintype "bidirectional"))
      (node (ref "SV12") (pin "B") (pinfunction "2_B") (pintype "bidirectional"))
      (node (ref "SV12") (pin "C") (pinfunction "3_C") (pintype "bidirectional"))
      (node (ref "SV12") (pin "CC") (pinfunction "25_CC") (pintype "bidirectional"))
      (node (ref "SV12") (pin "E") (pinfunction "5_E") (pintype "bidirectional"))
      (node (ref "SV12") (pin "EE") (pinfunction "27_EE") (pintype "bidirectional"))
      (node (ref "SV12") (pin "H") (pinfunction "7_H") (pintype "bidirectional"))
      (node (ref "SV12") (pin "HH") (pinfunction "29_HH") (pintype "bidirectional"))
      (node (ref "SV12") (pin "K") (pinfunction "9_K") (pintype "bidirectional"))
      (node (ref "SV12") (pin "KK") (pinfunction "31_KK") (pintype "bidirectional"))
      (node (ref "SV12") (pin "M") (pinfunction "11_M") (pintype "bidirectional"))
      (node (ref "SV12") (pin "MM") (pinfunction "33_MM") (pintype "bidirectional"))
      (node (ref "SV12") (pin "P") (pinfunction "13_P") (pintype "bidirectional"))
      (node (ref "SV12") (pin "PP") (pinfunction "35_PP") (pintype "bidirectional"))
      (node (ref "SV12") (pin "S") (pinfunction "15_S") (pintype "bidirectional"))
      (node (ref "SV12") (pin "SS") (pinfunction "37_SS") (pintype "bidirectional"))
      (node (ref "SV12") (pin "U") (pinfunction "17_U") (pintype "bidirectional"))
      (node (ref "SV12") (pin "UU") (pinfunction "39_UU") (pintype "bidirectional"))
      (node (ref "SV12") (pin "V") (pinfunction "18_V") (pintype "bidirectional"))
      (node (ref "SV12") (pin "VV") (pinfunction "40_VV") (pintype "bidirectional"))
      (node (ref "SV12") (pin "W") (pinfunction "19_W") (pintype "bidirectional"))
      (node (ref "SV12") (pin "Y") (pinfunction "21_Y") (pintype "bidirectional"))
      (node (ref "SV2") (pin "A") (pinfunction "1_A") (pintype "bidirectional"))
      (node (ref "SV2") (pin "AA") (pinfunction "23_AA") (pintype "bidirectional"))
      (node (ref "SV2") (pin "B") (pinfunction "2_B") (pintype "bidirectional"))
      (node (ref "SV2") (pin "C") (pinfunction "3_C") (pintype "bidirectional"))
      (node (ref "SV2") (pin "CC") (pinfunction "25_CC") (pintype "bidirectional"))
      (node (ref "SV2") (pin "E") (pinfunction "5_E") (pintype "bidirectional"))
      (node (ref "SV2") (pin "EE") (pinfunction "27_EE") (pintype "bidirectional"))
      (node (ref "SV2") (pin "H") (pinfunction "7_H") (pintype "bidirectional"))
      (node (ref "SV2") (pin "HH") (pinfunction "29_HH") (pintype "bidirectional"))
      (node (ref "SV2") (pin "K") (pinfunction "9_K") (pintype "bidirectional"))
      (node (ref "SV2") (pin "KK") (pinfunction "31_KK") (pintype "bidirectional"))
      (node (ref "SV2") (pin "M") (pinfunction "11_M") (pintype "bidirectional"))
      (node (ref "SV2") (pin "MM") (pinfunction "33_MM") (pintype "bidirectional"))
      (node (ref "SV2") (pin "P") (pinfunction "13_P") (pintype "bidirectional"))
      (node (ref "SV2") (pin "PP") (pinfunction "35_PP") (pintype "bidirectional"))
      (node (ref "SV2") (pin "S") (pinfunction "15_S") (pintype "bidirectional"))
      (node (ref "SV2") (pin "SS") (pinfunction "37_SS") (pintype "bidirectional"))
      (node (ref "SV2") (pin "U") (pinfunction "17_U") (pintype "bidirectional"))
      (node (ref "SV2") (pin "UU") (pinfunction "39_UU") (pintype "bidirectional"))
      (node (ref "SV2") (pin "VV") (pinfunction "40_VV") (pintype "bidirectional"))
      (node (ref "SV2") (pin "W") (pinfunction "19_W") (pintype "bidirectional"))
      (node (ref "SV2") (pin "Y") (pinfunction "21_Y") (pintype "bidirectional"))
      (node (ref "SV3") (pin "A") (pinfunction "1_A") (pintype "bidirectional"))
      (node (ref "SV3") (pin "AA") (pinfunction "23_AA") (pintype "bidirectional"))
      (node (ref "SV3") (pin "B") (pinfunction "2_B") (pintype "bidirectional"))
      (node (ref "SV3") (pin "C") (pinfunction "3_C") (pintype "bidirectional"))
      (node (ref "SV3") (pin "CC") (pinfunction "25_CC") (pintype "bidirectional"))
      (node (ref "SV3") (pin "E") (pinfunction "5_E") (pintype "bidirectional"))
      (node (ref "SV3") (pin "EE") (pinfunction "27_EE") (pintype "bidirectional"))
      (node (ref "SV3") (pin "H") (pinfunction "7_H") (pintype "bidirectional"))
      (node (ref "SV3") (pin "HH") (pinfunction "29_HH") (pintype "bidirectional"))
      (node (ref "SV3") (pin "K") (pinfunction "9_K") (pintype "bidirectional"))
      (node (ref "SV3") (pin "KK") (pinfunction "31_KK") (pintype "bidirectional"))
      (node (ref "SV3") (pin "M") (pinfunction "11_M") (pintype "bidirectional"))
      (node (ref "SV3") (pin "MM") (pinfunction "33_MM") (pintype "bidirectional"))
      (node (ref "SV3") (pin "P") (pinfunction "13_P") (pintype "bidirectional"))
      (node (ref "SV3") (pin "PP") (pinfunction "35_PP") (pintype "bidirectional"))
      (node (ref "SV3") (pin "S") (pinfunction "15_S") (pintype "bidirectional"))
      (node (ref "SV3") (pin "SS") (pinfunction "37_SS") (pintype "bidirectional"))
      (node (ref "SV3") (pin "U") (pinfunction "17_U") (pintype "bidirectional"))
      (node (ref "SV3") (pin "UU") (pinfunction "39_UU") (pintype "bidirectional"))
      (node (ref "SV3") (pin "VV") (pinfunction "40_VV") (pintype "bidirectional"))
      (node (ref "SV3") (pin "W") (pinfunction "19_W") (pintype "bidirectional"))
      (node (ref "SV3") (pin "Y") (pinfunction "21_Y") (pintype "bidirectional"))
      (node (ref "SV4") (pin "A") (pinfunction "1_A") (pintype "bidirectional"))
      (node (ref "SV4") (pin "AA") (pinfunction "23_AA") (pintype "bidirectional"))
      (node (ref "SV4") (pin "B") (pinfunction "2_B") (pintype "bidirectional"))
      (node (ref "SV4") (pin "BB") (pinfunction "24_BB") (pintype "bidirectional"))
      (node (ref "SV4") (pin "C") (pinfunction "3_C") (pintype "bidirectional"))
      (node (ref "SV4") (pin "CC") (pinfunction "25_CC") (pintype "bidirectional"))
      (node (ref "SV4") (pin "D") (pinfunction "4_D") (pintype "bidirectional"))
      (node (ref "SV4") (pin "E") (pinfunction "5_E") (pintype "bidirectional"))
      (node (ref "SV4") (pin "EE") (pinfunction "27_EE") (pintype "bidirectional"))
      (node (ref "SV4") (pin "F") (pinfunction "6_F") (pintype "bidirectional"))
      (node (ref "SV4") (pin "FF") (pinfunction "28_FF") (pintype "bidirectional"))
      (node (ref "SV4") (pin "H") (pinfunction "7_H") (pintype "bidirectional"))
      (node (ref "SV4") (pin "HH") (pinfunction "29_HH") (pintype "bidirectional"))
      (node (ref "SV4") (pin "J") (pinfunction "8_J") (pintype "bidirectional"))
      (node (ref "SV4") (pin "K") (pinfunction "9_K") (pintype "bidirectional"))
      (node (ref "SV4") (pin "KK") (pinfunction "31_KK") (pintype "bidirectional"))
      (node (ref "SV4") (pin "LL") (pinfunction "32_LL") (pintype "bidirectional"))
      (node (ref "SV4") (pin "M") (pinfunction "11_M") (pintype "bidirectional"))
      (node (ref "SV4") (pin "MM") (pinfunction "33_MM") (pintype "bidirectional"))
      (node (ref "SV4") (pin "N") (pinfunction "12_N") (pintype "bidirectional"))
      (node (ref "SV4") (pin "P") (pinfunction "13_P") (pintype "bidirectional"))
      (node (ref "SV4") (pin "PP") (pinfunction "35_PP") (pintype "bidirectional"))
      (node (ref "SV4") (pin "RR") (pinfunction "36_RR") (pintype "bidirectional"))
      (node (ref "SV4") (pin "S") (pinfunction "15_S") (pintype "bidirectional"))
      (node (ref "SV4") (pin "SS") (pinfunction "37_SS") (pintype "bidirectional"))
      (node (ref "SV4") (pin "T") (pinfunction "16_T") (pintype "bidirectional"))
      (node (ref "SV4") (pin "U") (pinfunction "17_U") (pintype "bidirectional"))
      (node (ref "SV4") (pin "UU") (pinfunction "39_UU") (pintype "bidirectional"))
      (node (ref "SV4") (pin "VV") (pinfunction "40_VV") (pintype "bidirectional"))
      (node (ref "SV4") (pin "W") (pinfunction "19_W") (pintype "bidirectional"))
      (node (ref "SV4") (pin "X") (pinfunction "20_X") (pintype "bidirectional"))
      (node (ref "SV4") (pin "Y") (pinfunction "21_Y") (pintype "bidirectional"))
      (node (ref "SV5") (pin "A") (pinfunction "1_A") (pintype "bidirectional"))
      (node (ref "SV5") (pin "AA") (pinfunction "23_AA") (pintype "bidirectional"))
      (node (ref "SV5") (pin "B") (pinfunction "2_B") (pintype "bidirectional"))
      (node (ref "SV5") (pin "C") (pinfunction "3_C") (pintype "bidirectional"))
      (node (ref "SV5") (pin "CC") (pinfunction "25_CC") (pintype "bidirectional"))
      (node (ref "SV5") (pin "E") (pinfunction "5_E") (pintype "bidirectional"))
      (node (ref "SV5") (pin "EE") (pinfunction "27_EE") (pintype "bidirectional"))
      (node (ref "SV5") (pin "H") (pinfunction "7_H") (pintype "bidirectional"))
      (node (ref "SV5") (pin "HH") (pinfunction "29_HH") (pintype "bidirectional"))
      (node (ref "SV5") (pin "K") (pinfunction "9_K") (pintype "bidirectional"))
      (node (ref "SV5") (pin "KK") (pinfunction "31_KK") (pintype "bidirectional"))
      (node (ref "SV5") (pin "M") (pinfunction "11_M") (pintype "bidirectional"))
      (node (ref "SV5") (pin "MM") (pinfunction "33_MM") (pintype "bidirectional"))
      (node (ref "SV5") (pin "P") (pinfunction "13_P") (pintype "bidirectional"))
      (node (ref "SV5") (pin "PP") (pinfunction "35_PP") (pintype "bidirectional"))
      (node (ref "SV5") (pin "S") (pinfunction "15_S") (pintype "bidirectional"))
      (node (ref "SV5") (pin "SS") (pinfunction "37_SS") (pintype "bidirectional"))
      (node (ref "SV5") (pin "U") (pinfunction "17_U") (pintype "bidirectional"))
      (node (ref "SV5") (pin "UU") (pinfunction "39_UU") (pintype "bidirectional"))
      (node (ref "SV5") (pin "V") (pinfunction "18_V") (pintype "bidirectional"))
      (node (ref "SV5") (pin "VV") (pinfunction "40_VV") (pintype "bidirectional"))
      (node (ref "SV5") (pin "W") (pinfunction "19_W") (pintype "bidirectional"))
      (node (ref "SV5") (pin "Y") (pinfunction "21_Y") (pintype "bidirectional"))
      (node (ref "SV6") (pin "1") (pinfunction "1_1") (pintype "passive"))
      (node (ref "SV6") (pin "10") (pinfunction "10_10") (pintype "passive"))
      (node (ref "SV6") (pin "11") (pinfunction "11_11") (pintype "passive"))
      (node (ref "SV6") (pin "13") (pinfunction "13_13") (pintype "passive"))
      (node (ref "SV6") (pin "15") (pinfunction "15_15") (pintype "passive"))
      (node (ref "SV6") (pin "17") (pinfunction "17_17") (pintype "passive"))
      (node (ref "SV6") (pin "18") (pinfunction "18_18") (pintype "passive"))
      (node (ref "SV6") (pin "19") (pinfunction "19_19") (pintype "passive"))
      (node (ref "SV6") (pin "20") (pinfunction "20_20") (pintype "passive"))
      (node (ref "SV6") (pin "21") (pinfunction "21_21") (pintype "passive"))
      (node (ref "SV6") (pin "23") (pinfunction "23_23") (pintype "passive"))
      (node (ref "SV6") (pin "25") (pinfunction "25_25") (pintype "passive"))
      (node (ref "SV6") (pin "27") (pinfunction "27_27") (pintype "passive"))
      (node (ref "SV6") (pin "29") (pinfunction "29_29") (pintype "passive"))
      (node (ref "SV6") (pin "3") (pinfunction "3_3") (pintype "passive"))
      (node (ref "SV6") (pin "31") (pinfunction "31_31") (pintype "passive"))
      (node (ref "SV6") (pin "33") (pinfunction "33_33") (pintype "passive"))
      (node (ref "SV6") (pin "5") (pinfunction "5_5") (pintype "passive"))
      (node (ref "SV6") (pin "7") (pinfunction "7_7") (pintype "passive"))
      (node (ref "SV6") (pin "8") (pinfunction "8_8") (pintype "passive"))
      (node (ref "SV6") (pin "9") (pinfunction "9_9") (pintype "passive"))
      (node (ref "SV7") (pin "1") (pinfunction "1_1") (pintype "passive"))
      (node (ref "SV7") (pin "11") (pinfunction "11_11") (pintype "passive"))
      (node (ref "SV7") (pin "13") (pinfunction "13_13") (pintype "passive"))
      (node (ref "SV7") (pin "14") (pinfunction "14_14") (pintype "passive"))
      (node (ref "SV7") (pin "15") (pinfunction "15_15") (pintype "passive"))
      (node (ref "SV7") (pin "16") (pinfunction "16_16") (pintype "passive"))
      (node (ref "SV7") (pin "17") (pinfunction "17_17") (pintype "passive"))
      (node (ref "SV7") (pin "19") (pinfunction "19_19") (pintype "passive"))
      (node (ref "SV7") (pin "21") (pinfunction "21_21") (pintype "passive"))
      (node (ref "SV7") (pin "23") (pinfunction "23_23") (pintype "passive"))
      (node (ref "SV7") (pin "25") (pinfunction "25_25") (pintype "passive"))
      (node (ref "SV7") (pin "26") (pinfunction "26_26") (pintype "passive"))
      (node (ref "SV7") (pin "27") (pinfunction "27_27") (pintype "passive"))
      (node (ref "SV7") (pin "28") (pinfunction "28_28") (pintype "passive"))
      (node (ref "SV7") (pin "29") (pinfunction "29_29") (pintype "passive"))
      (node (ref "SV7") (pin "3") (pinfunction "3_3") (pintype "passive"))
      (node (ref "SV7") (pin "30") (pinfunction "30_30") (pintype "passive"))
      (node (ref "SV7") (pin "31") (pinfunction "31_31") (pintype "passive"))
      (node (ref "SV7") (pin "33") (pinfunction "33_33") (pintype "passive"))
      (node (ref "SV7") (pin "34") (pinfunction "34_34") (pintype "passive"))
      (node (ref "SV7") (pin "5") (pinfunction "5_5") (pintype "passive"))
      (node (ref "SV7") (pin "7") (pinfunction "7_7") (pintype "passive"))
      (node (ref "SV7") (pin "9") (pinfunction "9_9") (pintype "passive"))
      (node (ref "SV8") (pin "A") (pinfunction "1_A") (pintype "bidirectional"))
      (node (ref "SV8") (pin "AA") (pinfunction "23_AA") (pintype "bidirectional"))
      (node (ref "SV8") (pin "B") (pinfunction "2_B") (pintype "bidirectional"))
      (node (ref "SV8") (pin "C") (pinfunction "3_C") (pintype "bidirectional"))
      (node (ref "SV8") (pin "CC") (pinfunction "25_CC") (pintype "bidirectional"))
      (node (ref "SV8") (pin "E") (pinfunction "5_E") (pintype "bidirectional"))
      (node (ref "SV8") (pin "EE") (pinfunction "27_EE") (pintype "bidirectional"))
      (node (ref "SV8") (pin "H") (pinfunction "7_H") (pintype "bidirectional"))
      (node (ref "SV8") (pin "HH") (pinfunction "29_HH") (pintype "bidirectional"))
      (node (ref "SV8") (pin "K") (pinfunction "9_K") (pintype "bidirectional"))
      (node (ref "SV8") (pin "KK") (pinfunction "31_KK") (pintype "bidirectional"))
      (node (ref "SV8") (pin "M") (pinfunction "11_M") (pintype "bidirectional"))
      (node (ref "SV8") (pin "MM") (pinfunction "33_MM") (pintype "bidirectional"))
      (node (ref "SV8") (pin "P") (pinfunction "13_P") (pintype "bidirectional"))
      (node (ref "SV8") (pin "PP") (pinfunction "35_PP") (pintype "bidirectional"))
      (node (ref "SV8") (pin "S") (pinfunction "15_S") (pintype "bidirectional"))
      (node (ref "SV8") (pin "SS") (pinfunction "37_SS") (pintype "bidirectional"))
      (node (ref "SV8") (pin "U") (pinfunction "17_U") (pintype "bidirectional"))
      (node (ref "SV8") (pin "UU") (pinfunction "39_UU") (pintype "bidirectional"))
      (node (ref "SV8") (pin "VV") (pinfunction "40_VV") (pintype "bidirectional"))
      (node (ref "SV8") (pin "W") (pinfunction "19_W") (pintype "bidirectional"))
      (node (ref "SV8") (pin "Y") (pinfunction "21_Y") (pintype "bidirectional"))
      (node (ref "SV9") (pin "A") (pinfunction "1_A") (pintype "bidirectional"))
      (node (ref "SV9") (pin "AA") (pinfunction "23_AA") (pintype "bidirectional"))
      (node (ref "SV9") (pin "B") (pinfunction "2_B") (pintype "bidirectional"))
      (node (ref "SV9") (pin "C") (pinfunction "3_C") (pintype "bidirectional"))
      (node (ref "SV9") (pin "CC") (pinfunction "25_CC") (pintype "bidirectional"))
      (node (ref "SV9") (pin "E") (pinfunction "5_E") (pintype "bidirectional"))
      (node (ref "SV9") (pin "EE") (pinfunction "27_EE") (pintype "bidirectional"))
      (node (ref "SV9") (pin "H") (pinfunction "7_H") (pintype "bidirectional"))
      (node (ref "SV9") (pin "HH") (pinfunction "29_HH") (pintype "bidirectional"))
      (node (ref "SV9") (pin "K") (pinfunction "9_K") (pintype "bidirectional"))
      (node (ref "SV9") (pin "KK") (pinfunction "31_KK") (pintype "bidirectional"))
      (node (ref "SV9") (pin "M") (pinfunction "11_M") (pintype "bidirectional"))
      (node (ref "SV9") (pin "MM") (pinfunction "33_MM") (pintype "bidirectional"))
      (node (ref "SV9") (pin "P") (pinfunction "13_P") (pintype "bidirectional"))
      (node (ref "SV9") (pin "PP") (pinfunction "35_PP") (pintype "bidirectional"))
      (node (ref "SV9") (pin "S") (pinfunction "15_S") (pintype "bidirectional"))
      (node (ref "SV9") (pin "SS") (pinfunction "37_SS") (pintype "bidirectional"))
      (node (ref "SV9") (pin "U") (pinfunction "17_U") (pintype "bidirectional"))
      (node (ref "SV9") (pin "UU") (pinfunction "39_UU") (pintype "bidirectional"))
      (node (ref "SV9") (pin "VV") (pinfunction "40_VV") (pintype "bidirectional"))
      (node (ref "SV9") (pin "W") (pinfunction "19_W") (pintype "bidirectional"))
      (node (ref "SV9") (pin "Y") (pinfunction "21_Y") (pintype "bidirectional"))
    )
    (net (code "89") (name "IOP_1") (class "Default")
      (node (ref "IC87") (pin "5") (pinfunction "I1_5") (pintype "input"))
      (node (ref "IC89") (pin "10") (pinfunction "I1_10") (pintype "input"))
      (node (ref "SV1") (pin "V") (pinfunction "18_V") (pintype "bidirectional"))
      (node (ref "SV8") (pin "V") (pinfunction "18_V") (pintype "bidirectional"))
    )
    (net (code "90") (name "IOP_2") (class "Default")
      (node (ref "IC87") (pin "10") (pinfunction "I1_10") (pintype "input"))
      (node (ref "IC89") (pin "13") (pinfunction "I1_13") (pintype "input"))
      (node (ref "SV1") (pin "Z") (pinfunction "22_Z") (pintype "bidirectional"))
      (node (ref "SV8") (pin "Z") (pinfunction "22_Z") (pintype "bidirectional"))
    )
    (net (code "91") (name "IOP_4") (class "Default")
      (node (ref "IC87") (pin "13") (pinfunction "I1_13") (pintype "input"))
      (node (ref "IC91") (pin "2") (pinfunction "I1_2") (pintype "input"))
      (node (ref "SV1") (pin "DD") (pinfunction "26_DD") (pintype "bidirectional"))
      (node (ref "SV8") (pin "DD") (pinfunction "26_DD") (pintype "bidirectional"))
    )
    (net (code "92") (name "I{slash}O_B-BRK") (class "Default")
      (node (ref "IC79") (pin "5") (pinfunction "I1_5") (pintype "input"))
      (node (ref "SV11") (pin "DD") (pinfunction "26_DD") (pintype "bidirectional"))
      (node (ref "SV4") (pin "DD") (pinfunction "26_DD") (pintype "bidirectional"))
    )
    (net (code "93") (name "I{slash}O_B-RUN") (class "Default")
      (node (ref "IC79") (pin "2") (pinfunction "I1_2") (pintype "input"))
      (node (ref "SV10") (pin "JJ") (pinfunction "30_JJ") (pintype "bidirectional"))
      (node (ref "SV3") (pin "JJ") (pinfunction "30_JJ") (pintype "bidirectional"))
    )
    (net (code "94") (name "I{slash}O_BAC_00") (class "Default")
      (node (ref "IC83") (pin "2") (pinfunction "I1_2") (pintype "input"))
      (node (ref "SV1") (pin "D") (pinfunction "4_D") (pintype "bidirectional"))
      (node (ref "SV8") (pin "D") (pinfunction "4_D") (pintype "bidirectional"))
    )
    (net (code "95") (name "I{slash}O_BAC_01") (class "Default")
      (node (ref "IC83") (pin "5") (pinfunction "I1_5") (pintype "input"))
      (node (ref "SV1") (pin "J") (pinfunction "8_J") (pintype "bidirectional"))
      (node (ref "SV8") (pin "J") (pinfunction "8_J") (pintype "bidirectional"))
    )
    (net (code "96") (name "I{slash}O_BAC_02") (class "Default")
      (node (ref "IC85") (pin "10") (pinfunction "I1_10") (pintype "input"))
      (node (ref "SV1") (pin "N") (pinfunction "12_N") (pintype "bidirectional"))
      (node (ref "SV8") (pin "N") (pinfunction "12_N") (pintype "bidirectional"))
    )
    (net (code "97") (name "I{slash}O_BAC_03") (class "Default")
      (node (ref "IC84") (pin "10") (pinfunction "I1_10") (pintype "input"))
      (node (ref "SV1") (pin "T") (pinfunction "16_T") (pintype "bidirectional"))
      (node (ref "SV8") (pin "T") (pinfunction "16_T") (pintype "bidirectional"))
    )
    (net (code "98") (name "I{slash}O_BAC_04") (class "Default")
      (node (ref "IC84") (pin "13") (pinfunction "I1_13") (pintype "input"))
      (node (ref "SV1") (pin "X") (pinfunction "20_X") (pintype "bidirectional"))
      (node (ref "SV8") (pin "X") (pinfunction "20_X") (pintype "bidirectional"))
    )
    (net (code "99") (name "I{slash}O_BAC_05") (class "Default")
      (node (ref "IC85") (pin "2") (pinfunction "I1_2") (pintype "input"))
      (node (ref "SV1") (pin "BB") (pinfunction "24_BB") (pintype "bidirectional"))
      (node (ref "SV8") (pin "BB") (pinfunction "24_BB") (pintype "bidirectional"))
    )
    (net (code "100") (name "I{slash}O_BAC_06") (class "Default")
      (node (ref "IC85") (pin "5") (pinfunction "I1_5") (pintype "input"))
      (node (ref "SV1") (pin "FF") (pinfunction "28_FF") (pintype "bidirectional"))
      (node (ref "SV8") (pin "FF") (pinfunction "28_FF") (pintype "bidirectional"))
    )
    (net (code "101") (name "I{slash}O_BAC_07") (class "Default")
      (node (ref "IC84") (pin "5") (pinfunction "I1_5") (pintype "input"))
      (node (ref "SV1") (pin "LL") (pinfunction "32_LL") (pintype "bidirectional"))
      (node (ref "SV8") (pin "LL") (pinfunction "32_LL") (pintype "bidirectional"))
    )
    (net (code "102") (name "I{slash}O_BAC_08") (class "Default")
      (node (ref "IC83") (pin "10") (pinfunction "I1_10") (pintype "input"))
      (node (ref "SV1") (pin "RR") (pinfunction "36_RR") (pintype "bidirectional"))
      (node (ref "SV8") (pin "RR") (pinfunction "36_RR") (pintype "bidirectional"))
    )
    (net (code "103") (name "I{slash}O_BAC_09") (class "Default")
      (node (ref "IC83") (pin "13") (pinfunction "I1_13") (pintype "input"))
      (node (ref "SV1") (pin "F") (pinfunction "6_F") (pintype "bidirectional"))
      (node (ref "SV8") (pin "F") (pinfunction "6_F") (pintype "bidirectional"))
    )
    (net (code "104") (name "I{slash}O_BAC_10") (class "Default")
      (node (ref "IC84") (pin "2") (pinfunction "I1_2") (pintype "input"))
      (node (ref "SV1") (pin "L") (pinfunction "10_L") (pintype "bidirectional"))
      (node (ref "SV8") (pin "L") (pinfunction "10_L") (pintype "bidirectional"))
    )
    (net (code "105") (name "I{slash}O_BAC_11") (class "Default")
      (node (ref "IC85") (pin "13") (pinfunction "I1_13") (pintype "input"))
      (node (ref "SV1") (pin "R") (pinfunction "14_R") (pintype "bidirectional"))
      (node (ref "SV8") (pin "R") (pinfunction "14_R") (pintype "bidirectional"))
    )
    (net (code "106") (name "I{slash}O_BMB_00") (class "Default")
      (node (ref "IC79") (pin "13") (pinfunction "I1_13") (pintype "input"))
      (node (ref "SV2") (pin "D") (pinfunction "4_D") (pintype "bidirectional"))
      (node (ref "SV9") (pin "D") (pinfunction "4_D") (pintype "bidirectional"))
    )
    (net (code "107") (name "I{slash}O_BMB_01") (class "Default")
      (node (ref "IC80") (pin "2") (pinfunction "I1_2") (pintype "input"))
      (node (ref "SV2") (pin "J") (pinfunction "8_J") (pintype "bidirectional"))
      (node (ref "SV9") (pin "J") (pinfunction "8_J") (pintype "bidirectional"))
    )
    (net (code "108") (name "I{slash}O_BMB_02") (class "Default")
      (node (ref "IC82") (pin "5") (pinfunction "I1_5") (pintype "input"))
      (node (ref "SV2") (pin "N") (pinfunction "12_N") (pintype "bidirectional"))
      (node (ref "SV9") (pin "N") (pinfunction "12_N") (pintype "bidirectional"))
    )
    (net (code "109") (name "I{slash}O_BMB_03") (class "Default")
      (node (ref "IC81") (pin "5") (pinfunction "I1_5") (pintype "input"))
      (node (ref "IC86") (pin "1") (pinfunction "I0_1") (pintype "input"))
      (node (ref "IC90") (pin "1") (pinfunction "I0_1") (pintype "input"))
      (node (ref "SV2") (pin "X") (pinfunction "20_X") (pintype "bidirectional"))
      (node (ref "SV9") (pin "X") (pinfunction "20_X") (pintype "bidirectional"))
    )
    (net (code "110") (name "I{slash}O_BMB_04") (class "Default")
      (node (ref "IC81") (pin "10") (pinfunction "I1_10") (pintype "input"))
      (node (ref "IC86") (pin "2") (pinfunction "I1_2") (pintype "input"))
      (node (ref "IC90") (pin "2") (pinfunction "I1_2") (pintype "input"))
      (node (ref "SV2") (pin "FF") (pinfunction "28_FF") (pintype "bidirectional"))
      (node (ref "SV9") (pin "FF") (pinfunction "28_FF") (pintype "bidirectional"))
    )
    (net (code "111") (name "I{slash}O_BMB_05") (class "Default")
      (node (ref "IC81") (pin "13") (pinfunction "I1_13") (pintype "input"))
      (node (ref "IC86") (pin "3") (pinfunction "I2_3") (pintype "input"))
      (node (ref "IC90") (pin "3") (pinfunction "I2_3") (pintype "input"))
      (node (ref "SV2") (pin "RR") (pinfunction "36_RR") (pintype "bidirectional"))
      (node (ref "SV9") (pin "RR") (pinfunction "36_RR") (pintype "bidirectional"))
    )
    (net (code "112") (name "I{slash}O_BMB_06") (class "Default")
      (node (ref "IC82") (pin "2") (pinfunction "I1_2") (pintype "input"))
      (node (ref "IC86") (pin "4") (pinfunction "I3_4") (pintype "input"))
      (node (ref "IC90") (pin "4") (pinfunction "I3_4") (pintype "input"))
      (node (ref "SV2") (pin "L") (pinfunction "10_L") (pintype "bidirectional"))
      (node (ref "SV9") (pin "L") (pinfunction "10_L") (pintype "bidirectional"))
    )
    (net (code "113") (name "I{slash}O_BMB_07") (class "Default")
      (node (ref "IC81") (pin "2") (pinfunction "I1_2") (pintype "input"))
      (node (ref "IC86") (pin "5") (pinfunction "I4_5") (pintype "input"))
      (node (ref "IC90") (pin "5") (pinfunction "I4_5") (pintype "input"))
      (node (ref "SV2") (pin "V") (pinfunction "18_V") (pintype "bidirectional"))
      (node (ref "SV9") (pin "V") (pinfunction "18_V") (pintype "bidirectional"))
    )
    (net (code "114") (name "I{slash}O_BMB_08") (class "Default")
      (node (ref "IC80") (pin "5") (pinfunction "I1_5") (pintype "input"))
      (node (ref "IC90") (pin "6") (pinfunction "I5_6") (pintype "input"))
      (node (ref "SV2") (pin "DD") (pinfunction "26_DD") (pintype "bidirectional"))
      (node (ref "SV9") (pin "DD") (pinfunction "26_DD") (pintype "bidirectional"))
    )
    (net (code "115") (name "I{slash}O_BMB_09") (class "Default")
      (node (ref "IC80") (pin "10") (pinfunction "I1_10") (pintype "input"))
      (node (ref "SV2") (pin "JJ") (pinfunction "30_JJ") (pintype "bidirectional"))
      (node (ref "SV9") (pin "JJ") (pinfunction "30_JJ") (pintype "bidirectional"))
    )
    (net (code "116") (name "I{slash}O_BMB_10") (class "Default")
      (node (ref "IC80") (pin "13") (pinfunction "I1_13") (pintype "input"))
      (node (ref "SV2") (pin "NN") (pinfunction "34_NN") (pintype "bidirectional"))
      (node (ref "SV9") (pin "NN") (pinfunction "34_NN") (pintype "bidirectional"))
    )
    (net (code "117") (name "I{slash}O_BMB_11") (class "Default")
      (node (ref "IC82") (pin "10") (pinfunction "I1_10") (pintype "input"))
      (node (ref "SV2") (pin "TT") (pinfunction "38_TT") (pintype "bidirectional"))
      (node (ref "SV9") (pin "TT") (pinfunction "38_TT") (pintype "bidirectional"))
    )
    (net (code "118") (name "I{slash}O_DATA_IN") (class "Default")
      (node (ref "IC52") (pin "5") (pinfunction "O_5") (pintype "open_collector"))
      (node (ref "SV11") (pin "Z") (pinfunction "22_Z") (pintype "bidirectional"))
      (node (ref "SV4") (pin "Z") (pinfunction "22_Z") (pintype "bidirectional"))
    )
    (net (code "119") (name "I{slash}O_DATA_IN_B05") (class "Default")
      (node (ref "IC47") (pin "13") (pinfunction "O_13") (pintype "output"))
      (node (ref "IC52") (pin "6") (pinfunction "I0_6") (pintype "input"))
      (node (ref "IC52") (pin "7") (pinfunction "I1_7") (pintype "input"))
    )
    (net (code "120") (name "I{slash}O_PWR_CLR") (class "Default")
      (node (ref "IC91") (pin "4") (pinfunction "I0_4") (pintype "input"))
      (node (ref "SV1") (pin "TT") (pinfunction "38_TT") (pintype "bidirectional"))
      (node (ref "SV8") (pin "TT") (pinfunction "38_TT") (pintype "bidirectional"))
    )
    (net (code "121") (name "I{slash}O_TS03") (class "Default")
      (node (ref "IC89") (pin "1") (pinfunction "I0_1") (pintype "input"))
      (node (ref "SV1") (pin "JJ") (pinfunction "30_JJ") (pintype "bidirectional"))
      (node (ref "SV8") (pin "JJ") (pinfunction "30_JJ") (pintype "bidirectional"))
    )
    (net (code "122") (name "I{slash}O_TS04") (class "Default")
      (node (ref "SV1") (pin "NN") (pinfunction "34_NN") (pintype "bidirectional"))
      (node (ref "SV8") (pin "NN") (pinfunction "34_NN") (pintype "bidirectional"))
    )
    (net (code "123") (name "I{slash}~{O_0_TO_AC_B05}") (class "Default")
      (node (ref "IC46") (pin "13") (pinfunction "O_13") (pintype "output"))
      (node (ref "IC50") (pin "6") (pinfunction "I0_6") (pintype "input"))
      (node (ref "IC50") (pin "7") (pinfunction "I1_7") (pintype "input"))
    )
    (net (code "124") (name "I{slash}~{O_0_TO_AC}") (class "Default")
      (node (ref "IC50") (pin "5") (pinfunction "O_5") (pintype "open_collector"))
      (node (ref "SV10") (pin "DD") (pinfunction "26_DD") (pintype "bidirectional"))
      (node (ref "SV3") (pin "DD") (pinfunction "26_DD") (pintype "bidirectional"))
    )
    (net (code "125") (name "I{slash}~{O_1_TO_CA_INH_B05}") (class "Default")
      (node (ref "IC48") (pin "1") (pinfunction "O_1") (pintype "output"))
      (node (ref "IC53") (pin "1") (pinfunction "I0_1") (pintype "input"))
      (node (ref "IC53") (pin "2") (pinfunction "I1_2") (pintype "input"))
    )
    (net (code "126") (name "I{slash}~{O_1_TO_CA_INH}") (class "Default")
      (node (ref "IC53") (pin "3") (pinfunction "O_3") (pintype "open_collector"))
      (node (ref "SV12") (pin "Z") (pinfunction "22_Z") (pintype "bidirectional"))
      (node (ref "SV5") (pin "Z") (pinfunction "22_Z") (pintype "bidirectional"))
    )
    (net (code "127") (name "I{slash}~{O_ADDR_ACC}") (class "Default")
      (node (ref "IC82") (pin "13") (pinfunction "I1_13") (pintype "input"))
      (node (ref "SV11") (pin "JJ") (pinfunction "30_JJ") (pintype "bidirectional"))
      (node (ref "SV4") (pin "JJ") (pinfunction "30_JJ") (pintype "bidirectional"))
    )
    (net (code "128") (name "I{slash}~{O_BMB_03}") (class "Default")
      (node (ref "SV2") (pin "T") (pinfunction "16_T") (pintype "bidirectional"))
      (node (ref "SV9") (pin "T") (pinfunction "16_T") (pintype "bidirectional"))
    )
    (net (code "129") (name "I{slash}~{O_BMB_04}") (class "Default")
      (node (ref "SV2") (pin "BB") (pinfunction "24_BB") (pintype "bidirectional"))
      (node (ref "SV9") (pin "BB") (pinfunction "24_BB") (pintype "bidirectional"))
    )
    (net (code "130") (name "I{slash}~{O_BMB_05}") (class "Default")
      (node (ref "SV2") (pin "LL") (pinfunction "32_LL") (pintype "bidirectional"))
      (node (ref "SV9") (pin "LL") (pinfunction "32_LL") (pintype "bidirectional"))
    )
    (net (code "131") (name "I{slash}~{O_BMB_06}") (class "Default")
      (node (ref "SV2") (pin "F") (pinfunction "6_F") (pintype "bidirectional"))
      (node (ref "SV9") (pin "F") (pinfunction "6_F") (pintype "bidirectional"))
    )
    (net (code "132") (name "I{slash}~{O_BMB_07}") (class "Default")
      (node (ref "SV2") (pin "R") (pinfunction "14_R") (pintype "bidirectional"))
      (node (ref "SV9") (pin "R") (pinfunction "14_R") (pintype "bidirectional"))
    )
    (net (code "133") (name "I{slash}~{O_BMB_08}") (class "Default")
      (node (ref "IC86") (pin "6") (pinfunction "I5_6") (pintype "input"))
      (node (ref "SV2") (pin "Z") (pinfunction "22_Z") (pintype "bidirectional"))
      (node (ref "SV9") (pin "Z") (pinfunction "22_Z") (pintype "bidirectional"))
    )
    (net (code "134") (name "I{slash}~{O_BRK_RQ_B05}") (class "Default")
      (node (ref "IC46") (pin "1") (pinfunction "O_1") (pintype "output"))
      (node (ref "IC49") (pin "1") (pinfunction "I0_1") (pintype "input"))
      (node (ref "IC49") (pin "2") (pinfunction "I1_2") (pintype "input"))
    )
    (net (code "135") (name "I{slash}~{O_BRK_RQ}") (class "Default")
      (node (ref "IC49") (pin "3") (pinfunction "O_3") (pintype "open_collector"))
      (node (ref "SV11") (pin "V") (pinfunction "18_V") (pintype "bidirectional"))
      (node (ref "SV4") (pin "V") (pinfunction "18_V") (pintype "bidirectional"))
    )
    (net (code "136") (name "I{slash}~{O_BWC0}") (class "Default")
      (node (ref "IC79") (pin "10") (pinfunction "I1_10") (pintype "input"))
      (node (ref "SV12") (pin "DD") (pinfunction "26_DD") (pintype "bidirectional"))
      (node (ref "SV5") (pin "DD") (pinfunction "26_DD") (pintype "bidirectional"))
    )
    (net (code "137") (name "I{slash}~{O_INT_RQ_B05}") (class "Default")
      (node (ref "IC46") (pin "4") (pinfunction "O_4") (pintype "output"))
      (node (ref "IC49") (pin "6") (pinfunction "I0_6") (pintype "input"))
      (node (ref "IC49") (pin "7") (pinfunction "I1_7") (pintype "input"))
    )
    (net (code "138") (name "I{slash}~{O_INT_RQ}") (class "Default")
      (node (ref "IC49") (pin "5") (pinfunction "O_5") (pintype "open_collector"))
      (node (ref "SV10") (pin "Z") (pinfunction "22_Z") (pintype "bidirectional"))
      (node (ref "SV3") (pin "Z") (pinfunction "22_Z") (pintype "bidirectional"))
    )
    (net (code "139") (name "I{slash}~{O_SKP_RQ_B05}") (class "Default")
      (node (ref "IC46") (pin "10") (pinfunction "O_10") (pintype "output"))
      (node (ref "IC50") (pin "1") (pinfunction "I0_1") (pintype "input"))
      (node (ref "IC50") (pin "2") (pinfunction "I1_2") (pintype "input"))
    )
    (net (code "140") (name "I{slash}~{O_SKP_RQ}") (class "Default")
      (node (ref "IC50") (pin "3") (pinfunction "O_3") (pintype "open_collector"))
      (node (ref "SV10") (pin "V") (pinfunction "18_V") (pintype "bidirectional"))
      (node (ref "SV3") (pin "V") (pinfunction "18_V") (pintype "bidirectional"))
    )
    (net (code "141") (name "LDMF") (class "Default")
      (node (ref "IC116") (pin "11") (pinfunction "CLK_11") (pintype "input"))
      (node (ref "IC137") (pin "11") (pinfunction "CLK_11") (pintype "input"))
      (node (ref "IC137") (pin "3") (pinfunction "CLK_3") (pintype "input"))
      (node (ref "IC88") (pin "10") (pinfunction "O_10") (pintype "output"))
    )
    (net (code "142") (name "LPB_00") (class "Default")
      (node (ref "IC127") (pin "12") (pinfunction "Q_12") (pintype "output"))
      (node (ref "IC97") (pin "5") (pinfunction "2D_5") (pintype "input"))
      (node (ref "M916_9") (pin "T2") (pinfunction "P$2_T2") (pintype "bidirectional"))
    )
    (net (code "143") (name "LPB_01") (class "Default")
      (node (ref "IC128") (pin "12") (pinfunction "Q_12") (pintype "output"))
      (node (ref "IC99") (pin "10") (pinfunction "1E_10") (pintype "input"))
      (node (ref "M916_9") (pin "U2") (pinfunction "P$2_U2") (pintype "bidirectional"))
    )
    (net (code "144") (name "LPB_02") (class "Default")
      (node (ref "IC129") (pin "12") (pinfunction "Q_12") (pintype "output"))
      (node (ref "IC98") (pin "5") (pinfunction "2D_5") (pintype "input"))
      (node (ref "M916_9") (pin "V2") (pinfunction "P$2_V2") (pintype "bidirectional"))
    )
    (net (code "145") (name "LPB_03") (class "Default")
      (node (ref "IC127") (pin "9") (pinfunction "Q_9") (pintype "output"))
      (node (ref "IC97") (pin "10") (pinfunction "1E_10") (pintype "input"))
      (node (ref "M916_10") (pin "A2") (pinfunction "P$2_A2") (pintype "bidirectional"))
    )
    (net (code "146") (name "LPB_04") (class "Default")
      (node (ref "IC128") (pin "9") (pinfunction "Q_9") (pintype "output"))
      (node (ref "IC98") (pin "10") (pinfunction "1E_10") (pintype "input"))
      (node (ref "M916_10") (pin "B2") (pinfunction "P$2_B2") (pintype "bidirectional"))
    )
    (net (code "147") (name "LPB_05") (class "Default")
      (node (ref "IC129") (pin "9") (pinfunction "Q_9") (pintype "output"))
      (node (ref "IC99") (pin "5") (pinfunction "2D_5") (pintype "input"))
      (node (ref "M916_10") (pin "C2") (pinfunction "P$2_C2") (pintype "bidirectional"))
    )
    (net (code "148") (name "LPB_NOT_EQ_1") (class "Default")
      (node (ref "IC12") (pin "5") (pinfunction "I1_5") (pintype "input"))
      (node (ref "IC135") (pin "8") (pinfunction "O_8") (pintype "output"))
    )
    (net (code "149") (name "LPB_TO_DTB") (class "Default")
      (node (ref "IC15") (pin "12") (pinfunction "O_12") (pintype "output"))
      (node (ref "IC97") (pin "4") (pinfunction "2C_4") (pintype "input"))
      (node (ref "IC97") (pin "9") (pinfunction "1D_9") (pintype "input"))
      (node (ref "IC98") (pin "4") (pinfunction "2C_4") (pintype "input"))
      (node (ref "IC98") (pin "9") (pinfunction "1D_9") (pintype "input"))
      (node (ref "IC99") (pin "4") (pinfunction "2C_4") (pintype "input"))
      (node (ref "IC99") (pin "9") (pinfunction "1D_9") (pintype "input"))
    )
    (net (code "150") (name "MC00") (class "Default")
      (node (ref "IC133") (pin "5") (pinfunction "I4_5") (pintype "input"))
      (node (ref "IC73") (pin "12") (pinfunction "D_12") (pintype "input"))
      (node (ref "IC73") (pin "5") (pinfunction "Q_5") (pintype "output"))
      (node (ref "M916_10") (pin "S1") (pinfunction "P$2_S1") (pintype "bidirectional"))
    )
    (net (code "151") (name "MC01") (class "Default")
      (node (ref "IC6") (pin "11") (pinfunction "CLK_11") (pintype "input"))
      (node (ref "IC73") (pin "9") (pinfunction "Q_9") (pintype "output"))
      (node (ref "IC74") (pin "2") (pinfunction "D_2") (pintype "input"))
      (node (ref "IC91") (pin "13") (pinfunction "I1_13") (pintype "input"))
      (node (ref "M916_10") (pin "T1") (pinfunction "P$2_T1") (pintype "bidirectional"))
    )
    (net (code "152") (name "MC02") (class "Default")
      (node (ref "IC141") (pin "10") (pinfunction "I1_10") (pintype "input"))
      (node (ref "IC141") (pin "9") (pinfunction "I0_9") (pintype "input"))
      (node (ref "IC69") (pin "10") (pinfunction "I1_10") (pintype "input"))
      (node (ref "IC74") (pin "5") (pinfunction "Q_5") (pintype "output"))
      (node (ref "M916_10") (pin "U1") (pinfunction "P$2_U1") (pintype "bidirectional"))
    )
    (net (code "153") (name "MF00") (class "Default")
      (node (ref "IC116") (pin "9") (pinfunction "Q_9") (pintype "output"))
      (node (ref "M916_9") (pin "V1") (pinfunction "P$2_V1") (pintype "bidirectional"))
    )
    (net (code "154") (name "MF01") (class "Default")
      (node (ref "IC137") (pin "5") (pinfunction "Q_5") (pintype "output"))
      (node (ref "M916_10") (pin "A1") (pinfunction "P$2_A1") (pintype "bidirectional"))
    )
    (net (code "155") (name "MF02") (class "Default")
      (node (ref "IC137") (pin "9") (pinfunction "Q_9") (pintype "output"))
      (node (ref "M916_10") (pin "B1") (pinfunction "P$2_B1") (pintype "bidirectional"))
    )
    (net (code "156") (name "MKT") (class "Default")
      (node (ref "IC118") (pin "9") (pinfunction "I0_9") (pintype "input"))
      (node (ref "IC72") (pin "10") (pinfunction "I1_10") (pintype "input"))
      (node (ref "IC75") (pin "9") (pinfunction "Q_9") (pintype "output"))
      (node (ref "IC78") (pin "4") (pinfunction "I0_4") (pintype "input"))
      (node (ref "M916_10") (pin "H2") (pinfunction "P$2_H2") (pintype "bidirectional"))
    )
    (net (code "157") (name "MKTK") (class "Default")
      (node (ref "IC6") (pin "8") (pinfunction "~{Q}_8") (pintype "output"))
      (node (ref "M916_9") (pin "P1") (pinfunction "P$2_P1") (pintype "bidirectional"))
    )
    (net (code "158") (name "MK_BLK_END") (class "Default")
      (node (ref "IC10") (pin "12") (pinfunction "I2_12") (pintype "input"))
      (node (ref "M916_17") (pin "U1") (pinfunction "P$2_U1") (pintype "bidirectional"))
    )
    (net (code "159") (name "MK_BLK_MK") (class "Default")
      (node (ref "IC133") (pin "1") (pinfunction "I0_1") (pintype "input"))
      (node (ref "IC133") (pin "2") (pinfunction "I1_2") (pintype "input"))
      (node (ref "M916_18") (pin "E2") (pinfunction "P$2_E2") (pintype "bidirectional"))
    )
    (net (code "160") (name "MK_BLK_START") (class "Default")
      (node (ref "M916_18") (pin "J2") (pinfunction "P$2_J2") (pintype "bidirectional"))
    )
    (net (code "161") (name "MK_BLK_SYNC") (class "Default")
      (node (ref "M916_17") (pin "S2") (pinfunction "P$2_S2") (pintype "bidirectional"))
    )
    (net (code "162") (name "MK_DATA") (class "Default")
      (node (ref "M916_17") (pin "P2") (pinfunction "P$2_P2") (pintype "bidirectional"))
    )
    (net (code "163") (name "MK_DATA_SYNC") (class "Default")
      (node (ref "M916_18") (pin "H1") (pinfunction "P$2_H1") (pintype "bidirectional"))
    )
    (net (code "164") (name "MK_END") (class "Default")
      (node (ref "IC5") (pin "2") (pinfunction "D_2") (pintype "input"))
      (node (ref "M916_18") (pin "F2") (pinfunction "P$2_F2") (pintype "bidirectional"))
    )
    (net (code "165") (name "MOVE") (class "Default")
      (node (ref "IC124") (pin "8") (pinfunction "O_8") (pintype "output"))
    )
    (net (code "166") (name "MR00") (class "Default")
      (node (ref "IC57") (pin "9") (pinfunction "Q_9") (pintype "output"))
      (node (ref "IC76") (pin "12") (pinfunction "D_12") (pintype "input"))
      (node (ref "M916_9") (pin "D1") (pinfunction "P$2_D1") (pintype "bidirectional"))
    )
    (net (code "167") (name "MR01") (class "Default")
      (node (ref "IC108") (pin "2") (pinfunction "I1_2") (pintype "input"))
      (node (ref "IC96") (pin "9") (pinfunction "Q_9") (pintype "output"))
      (node (ref "M916_9") (pin "E1") (pinfunction "P$2_E1") (pintype "bidirectional"))
    )
    (net (code "168") (name "N$1") (class "Default")
      (node (ref "IC55") (pin "5") (pinfunction "I_5") (pintype "input"))
      (node (ref "IC61") (pin "3") (pinfunction "O_3") (pintype "output"))
    )
    (net (code "169") (name "N$2") (class "Default")
      (node (ref "IC113") (pin "6") (pinfunction "O_6") (pintype "output"))
      (node (ref "IC121") (pin "10") (pinfunction "I1_10") (pintype "input"))
      (node (ref "IC121") (pin "12") (pinfunction "I2_12") (pintype "input"))
      (node (ref "IC121") (pin "13") (pinfunction "I3_13") (pintype "input"))
      (node (ref "IC121") (pin "9") (pinfunction "I0_9") (pintype "input"))
    )
    (net (code "170") (name "N$3") (class "Default")
      (node (ref "IC15") (pin "5") (pinfunction "I_5") (pintype "input"))
      (node (ref "IC69") (pin "6") (pinfunction "O_6") (pintype "output"))
    )
    (net (code "171") (name "N$4") (class "Default")
      (node (ref "M916_19") (pin "R2") (pinfunction "P$2_R2") (pintype "bidirectional"))
      (node (ref "M916_19") (pin "S2") (pinfunction "P$2_S2") (pintype "bidirectional"))
    )
    (net (code "172") (name "N$5") (class "Default")
      (node (ref "IC122") (pin "6") (pinfunction "O_6") (pintype "output"))
      (node (ref "M916_2") (pin "H2") (pinfunction "P$2_H2") (pintype "bidirectional"))
    )
    (net (code "173") (name "N$6") (class "Default")
      (node (ref "IC140") (pin "1") (pinfunction "I0_1") (pintype "input"))
      (node (ref "IC140") (pin "2") (pinfunction "I1_2") (pintype "input"))
      (node (ref "IC140") (pin "4") (pinfunction "I2_4") (pintype "input"))
      (node (ref "IC140") (pin "5") (pinfunction "I3_5") (pintype "input"))
      (node (ref "M916_19") (pin "F2") (pinfunction "P$2_F2") (pintype "bidirectional"))
    )
    (net (code "174") (name "N$7") (class "Default")
      (node (ref "IC17") (pin "11") (pinfunction "O_11") (pintype "output"))
      (node (ref "IC17") (pin "5") (pinfunction "I1_5") (pintype "input"))
      (node (ref "IC18") (pin "4") (pinfunction "I0_4") (pintype "input"))
    )
    (net (code "175") (name "N$8") (class "Default")
      (node (ref "IC123") (pin "13") (pinfunction "I_13") (pintype "input"))
      (node (ref "M916_23") (pin "F2") (pinfunction "P$2_F2") (pintype "bidirectional"))
    )
    (net (code "176") (name "N$10") (class "Default")
      (node (ref "IC71") (pin "1") (pinfunction "I0_1") (pintype "input"))
      (node (ref "IC91") (pin "8") (pinfunction "O_8") (pintype "output"))
    )
    (net (code "177") (name "N$11") (class "Default")
      (node (ref "IC71") (pin "5") (pinfunction "I3_5") (pintype "input"))
      (node (ref "IC91") (pin "11") (pinfunction "O_11") (pintype "output"))
    )
    (net (code "178") (name "N$12") (class "Default")
      (node (ref "M916_23") (pin "D2") (pinfunction "P$2_D2") (pintype "bidirectional"))
      (node (ref "M916_23") (pin "E2") (pinfunction "P$2_E2") (pintype "bidirectional"))
    )
    (net (code "179") (name "N$13") (class "Default")
      (node (ref "IC61") (pin "8") (pinfunction "O_8") (pintype "output"))
      (node (ref "M916_1") (pin "H2") (pinfunction "P$2_H2") (pintype "bidirectional"))
      (node (ref "M916_1") (pin "J2") (pinfunction "P$2_J2") (pintype "bidirectional"))
      (node (ref "M916_1") (pin "K2") (pinfunction "P$2_K2") (pintype "bidirectional"))
    )
    (net (code "180") (name "N$14") (class "Default")
      (node (ref "M916_2") (pin "D2") (pinfunction "P$2_D2") (pintype "bidirectional"))
      (node (ref "M916_2") (pin "E2") (pinfunction "P$2_E2") (pintype "bidirectional"))
    )
    (net (code "181") (name "N$15") (class "Default")
      (node (ref "IC113") (pin "9") (pinfunction "I_9") (pintype "input"))
      (node (ref "M916_2") (pin "F2") (pinfunction "P$2_F2") (pintype "bidirectional"))
    )
    (net (code "182") (name "N$16") (class "Default")
      (node (ref "IC113") (pin "8") (pinfunction "O_8") (pintype "output"))
      (node (ref "IC19") (pin "4") (pinfunction "I2_4") (pintype "input"))
      (node (ref "IC19") (pin "5") (pinfunction "I3_5") (pintype "input"))
    )
    (net (code "183") (name "N$17") (class "Default")
      (node (ref "IC77") (pin "11") (pinfunction "CLK_11") (pintype "input"))
      (node (ref "IC77") (pin "3") (pinfunction "CLK_3") (pintype "input"))
      (node (ref "M916_21") (pin "D2") (pinfunction "P$2_D2") (pintype "bidirectional"))
    )
    (net (code "184") (name "N$18") (class "Default")
      (node (ref "IC61") (pin "11") (pinfunction "O_11") (pintype "output"))
      (node (ref "M916_1") (pin "M2") (pinfunction "P$2_M2") (pintype "bidirectional"))
      (node (ref "M916_1") (pin "N2") (pinfunction "P$2_N2") (pintype "bidirectional"))
      (node (ref "M916_1") (pin "P2") (pinfunction "P$2_P2") (pintype "bidirectional"))
    )
    (net (code "185") (name "N$19") (class "Default")
      (node (ref "M916_1") (pin "H1") (pinfunction "P$2_H1") (pintype "bidirectional"))
      (node (ref "M916_1") (pin "L2") (pinfunction "P$2_L2") (pintype "bidirectional"))
    )
    (net (code "186") (name "N$20") (class "Default")
      (node (ref "M916_2") (pin "R2") (pinfunction "P$2_R2") (pintype "bidirectional"))
      (node (ref "M916_2") (pin "S2") (pinfunction "P$2_S2") (pintype "bidirectional"))
    )
    (net (code "187") (name "N$21") (class "Default")
      (node (ref "M916_1") (pin "D2") (pinfunction "P$2_D2") (pintype "bidirectional"))
      (node (ref "M916_1") (pin "E2") (pinfunction "P$2_E2") (pintype "bidirectional"))
    )
    (net (code "188") (name "N$22") (class "Default")
      (node (ref "IC16") (pin "1") (pinfunction "I_1") (pintype "input"))
      (node (ref "M916_1") (pin "T2") (pinfunction "P$2_T2") (pintype "bidirectional"))
    )
    (net (code "189") (name "N$23") (class "Default")
      (node (ref "IC15") (pin "9") (pinfunction "I_9") (pintype "input"))
      (node (ref "M916_1") (pin "F2") (pinfunction "P$2_F2") (pintype "bidirectional"))
    )
    (net (code "190") (name "N$24") (class "Default")
      (node (ref "IC120") (pin "8") (pinfunction "O_8") (pintype "output"))
      (node (ref "M916_11") (pin "K2") (pinfunction "P$2_K2") (pintype "bidirectional"))
    )
    (net (code "191") (name "N$25") (class "Default")
      (node (ref "M916_1") (pin "R2") (pinfunction "P$2_R2") (pintype "bidirectional"))
      (node (ref "M916_1") (pin "V2") (pinfunction "P$2_V2") (pintype "bidirectional"))
    )
    (net (code "192") (name "N$26") (class "Default")
      (node (ref "M916_1") (pin "S1") (pinfunction "P$2_S1") (pintype "bidirectional"))
      (node (ref "M916_1") (pin "S2") (pinfunction "P$2_S2") (pintype "bidirectional"))
    )
    (net (code "193") (name "N$27") (class "Default")
      (node (ref "M916_21") (pin "N2") (pinfunction "P$2_N2") (pintype "bidirectional"))
      (node (ref "M916_21") (pin "S2") (pinfunction "P$2_S2") (pintype "bidirectional"))
    )
    (net (code "194") (name "N$28") (class "Default")
      (node (ref "IC109") (pin "12") (pinfunction "O_12") (pintype "output"))
      (node (ref "IC72") (pin "2") (pinfunction "I1_2") (pintype "input"))
    )
    (net (code "195") (name "N$29") (class "Default")
      (node (ref "M916_11") (pin "D2") (pinfunction "P$2_D2") (pintype "bidirectional"))
      (node (ref "M916_11") (pin "E2") (pinfunction "P$2_E2") (pintype "bidirectional"))
    )
    (net (code "196") (name "N$30") (class "Default")
      (node (ref "IC113") (pin "13") (pinfunction "I_13") (pintype "input"))
      (node (ref "M916_11") (pin "F2") (pinfunction "P$2_F2") (pintype "bidirectional"))
    )
    (net (code "197") (name "N$31") (class "Default")
      (node (ref "IC113") (pin "12") (pinfunction "O_12") (pintype "output"))
      (node (ref "IC20") (pin "10") (pinfunction "I1_10") (pintype "input"))
      (node (ref "IC20") (pin "9") (pinfunction "I0_9") (pintype "input"))
    )
    (net (code "198") (name "N$32") (class "Default")
      (node (ref "IC123") (pin "5") (pinfunction "I_5") (pintype "input"))
      (node (ref "IC78") (pin "8") (pinfunction "O_8") (pintype "output"))
    )
    (net (code "199") (name "N$33") (class "Default")
      (node (ref "IC66") (pin "6") (pinfunction "O_6") (pintype "output"))
      (node (ref "IC7") (pin "10") (pinfunction "PRE_10") (pintype "input"))
    )
    (net (code "200") (name "N$34") (class "Default")
      (node (ref "IC124") (pin "5") (pinfunction "I_5") (pintype "input"))
      (node (ref "M916_22") (pin "T2") (pinfunction "P$2_T2") (pintype "bidirectional"))
    )
    (net (code "201") (name "N$35") (class "Default")
      (node (ref "IC104") (pin "8") (pinfunction "1Y_8") (pintype "output"))
      (node (ref "IC8") (pin "9") (pinfunction "I0_9") (pintype "input"))
    )
    (net (code "202") (name "N$36") (class "Default")
      (node (ref "IC116") (pin "2") (pinfunction "D_2") (pintype "input"))
      (node (ref "IC94") (pin "12") (pinfunction "O_12") (pintype "output"))
    )
    (net (code "203") (name "N$37") (class "Default")
      (node (ref "M916_11") (pin "R2") (pinfunction "P$2_R2") (pintype "bidirectional"))
      (node (ref "M916_11") (pin "S2") (pinfunction "P$2_S2") (pintype "bidirectional"))
    )
    (net (code "204") (name "N$38") (class "Default")
      (node (ref "IC117") (pin "12") (pinfunction "I0_12") (pintype "input"))
      (node (ref "IC117") (pin "3") (pinfunction "O_3") (pintype "output"))
    )
    (net (code "205") (name "N$39") (class "Default")
      (node (ref "IC117") (pin "13") (pinfunction "I1_13") (pintype "input"))
      (node (ref "IC117") (pin "6") (pinfunction "O_6") (pintype "output"))
    )
    (net (code "206") (name "N$40") (class "Default")
      (node (ref "M916_20") (pin "M2") (pinfunction "P$2_M2") (pintype "bidirectional"))
      (node (ref "M916_20") (pin "V2") (pinfunction "P$2_V2") (pintype "bidirectional"))
    )
    (net (code "207") (name "N$41") (class "Default")
      (node (ref "M916_20") (pin "P1") (pinfunction "P$2_P1") (pintype "bidirectional"))
      (node (ref "M916_20") (pin "V1") (pinfunction "P$2_V1") (pintype "bidirectional"))
    )
    (net (code "208") (name "N$42") (class "Default")
      (node (ref "IC106") (pin "12") (pinfunction "I0_12") (pintype "input"))
      (node (ref "IC106") (pin "6") (pinfunction "O_6") (pintype "output"))
    )
    (net (code "209") (name "N$43") (class "Default")
      (node (ref "IC18") (pin "12") (pinfunction "I0_12") (pintype "input"))
      (node (ref "IC18") (pin "3") (pinfunction "O_3") (pintype "output"))
    )
    (net (code "210") (name "N$44") (class "Default")
      (node (ref "IC106") (pin "11") (pinfunction "O_11") (pintype "output"))
      (node (ref "IC72") (pin "13") (pinfunction "I3_13") (pintype "input"))
    )
    (net (code "211") (name "N$45") (class "Default")
      (node (ref "IC18") (pin "13") (pinfunction "I1_13") (pintype "input"))
      (node (ref "IC18") (pin "8") (pinfunction "O_8") (pintype "output"))
    )
    (net (code "212") (name "N$46") (class "Default")
      (node (ref "IC11") (pin "11") (pinfunction "O_11") (pintype "output"))
      (node (ref "IC8") (pin "12") (pinfunction "I2_12") (pintype "input"))
    )
    (net (code "213") (name "N$47") (class "Default")
      (node (ref "IC68") (pin "8") (pinfunction "O_8") (pintype "output"))
      (node (ref "IC94") (pin "13") (pinfunction "I_13") (pintype "input"))
    )
    (net (code "214") (name "N$48") (class "Default")
      (node (ref "IC107") (pin "4") (pinfunction "I0_4") (pintype "input"))
      (node (ref "IC71") (pin "6") (pinfunction "O_6") (pintype "output"))
    )
    (net (code "215") (name "N$49") (class "Default")
      (node (ref "IC68") (pin "10") (pinfunction "I1_10") (pintype "input"))
      (node (ref "IC70") (pin "8") (pinfunction "O_8") (pintype "output"))
    )
    (net (code "216") (name "N$50") (class "Default")
      (node (ref "IC110") (pin "12") (pinfunction "O_12") (pintype "output"))
      (node (ref "IC118") (pin "12") (pinfunction "I0_12") (pintype "input"))
    )
    (net (code "217") (name "N$51") (class "Default")
      (node (ref "IC108") (pin "4") (pinfunction "I1_4") (pintype "input"))
      (node (ref "IC72") (pin "8") (pinfunction "O_8") (pintype "output"))
    )
    (net (code "218") (name "N$52") (class "Default")
      (node (ref "IC107") (pin "6") (pinfunction "O_6") (pintype "output"))
      (node (ref "IC108") (pin "3") (pinfunction "I0_3") (pintype "input"))
    )
    (net (code "219") (name "N$53") (class "Default")
      (node (ref "IC118") (pin "13") (pinfunction "I1_13") (pintype "input"))
      (node (ref "IC118") (pin "6") (pinfunction "O_6") (pintype "output"))
    )
    (net (code "220") (name "N$54") (class "Default")
      (node (ref "IC106") (pin "3") (pinfunction "O_3") (pintype "output"))
      (node (ref "IC108") (pin "5") (pinfunction "I2_5") (pintype "input"))
    )
    (net (code "221") (name "N$55") (class "Default")
      (node (ref "IC68") (pin "9") (pinfunction "I0_9") (pintype "input"))
      (node (ref "IC70") (pin "6") (pinfunction "O_6") (pintype "output"))
    )
    (net (code "222") (name "N$56") (class "Default")
      (node (ref "IC2") (pin "6") (pinfunction "O_6") (pintype "output"))
      (node (ref "IC68") (pin "11") (pinfunction "I2_11") (pintype "input"))
    )
    (net (code "223") (name "N$58") (class "Default")
      (node (ref "IC15") (pin "11") (pinfunction "I_11") (pintype "input"))
      (node (ref "IC61") (pin "6") (pinfunction "O_6") (pintype "output"))
    )
    (net (code "224") (name "N$59") (class "Default")
      (node (ref "IC107") (pin "11") (pinfunction "O_11") (pintype "output"))
      (node (ref "IC112") (pin "13") (pinfunction "I_13") (pintype "input"))
    )
    (net (code "225") (name "N$60") (class "Default")
      (node (ref "IC108") (pin "8") (pinfunction "O_8") (pintype "output"))
      (node (ref "IC72") (pin "1") (pinfunction "I0_1") (pintype "input"))
    )
    (net (code "226") (name "N$61") (class "Default")
      (node (ref "IC110") (pin "6") (pinfunction "O_6") (pintype "output"))
      (node (ref "IC72") (pin "4") (pinfunction "I2_4") (pintype "input"))
    )
    (net (code "227") (name "N$62") (class "Default")
      (node (ref "IC71") (pin "8") (pinfunction "O_8") (pintype "output"))
      (node (ref "IC72") (pin "5") (pinfunction "I3_5") (pintype "input"))
    )
    (net (code "228") (name "N$63") (class "Default")
      (node (ref "IC74") (pin "10") (pinfunction "PRE_10") (pintype "input"))
      (node (ref "IC78") (pin "3") (pinfunction "O_3") (pintype "output"))
    )
    (net (code "229") (name "N$64") (class "Default")
      (node (ref "IC17") (pin "8") (pinfunction "O_8") (pintype "output"))
      (node (ref "IC65") (pin "4") (pinfunction "I2_4") (pintype "input"))
      (node (ref "IC65") (pin "5") (pinfunction "I3_5") (pintype "input"))
    )
    (net (code "230") (name "N$65") (class "Default")
      (node (ref "IC107") (pin "12") (pinfunction "I0_12") (pintype "input"))
      (node (ref "IC107") (pin "8") (pinfunction "O_8") (pintype "output"))
    )
    (net (code "231") (name "N$66") (class "Default")
      (node (ref "IC17") (pin "3") (pinfunction "O_3") (pintype "output"))
      (node (ref "IC65") (pin "1") (pinfunction "I0_1") (pintype "input"))
      (node (ref "IC65") (pin "2") (pinfunction "I1_2") (pintype "input"))
    )
    (net (code "232") (name "N$67") (class "Default")
      (node (ref "IC134") (pin "8") (pinfunction "O_8") (pintype "output"))
      (node (ref "M916_20") (pin "J2") (pinfunction "P$2_J2") (pintype "bidirectional"))
    )
    (net (code "233") (name "N$68") (class "Default")
      (node (ref "M916_20") (pin "D2") (pinfunction "P$2_D2") (pintype "bidirectional"))
      (node (ref "M916_20") (pin "H1") (pinfunction "P$2_H1") (pintype "bidirectional"))
    )
    (net (code "234") (name "N$69") (class "Default")
      (node (ref "M916_20") (pin "A1") (pinfunction "P$2_A1") (pintype "bidirectional"))
      (node (ref "M916_20") (pin "C1") (pinfunction "P$2_C1") (pintype "bidirectional"))
    )
    (net (code "235") (name "N$70") (class "Default")
      (node (ref "IC2") (pin "9") (pinfunction "I0_9") (pintype "input"))
      (node (ref "IC68") (pin "6") (pinfunction "O_6") (pintype "output"))
    )
    (net (code "236") (name "N$71") (class "Default")
      (node (ref "IC113") (pin "11") (pinfunction "I_11") (pintype "input"))
      (node (ref "IC78") (pin "6") (pinfunction "O_6") (pintype "output"))
    )
    (net (code "237") (name "N$72") (class "Default")
      (node (ref "IC2") (pin "11") (pinfunction "I2_11") (pintype "input"))
      (node (ref "IC68") (pin "12") (pinfunction "O_12") (pintype "output"))
    )
    (net (code "238") (name "N$73") (class "Default")
      (node (ref "IC60") (pin "6") (pinfunction "O_6") (pintype "output"))
      (node (ref "IC63") (pin "10") (pinfunction "PRE_10") (pintype "input"))
    )
    (net (code "239") (name "N$76") (class "Default")
      (node (ref "IC115") (pin "11") (pinfunction "CLK_11") (pintype "input"))
      (node (ref "IC119") (pin "3") (pinfunction "O_3") (pintype "output"))
    )
    (net (code "240") (name "N$77") (class "Default")
      (node (ref "IC2") (pin "8") (pinfunction "O_8") (pintype "output"))
      (node (ref "IC65") (pin "9") (pinfunction "I0_9") (pintype "input"))
    )
    (net (code "241") (name "N$78") (class "Default")
      (node (ref "IC113") (pin "10") (pinfunction "O_10") (pintype "output"))
      (node (ref "IC65") (pin "13") (pinfunction "I3_13") (pintype "input"))
    )
    (net (code "242") (name "N$79") (class "Default")
      (node (ref "IC112") (pin "6") (pinfunction "O_6") (pintype "output"))
      (node (ref "IC115") (pin "10") (pinfunction "PRE_10") (pintype "input"))
    )
    (net (code "243") (name "N$80") (class "Default")
      (node (ref "IC8") (pin "13") (pinfunction "I3_13") (pintype "input"))
      (node (ref "M916_14") (pin "U2") (pinfunction "P$2_U2") (pintype "bidirectional"))
    )
    (net (code "244") (name "N$81") (class "Default")
      (node (ref "IC108") (pin "12") (pinfunction "O_12") (pintype "output"))
      (node (ref "IC112") (pin "5") (pinfunction "I_5") (pintype "input"))
    )
    (net (code "245") (name "N$82") (class "Default")
      (node (ref "IC123") (pin "1") (pinfunction "I_1") (pintype "input"))
      (node (ref "IC69") (pin "8") (pinfunction "O_8") (pintype "output"))
    )
    (net (code "246") (name "N$83") (class "Default")
      (node (ref "IC5") (pin "12") (pinfunction "D_12") (pintype "input"))
      (node (ref "IC8") (pin "8") (pinfunction "O_8") (pintype "output"))
    )
    (net (code "247") (name "N$84") (class "Default")
      (node (ref "IC11") (pin "3") (pinfunction "O_3") (pintype "output"))
      (node (ref "IC11") (pin "4") (pinfunction "I0_4") (pintype "input"))
    )
    (net (code "248") (name "N$85") (class "Default")
      (node (ref "IC11") (pin "2") (pinfunction "I1_2") (pintype "input"))
      (node (ref "IC11") (pin "6") (pinfunction "O_6") (pintype "output"))
      (node (ref "IC78") (pin "12") (pinfunction "I0_12") (pintype "input"))
    )
    (net (code "249") (name "N$86") (class "Default")
      (node (ref "IC69") (pin "13") (pinfunction "I2_13") (pintype "input"))
      (node (ref "IC78") (pin "11") (pinfunction "O_11") (pintype "output"))
    )
    (net (code "250") (name "N$88") (class "Default")
      (node (ref "M916_23") (pin "R2") (pinfunction "P$2_R2") (pintype "bidirectional"))
      (node (ref "M916_23") (pin "S2") (pinfunction "P$2_S2") (pintype "bidirectional"))
    )
    (net (code "251") (name "N$91") (class "Default")
      (node (ref "IC60") (pin "11") (pinfunction "O_11") (pintype "output"))
      (node (ref "IC64") (pin "4") (pinfunction "PRE_4") (pintype "input"))
    )
    (net (code "252") (name "N$92") (class "Default")
      (node (ref "IC59") (pin "11") (pinfunction "O_11") (pintype "output"))
      (node (ref "IC62") (pin "10") (pinfunction "PRE_10") (pintype "input"))
    )
    (net (code "253") (name "N$93") (class "Default")
      (node (ref "IC127") (pin "14") (pinfunction "J_14") (pintype "input"))
      (node (ref "IC127") (pin "3") (pinfunction "K_3") (pintype "input"))
      (node (ref "IC130") (pin "6") (pinfunction "2Y_6") (pintype "output"))
    )
    (net (code "254") (name "N$94") (class "Default")
      (node (ref "IC127") (pin "10") (pinfunction "K_10") (pintype "input"))
      (node (ref "IC127") (pin "7") (pinfunction "J_7") (pintype "input"))
      (node (ref "IC130") (pin "8") (pinfunction "1Y_8") (pintype "output"))
    )
    (net (code "255") (name "N$95") (class "Default")
      (node (ref "IC128") (pin "14") (pinfunction "J_14") (pintype "input"))
      (node (ref "IC128") (pin "3") (pinfunction "K_3") (pintype "input"))
      (node (ref "IC132") (pin "8") (pinfunction "1Y_8") (pintype "output"))
    )
    (net (code "256") (name "N$96") (class "Default")
      (node (ref "IC129") (pin "14") (pinfunction "J_14") (pintype "input"))
      (node (ref "IC129") (pin "3") (pinfunction "K_3") (pintype "input"))
      (node (ref "IC131") (pin "6") (pinfunction "2Y_6") (pintype "output"))
    )
    (net (code "257") (name "N$97") (class "Default")
      (node (ref "IC59") (pin "3") (pinfunction "O_3") (pintype "output"))
      (node (ref "IC62") (pin "4") (pinfunction "PRE_4") (pintype "input"))
    )
    (net (code "258") (name "N$99") (class "Default")
      (node (ref "IC129") (pin "10") (pinfunction "K_10") (pintype "input"))
      (node (ref "IC129") (pin "7") (pinfunction "J_7") (pintype "input"))
      (node (ref "IC132") (pin "6") (pinfunction "2Y_6") (pintype "output"))
    )
    (net (code "259") (name "N$100") (class "Default")
      (node (ref "IC128") (pin "10") (pinfunction "K_10") (pintype "input"))
      (node (ref "IC128") (pin "7") (pinfunction "J_7") (pintype "input"))
      (node (ref "IC131") (pin "8") (pinfunction "1Y_8") (pintype "output"))
    )
    (net (code "260") (name "N$101") (class "Default")
      (node (ref "IC124") (pin "4") (pinfunction "O_4") (pintype "output"))
      (node (ref "IC127") (pin "5") (pinfunction "CLK_5") (pintype "input"))
      (node (ref "IC128") (pin "5") (pinfunction "CLK_5") (pintype "input"))
      (node (ref "IC129") (pin "5") (pinfunction "CLK_5") (pintype "input"))
    )
    (net (code "261") (name "N$103") (class "Default")
      (node (ref "IC123") (pin "10") (pinfunction "O_10") (pintype "output"))
      (node (ref "IC127") (pin "1") (pinfunction "CLK_1") (pintype "input"))
      (node (ref "IC128") (pin "1") (pinfunction "CLK_1") (pintype "input"))
      (node (ref "IC129") (pin "1") (pinfunction "CLK_1") (pintype "input"))
    )
    (net (code "262") (name "N$104") (class "Default")
      (node (ref "IC101") (pin "10") (pinfunction "PRE_10") (pintype "input"))
      (node (ref "IC97") (pin "8") (pinfunction "1Y_8") (pintype "output"))
    )
    (net (code "263") (name "N$105") (class "Default")
      (node (ref "IC4") (pin "9") (pinfunction "I_9") (pintype "input"))
      (node (ref "IC8") (pin "6") (pinfunction "O_6") (pintype "output"))
    )
    (net (code "264") (name "N$106") (class "Default")
      (node (ref "IC4") (pin "8") (pinfunction "O_8") (pintype "output"))
      (node (ref "IC9") (pin "13") (pinfunction "I3_13") (pintype "input"))
    )
    (net (code "265") (name "N$107") (class "Default")
      (node (ref "IC6") (pin "12") (pinfunction "D_12") (pintype "input"))
      (node (ref "IC9") (pin "8") (pinfunction "O_8") (pintype "output"))
    )
    (net (code "266") (name "N$108") (class "Default")
      (node (ref "IC103") (pin "8") (pinfunction "1Y_8") (pintype "output"))
      (node (ref "IC123") (pin "11") (pinfunction "I_11") (pintype "input"))
    )
    (net (code "267") (name "N$109") (class "Default")
      (node (ref "IC105") (pin "6") (pinfunction "2Y_6") (pintype "output"))
      (node (ref "IC124") (pin "3") (pinfunction "I_3") (pintype "input"))
    )
    (net (code "268") (name "N$111") (class "Default")
      (node (ref "IC10") (pin "13") (pinfunction "I3_13") (pintype "input"))
      (node (ref "IC124") (pin "2") (pinfunction "O_2") (pintype "output"))
    )
    (net (code "269") (name "N$112") (class "Default")
      (node (ref "IC59") (pin "6") (pinfunction "O_6") (pintype "output"))
      (node (ref "IC64") (pin "10") (pinfunction "PRE_10") (pintype "input"))
    )
    (net (code "270") (name "N$113") (class "Default")
      (node (ref "IC59") (pin "8") (pinfunction "O_8") (pintype "output"))
      (node (ref "IC63") (pin "4") (pinfunction "PRE_4") (pintype "input"))
    )
    (net (code "271") (name "N$114") (class "Default")
      (node (ref "IC10") (pin "8") (pinfunction "O_8") (pintype "output"))
      (node (ref "IC15") (pin "13") (pinfunction "I_13") (pintype "input"))
    )
    (net (code "272") (name "N$115") (class "Default")
      (node (ref "IC118") (pin "8") (pinfunction "O_8") (pintype "output"))
      (node (ref "IC124") (pin "1") (pinfunction "I_1") (pintype "input"))
    )
    (net (code "273") (name "N$116") (class "Default")
      (node (ref "IC113") (pin "1") (pinfunction "I_1") (pintype "input"))
      (node (ref "IC118") (pin "3") (pinfunction "O_3") (pintype "output"))
    )
    (net (code "274") (name "N$117") (class "Default")
      (node (ref "IC109") (pin "6") (pinfunction "O_6") (pintype "output"))
      (node (ref "IC142") (pin "4") (pinfunction "I2_4") (pintype "input"))
      (node (ref "IC142") (pin "5") (pinfunction "I3_5") (pintype "input"))
    )
    (net (code "275") (name "N$118") (class "Default")
      (node (ref "IC106") (pin "8") (pinfunction "O_8") (pintype "output"))
      (node (ref "IC142") (pin "1") (pinfunction "I0_1") (pintype "input"))
      (node (ref "IC142") (pin "2") (pinfunction "I1_2") (pintype "input"))
    )
    (net (code "276") (name "N$119") (class "Default")
      (node (ref "IC112") (pin "11") (pinfunction "I_11") (pintype "input"))
      (node (ref "IC117") (pin "8") (pinfunction "O_8") (pintype "output"))
    )
    (net (code "277") (name "N$123") (class "Default")
      (node (ref "M916_3") (pin "D2") (pinfunction "P$2_D2") (pintype "bidirectional"))
      (node (ref "M916_3") (pin "J2") (pinfunction "P$2_J2") (pintype "bidirectional"))
      (node (ref "SV7") (pin "10") (pinfunction "10_10") (pintype "passive"))
    )
    (net (code "278") (name "N$124") (class "Default")
      (node (ref "IC12") (pin "11") (pinfunction "O_11") (pintype "output"))
      (node (ref "IC4") (pin "11") (pinfunction "I_11") (pintype "input"))
    )
    (net (code "279") (name "N$125") (class "Default")
      (node (ref "IC12") (pin "6") (pinfunction "O_6") (pintype "output"))
      (node (ref "IC7") (pin "2") (pinfunction "D_2") (pintype "input"))
    )
    (net (code "280") (name "N$126") (class "Default")
      (node (ref "M916_3") (pin "E2") (pinfunction "P$2_E2") (pintype "bidirectional"))
      (node (ref "M916_3") (pin "K2") (pinfunction "P$2_K2") (pintype "bidirectional"))
      (node (ref "SV7") (pin "12") (pinfunction "12_12") (pintype "passive"))
    )
    (net (code "281") (name "N$127") (class "Default")
      (node (ref "M916_12") (pin "D2") (pinfunction "P$2_D2") (pintype "bidirectional"))
      (node (ref "M916_12") (pin "J2") (pinfunction "P$2_J2") (pintype "bidirectional"))
      (node (ref "SV7") (pin "22") (pinfunction "22_22") (pintype "passive"))
    )
    (net (code "282") (name "N$128") (class "Default")
      (node (ref "IC4") (pin "10") (pinfunction "O_10") (pintype "output"))
      (node (ref "IC7") (pin "3") (pinfunction "CLK_3") (pintype "input"))
    )
    (net (code "283") (name "N$129") (class "Default")
      (node (ref "IC102") (pin "10") (pinfunction "PRE_10") (pintype "input"))
      (node (ref "IC99") (pin "6") (pinfunction "2Y_6") (pintype "output"))
    )
    (net (code "284") (name "N$130") (class "Default")
      (node (ref "M916_12") (pin "E2") (pinfunction "P$2_E2") (pintype "bidirectional"))
      (node (ref "M916_12") (pin "K2") (pinfunction "P$2_K2") (pintype "bidirectional"))
      (node (ref "SV7") (pin "24") (pinfunction "24_24") (pintype "passive"))
    )
    (net (code "285") (name "N$131") (class "Default")
      (node (ref "M916_4") (pin "D2") (pinfunction "P$2_D2") (pintype "bidirectional"))
      (node (ref "M916_4") (pin "J2") (pinfunction "P$2_J2") (pintype "bidirectional"))
      (node (ref "SV7") (pin "32") (pinfunction "32_32") (pintype "passive"))
    )
    (net (code "286") (name "N$132") (class "Default")
      (node (ref "IC4") (pin "12") (pinfunction "O_12") (pintype "output"))
      (node (ref "IC6") (pin "4") (pinfunction "PRE_4") (pintype "input"))
    )
    (net (code "287") (name "N$133") (class "Default")
      (node (ref "M916_4") (pin "E2") (pinfunction "P$2_E2") (pintype "bidirectional"))
      (node (ref "M916_4") (pin "K2") (pinfunction "P$2_K2") (pintype "bidirectional"))
      (node (ref "SV6") (pin "6") (pinfunction "6_6") (pintype "passive"))
    )
    (net (code "288") (name "N$134") (class "Default")
      (node (ref "M916_13") (pin "D2") (pinfunction "P$2_D2") (pintype "bidirectional"))
      (node (ref "M916_13") (pin "J2") (pinfunction "P$2_J2") (pintype "bidirectional"))
      (node (ref "SV6") (pin "12") (pinfunction "12_12") (pintype "passive"))
    )
    (net (code "289") (name "N$135") (class "Default")
      (node (ref "M916_13") (pin "E2") (pinfunction "P$2_E2") (pintype "bidirectional"))
      (node (ref "M916_13") (pin "K2") (pinfunction "P$2_K2") (pintype "bidirectional"))
      (node (ref "SV6") (pin "14") (pinfunction "14_14") (pintype "passive"))
    )
    (net (code "290") (name "N$136") (class "Default")
      (node (ref "M916_5") (pin "D2") (pinfunction "P$2_D2") (pintype "bidirectional"))
      (node (ref "M916_5") (pin "J2") (pinfunction "P$2_J2") (pintype "bidirectional"))
      (node (ref "SV6") (pin "22") (pinfunction "22_22") (pintype "passive"))
    )
    (net (code "291") (name "N$137") (class "Default")
      (node (ref "IC13") (pin "6") (pinfunction "O_6") (pintype "output"))
      (node (ref "IC4") (pin "13") (pinfunction "I_13") (pintype "input"))
    )
    (net (code "292") (name "N$138") (class "Default")
      (node (ref "IC13") (pin "5") (pinfunction "I1_5") (pintype "input"))
      (node (ref "IC9") (pin "6") (pinfunction "O_6") (pintype "output"))
    )
    (net (code "293") (name "N$139") (class "Default")
      (node (ref "IC13") (pin "3") (pinfunction "O_3") (pintype "output"))
      (node (ref "IC13") (pin "4") (pinfunction "I0_4") (pintype "input"))
    )
    (net (code "294") (name "N$140") (class "Default")
      (node (ref "M916_5") (pin "E2") (pinfunction "P$2_E2") (pintype "bidirectional"))
      (node (ref "M916_5") (pin "K2") (pinfunction "P$2_K2") (pintype "bidirectional"))
      (node (ref "SV6") (pin "24") (pinfunction "24_24") (pintype "passive"))
    )
    (net (code "295") (name "N$142") (class "Default")
      (node (ref "IC102") (pin "4") (pinfunction "PRE_4") (pintype "input"))
      (node (ref "IC98") (pin "8") (pinfunction "1Y_8") (pintype "output"))
    )
    (net (code "296") (name "N$146") (class "Default")
      (node (ref "IC100") (pin "4") (pinfunction "PRE_4") (pintype "input"))
      (node (ref "IC97") (pin "6") (pinfunction "2Y_6") (pintype "output"))
    )
    (net (code "297") (name "N$147") (class "Default")
      (node (ref "IC100") (pin "10") (pinfunction "PRE_10") (pintype "input"))
      (node (ref "IC99") (pin "8") (pinfunction "1Y_8") (pintype "output"))
    )
    (net (code "298") (name "N$148") (class "Default")
      (node (ref "IC101") (pin "4") (pinfunction "PRE_4") (pintype "input"))
      (node (ref "IC98") (pin "6") (pinfunction "2Y_6") (pintype "output"))
    )
    (net (code "299") (name "N$150") (class "Default")
      (node (ref "M916_22") (pin "S1") (pinfunction "P$2_S1") (pintype "bidirectional"))
      (node (ref "M916_22") (pin "S2") (pinfunction "P$2_S2") (pintype "bidirectional"))
    )
    (net (code "300") (name "N$151") (class "Default")
      (node (ref "M916_22") (pin "R2") (pinfunction "P$2_R2") (pintype "bidirectional"))
      (node (ref "M916_22") (pin "V2") (pinfunction "P$2_V2") (pintype "bidirectional"))
    )
    (net (code "301") (name "N$153") (class "Default")
      (node (ref "IC11") (pin "8") (pinfunction "O_8") (pintype "output"))
      (node (ref "IC12") (pin "2") (pinfunction "I1_2") (pintype "input"))
    )
    (net (code "302") (name "N$155") (class "Default")
      (node (ref "IC105") (pin "8") (pinfunction "1Y_8") (pintype "output"))
      (node (ref "IC114") (pin "12") (pinfunction "D_12") (pintype "input"))
    )
    (net (code "303") (name "N$161") (class "Default")
      (node (ref "IC10") (pin "6") (pinfunction "O_6") (pintype "output"))
      (node (ref "IC14") (pin "1") (pinfunction "I_1") (pintype "input"))
    )
    (net (code "304") (name "N$162") (class "Default")
      (node (ref "IC13") (pin "10") (pinfunction "I1_10") (pintype "input"))
      (node (ref "IC13") (pin "12") (pinfunction "I0_12") (pintype "input"))
      (node (ref "IC14") (pin "2") (pinfunction "O_2") (pintype "output"))
    )
    (net (code "305") (name "N$185") (class "Default")
      (node (ref "IC103") (pin "6") (pinfunction "2Y_6") (pintype "output"))
      (node (ref "IC114") (pin "2") (pinfunction "D_2") (pintype "input"))
    )
    (net (code "306") (name "N$193") (class "Default")
      (node (ref "IC104") (pin "6") (pinfunction "2Y_6") (pintype "output"))
      (node (ref "IC115") (pin "2") (pinfunction "D_2") (pintype "input"))
    )
    (net (code "307") (name "PAR") (class "Default")
      (node (ref "IC7") (pin "6") (pinfunction "~{Q}_6") (pintype "output"))
      (node (ref "M916_9") (pin "T1") (pinfunction "P$2_T1") (pintype "bidirectional"))
    )
    (net (code "308") (name "PC+ES") (class "Default")
      (node (ref "IC13") (pin "8") (pinfunction "O_8") (pintype "output"))
      (node (ref "IC14") (pin "9") (pinfunction "I_9") (pintype "input"))
    )
    (net (code "309") (name "PWR_CLR") (class "Default")
      (node (ref "IC93") (pin "12") (pinfunction "O_12") (pintype "output"))
    )
    (net (code "310") (name "RD+WD") (class "Default")
      (node (ref "IC109") (pin "2") (pinfunction "I1_2") (pintype "input"))
      (node (ref "IC60") (pin "8") (pinfunction "O_8") (pintype "output"))
      (node (ref "IC71") (pin "9") (pinfunction "I0_9") (pintype "input"))
      (node (ref "IC9") (pin "4") (pinfunction "I2_4") (pintype "input"))
    )
    (net (code "311") (name "RDD_00") (class "Default")
      (node (ref "IC130") (pin "4") (pinfunction "2C_4") (pintype "input"))
      (node (ref "IC130") (pin "9") (pinfunction "1D_9") (pintype "input"))
      (node (ref "IC63") (pin "12") (pinfunction "D_12") (pintype "input"))
      (node (ref "M916_5") (pin "U2") (pinfunction "P$2_U2") (pintype "bidirectional"))
    )
    (net (code "312") (name "RDD_01") (class "Default")
      (node (ref "IC131") (pin "9") (pinfunction "1D_9") (pintype "input"))
      (node (ref "IC132") (pin "9") (pinfunction "1D_9") (pintype "input"))
      (node (ref "IC64") (pin "2") (pinfunction "D_2") (pintype "input"))
      (node (ref "M916_13") (pin "U2") (pinfunction "P$2_U2") (pintype "bidirectional"))
    )
    (net (code "313") (name "RDD_02") (class "Default")
      (node (ref "IC131") (pin "4") (pinfunction "2C_4") (pintype "input"))
      (node (ref "IC132") (pin "4") (pinfunction "2C_4") (pintype "input"))
      (node (ref "IC62") (pin "12") (pinfunction "D_12") (pintype "input"))
      (node (ref "M916_4") (pin "U2") (pinfunction "P$2_U2") (pintype "bidirectional"))
    )
    (net (code "314") (name "RDMK") (class "Default")
      (node (ref "M916_12") (pin "U2") (pinfunction "P$2_U2") (pintype "bidirectional"))
      (node (ref "M916_18") (pin "S2") (pinfunction "P$2_S2") (pintype "bidirectional"))
    )
    (net (code "315") (name "RD_EN") (class "Default")
      (node (ref "IC106") (pin "5") (pinfunction "I1_5") (pintype "input"))
      (node (ref "IC107") (pin "3") (pinfunction "O_3") (pintype "output"))
    )
    (net (code "316") (name "RD_EN_LPB_00-02") (class "Default")
      (node (ref "IC103") (pin "1") (pinfunction "1A_1") (pintype "input"))
      (node (ref "IC113") (pin "2") (pinfunction "O_2") (pintype "output"))
      (node (ref "IC130") (pin "5") (pinfunction "2D_5") (pintype "input"))
      (node (ref "IC131") (pin "5") (pinfunction "2D_5") (pintype "input"))
      (node (ref "IC132") (pin "10") (pinfunction "1E_10") (pintype "input"))
    )
    (net (code "317") (name "RD_EN_LPB_03-05") (class "Default")
      (node (ref "IC105") (pin "2") (pinfunction "2A_2") (pintype "input"))
      (node (ref "IC112") (pin "10") (pinfunction "O_10") (pintype "output"))
      (node (ref "IC130") (pin "10") (pinfunction "1E_10") (pintype "input"))
      (node (ref "IC131") (pin "10") (pinfunction "1E_10") (pintype "input"))
      (node (ref "IC132") (pin "5") (pinfunction "2D_5") (pintype "input"))
    )
    (net (code "318") (name "READ_ALL") (class "Default")
      (node (ref "IC126") (pin "2") (pinfunction "O_2") (pintype "output"))
    )
    (net (code "319") (name "READ_DATA") (class "Default")
      (node (ref "IC106") (pin "4") (pinfunction "I0_4") (pintype "input"))
      (node (ref "IC12") (pin "4") (pinfunction "I0_4") (pintype "input"))
      (node (ref "IC124") (pin "12") (pinfunction "O_12") (pintype "output"))
    )
    (net (code "320") (name "RSTA") (class "Default")
      (node (ref "IC55") (pin "12") (pinfunction "O_12") (pintype "output"))
    )
    (net (code "321") (name "RSTB") (class "Default")
      (node (ref "IC88") (pin "8") (pinfunction "O_8") (pintype "output"))
    )
    (net (code "322") (name "SE") (class "Default")
      (node (ref "IC126") (pin "10") (pinfunction "O_10") (pintype "output"))
    )
    (net (code "323") (name "SEARCH") (class "Default")
      (node (ref "IC106") (pin "1") (pinfunction "I0_1") (pintype "input"))
      (node (ref "IC124") (pin "10") (pinfunction "O_10") (pintype "output"))
    )
    (net (code "324") (name "SEL") (class "Default")
      (node (ref "IC5") (pin "9") (pinfunction "Q_9") (pintype "output"))
      (node (ref "M916_9") (pin "S1") (pinfunction "P$2_S1") (pintype "bidirectional"))
    )
    (net (code "325") (name "SHIFT_CK") (class "Default")
      (node (ref "IC123") (pin "2") (pinfunction "O_2") (pintype "output"))
      (node (ref "M916_17") (pin "R2") (pinfunction "P$2_R2") (pintype "bidirectional"))
    )
    (net (code "326") (name "SH_DTB") (class "Default")
      (node (ref "IC100") (pin "11") (pinfunction "CLK_11") (pintype "input"))
      (node (ref "IC100") (pin "3") (pinfunction "CLK_3") (pintype "input"))
      (node (ref "IC101") (pin "11") (pinfunction "CLK_11") (pintype "input"))
      (node (ref "IC101") (pin "3") (pinfunction "CLK_3") (pintype "input"))
      (node (ref "IC102") (pin "11") (pinfunction "CLK_11") (pintype "input"))
      (node (ref "IC102") (pin "3") (pinfunction "CLK_3") (pintype "input"))
      (node (ref "IC13") (pin "2") (pinfunction "I1_2") (pintype "input"))
      (node (ref "IC62") (pin "11") (pinfunction "CLK_11") (pintype "input"))
      (node (ref "IC62") (pin "3") (pinfunction "CLK_3") (pintype "input"))
      (node (ref "IC63") (pin "11") (pinfunction "CLK_11") (pintype "input"))
      (node (ref "IC63") (pin "3") (pinfunction "CLK_3") (pintype "input"))
      (node (ref "IC64") (pin "11") (pinfunction "CLK_11") (pintype "input"))
      (node (ref "IC64") (pin "3") (pinfunction "CLK_3") (pintype "input"))
      (node (ref "IC65") (pin "6") (pinfunction "O_6") (pintype "output"))
    )
    (net (code "327") (name "SH_EN") (class "Default")
      (node (ref "IC103") (pin "2") (pinfunction "2A_2") (pintype "input"))
      (node (ref "IC104") (pin "2") (pinfunction "2A_2") (pintype "input"))
      (node (ref "IC105") (pin "1") (pinfunction "1A_1") (pintype "input"))
      (node (ref "IC15") (pin "4") (pinfunction "O_4") (pintype "output"))
      (node (ref "IC17") (pin "2") (pinfunction "I1_2") (pintype "input"))
    )
    (net (code "328") (name "SH_ST") (class "Default")
      (node (ref "IC113") (pin "5") (pinfunction "I_5") (pintype "input"))
      (node (ref "M916_18") (pin "M1") (pinfunction "P$2_M1") (pintype "bidirectional"))
    )
    (net (code "329") (name "SH_ST-B") (class "Default")
      (node (ref "IC121") (pin "8") (pinfunction "O_8") (pintype "output"))
      (node (ref "M916_17") (pin "C1") (pinfunction "P$2_C1") (pintype "bidirectional"))
    )
    (net (code "330") (name "SP_DY") (class "Default")
      (node (ref "M916_20") (pin "H2") (pinfunction "P$2_H2") (pintype "bidirectional"))
    )
    (net (code "331") (name "ST_BLK_MK") (class "Default")
      (node (ref "IC111") (pin "5") (pinfunction "I_5") (pintype "input"))
      (node (ref "M916_10") (pin "K1") (pinfunction "P$2_K1") (pintype "bidirectional"))
      (node (ref "M916_18") (pin "R2") (pinfunction "P$2_R2") (pintype "bidirectional"))
    )
    (net (code "332") (name "ST_CK") (class "Default")
      (node (ref "IC111") (pin "9") (pinfunction "I_9") (pintype "input"))
      (node (ref "IC12") (pin "12") (pinfunction "I0_12") (pintype "input"))
      (node (ref "M916_10") (pin "P1") (pinfunction "P$2_P1") (pintype "bidirectional"))
      (node (ref "M916_17") (pin "R1") (pinfunction "P$2_R1") (pintype "bidirectional"))
      (node (ref "M916_23") (pin "M2") (pinfunction "P$2_M2") (pintype "bidirectional"))
      (node (ref "M916_23") (pin "N2") (pinfunction "P$2_N2") (pintype "bidirectional"))
      (node (ref "M916_23") (pin "P2") (pinfunction "P$2_P2") (pintype "bidirectional"))
    )
    (net (code "333") (name "ST_CK_0P") (class "Default")
      (node (ref "IC109") (pin "13") (pinfunction "I2_13") (pintype "input"))
      (node (ref "IC71") (pin "13") (pinfunction "I3_13") (pintype "input"))
      (node (ref "IC94") (pin "10") (pinfunction "O_10") (pintype "output"))
    )
    (net (code "334") (name "ST_DATA") (class "Default")
      (node (ref "IC111") (pin "11") (pinfunction "I_11") (pintype "input"))
      (node (ref "IC121") (pin "6") (pinfunction "O_6") (pintype "output"))
      (node (ref "IC70") (pin "1") (pinfunction "I0_1") (pintype "input"))
    )
    (net (code "335") (name "ST_FINAL") (class "Default")
      (node (ref "IC10") (pin "10") (pinfunction "I1_10") (pintype "input"))
      (node (ref "IC111") (pin "13") (pinfunction "I_13") (pintype "input"))
      (node (ref "IC91") (pin "12") (pinfunction "I0_12") (pintype "input"))
      (node (ref "M916_10") (pin "N1") (pinfunction "P$2_N1") (pintype "bidirectional"))
      (node (ref "M916_17") (pin "L2") (pinfunction "P$2_L2") (pintype "bidirectional"))
    )
    (net (code "336") (name "ST_IDLE") (class "Default")
      (node (ref "IC112") (pin "1") (pinfunction "I_1") (pintype "input"))
      (node (ref "M916_10") (pin "R1") (pinfunction "P$2_R1") (pintype "bidirectional"))
      (node (ref "M916_17") (pin "D2") (pinfunction "P$2_D2") (pintype "bidirectional"))
    )
    (net (code "337") (name "ST_REV_CK") (class "Default")
      (node (ref "IC111") (pin "1") (pinfunction "I_1") (pintype "input"))
      (node (ref "IC141") (pin "12") (pinfunction "I2_12") (pintype "input"))
      (node (ref "IC141") (pin "13") (pinfunction "I3_13") (pintype "input"))
      (node (ref "IC68") (pin "5") (pinfunction "I2_5") (pintype "input"))
      (node (ref "IC91") (pin "9") (pinfunction "I0_9") (pintype "input"))
      (node (ref "M916_10") (pin "L1") (pinfunction "P$2_L1") (pintype "bidirectional"))
      (node (ref "M916_17") (pin "S1") (pinfunction "P$2_S1") (pintype "bidirectional"))
    )
    (net (code "338") (name "SWTM") (class "Default")
      (node (ref "IC104") (pin "10") (pinfunction "1E_10") (pintype "input"))
      (node (ref "IC110") (pin "2") (pinfunction "I1_2") (pintype "input"))
      (node (ref "IC118") (pin "4") (pinfunction "I0_4") (pintype "input"))
      (node (ref "IC2") (pin "4") (pinfunction "I1_4") (pintype "input"))
      (node (ref "IC55") (pin "1") (pinfunction "I_1") (pintype "input"))
      (node (ref "IC55") (pin "8") (pinfunction "O_8") (pintype "output"))
      (node (ref "M916_10") (pin "V2") (pinfunction "P$2_V2") (pintype "bidirectional"))
    )
    (net (code "339") (name "SYNC") (class "Default")
      (node (ref "IC66") (pin "10") (pinfunction "I1_10") (pintype "input"))
      (node (ref "IC66") (pin "9") (pinfunction "I0_9") (pintype "input"))
      (node (ref "M916_17") (pin "N2") (pinfunction "P$2_N2") (pintype "bidirectional"))
    )
    (net (code "340") (name "SYNC_EN") (class "Default")
      (node (ref "IC69") (pin "12") (pinfunction "O_12") (pintype "output"))
      (node (ref "M916_17") (pin "H1") (pinfunction "P$2_H1") (pintype "bidirectional"))
    )
    (net (code "341") (name "T3") (class "Default")
      (node (ref "IC123") (pin "12") (pinfunction "O_12") (pintype "output"))
      (node (ref "IC141") (pin "2") (pinfunction "I1_2") (pintype "input"))
      (node (ref "IC141") (pin "4") (pinfunction "I2_4") (pintype "input"))
    )
    (net (code "342") (name "TIM") (class "Default")
      (node (ref "IC6") (pin "5") (pinfunction "Q_5") (pintype "output"))
      (node (ref "M916_9") (pin "U1") (pinfunction "P$2_U1") (pintype "bidirectional"))
    )
    (net (code "343") (name "TM_EN") (class "Default")
      (node (ref "IC112") (pin "3") (pinfunction "I_3") (pintype "input"))
      (node (ref "IC118") (pin "11") (pinfunction "O_11") (pintype "output"))
      (node (ref "IC120") (pin "9") (pinfunction "I0_9") (pintype "input"))
      (node (ref "IC122") (pin "1") (pinfunction "I0_1") (pintype "input"))
      (node (ref "M916_12") (pin "R2") (pinfunction "P$2_R2") (pintype "bidirectional"))
      (node (ref "M916_3") (pin "R2") (pinfunction "P$2_R2") (pintype "bidirectional"))
    )
    (net (code "344") (name "TP00") (class "Default")
      (node (ref "IC117") (pin "5") (pinfunction "I1_5") (pintype "input"))
      (node (ref "IC19") (pin "8") (pinfunction "O_8") (pintype "output"))
      (node (ref "IC5") (pin "3") (pinfunction "CLK_3") (pintype "input"))
      (node (ref "IC66") (pin "12") (pinfunction "I2_12") (pintype "input"))
      (node (ref "IC66") (pin "13") (pinfunction "I3_13") (pintype "input"))
      (node (ref "IC66") (pin "2") (pinfunction "I1_2") (pintype "input"))
      (node (ref "IC73") (pin "11") (pinfunction "CLK_11") (pintype "input"))
      (node (ref "IC73") (pin "3") (pinfunction "CLK_3") (pintype "input"))
      (node (ref "IC74") (pin "3") (pinfunction "CLK_3") (pintype "input"))
      (node (ref "IC78") (pin "2") (pinfunction "I1_2") (pintype "input"))
      (node (ref "M916_2") (pin "M2") (pinfunction "P$2_M2") (pintype "bidirectional"))
      (node (ref "M916_2") (pin "N2") (pinfunction "P$2_N2") (pintype "bidirectional"))
      (node (ref "M916_2") (pin "P2") (pinfunction "P$2_P2") (pintype "bidirectional"))
    )
    (net (code "345") (name "TP00_A") (class "Default")
      (node (ref "IC109") (pin "4") (pinfunction "I1_4") (pintype "input"))
      (node (ref "IC20") (pin "6") (pinfunction "O_6") (pintype "output"))
      (node (ref "IC65") (pin "10") (pinfunction "I1_10") (pintype "input"))
    )
    (net (code "346") (name "TP01") (class "Default")
      (node (ref "IC106") (pin "10") (pinfunction "I1_10") (pintype "input"))
      (node (ref "IC117") (pin "2") (pinfunction "I1_2") (pintype "input"))
      (node (ref "IC17") (pin "10") (pinfunction "I1_10") (pintype "input"))
      (node (ref "IC21") (pin "6") (pinfunction "O_6") (pintype "output"))
      (node (ref "M916_11") (pin "M2") (pinfunction "P$2_M2") (pintype "bidirectional"))
      (node (ref "M916_11") (pin "N2") (pinfunction "P$2_N2") (pintype "bidirectional"))
      (node (ref "M916_11") (pin "P2") (pinfunction "P$2_P2") (pintype "bidirectional"))
      (node (ref "M916_17") (pin "F1") (pinfunction "P$2_F1") (pintype "bidirectional"))
    )
    (net (code "347") (name "TP01_A") (class "Default")
      (node (ref "IC118") (pin "10") (pinfunction "I1_10") (pintype "input"))
      (node (ref "IC21") (pin "8") (pinfunction "O_8") (pintype "output"))
      (node (ref "IC72") (pin "12") (pinfunction "I2_12") (pintype "input"))
    )
    (net (code "348") (name "T_TRK") (class "Default")
      (node (ref "IC119") (pin "2") (pinfunction "I1_2") (pintype "input"))
      (node (ref "IC61") (pin "13") (pinfunction "I1_13") (pintype "input"))
      (node (ref "M916_20") (pin "S1") (pinfunction "P$2_S1") (pintype "bidirectional"))
      (node (ref "M916_20") (pin "U1") (pinfunction "P$2_U1") (pintype "bidirectional"))
      (node (ref "M916_3") (pin "U2") (pinfunction "P$2_U2") (pintype "bidirectional"))
    )
    (net (code "349") (name "U+M_DY") (class "Default")
      (node (ref "M916_20") (pin "K1") (pinfunction "P$2_K1") (pintype "bidirectional"))
    )
    (net (code "350") (name "USR_00") (class "Default")
      (node (ref "IC1") (pin "22") (pinfunction "B_22") (pintype "input"))
      (node (ref "IC56") (pin "12") (pinfunction "Q_12") (pintype "output"))
      (node (ref "M916_9") (pin "A1") (pinfunction "P$2_A1") (pintype "bidirectional"))
    )
    (net (code "351") (name "USR_01") (class "Default")
      (node (ref "IC1") (pin "21") (pinfunction "C_21") (pintype "input"))
      (node (ref "IC56") (pin "9") (pinfunction "Q_9") (pintype "output"))
      (node (ref "M916_9") (pin "B1") (pinfunction "P$2_B1") (pintype "bidirectional"))
    )
    (net (code "352") (name "USR_02") (class "Default")
      (node (ref "IC1") (pin "20") (pinfunction "D_20") (pintype "input"))
      (node (ref "IC57") (pin "12") (pinfunction "Q_12") (pintype "output"))
      (node (ref "M916_9") (pin "C1") (pinfunction "P$2_C1") (pintype "bidirectional"))
    )
    (net (code "353") (name "USR_02_") (class "Default")
      (node (ref "IC1") (pin "18") (pinfunction "G1_18") (pintype "input"))
      (node (ref "IC1") (pin "19") (pinfunction "G2_19") (pintype "input"))
      (node (ref "IC2") (pin "12") (pinfunction "O_12") (pintype "output"))
    )
    (net (code "354") (name "UTS") (class "Default")
      (node (ref "IC11") (pin "5") (pinfunction "I1_5") (pintype "input"))
      (node (ref "IC115") (pin "8") (pinfunction "~{Q}_8") (pintype "output"))
      (node (ref "IC78") (pin "9") (pinfunction "I0_9") (pintype "input"))
      (node (ref "M916_10") (pin "J1") (pinfunction "P$2_J1") (pintype "bidirectional"))
    )
    (net (code "355") (name "VCC") (class "Default")
      (node (ref "IC103") (pin "11") (pinfunction "1F_11") (pintype "input"))
      (node (ref "IC103") (pin "13") (pinfunction "1C_13") (pintype "input"))
      (node (ref "IC104") (pin "11") (pinfunction "1F_11") (pintype "input"))
      (node (ref "IC104") (pin "13") (pinfunction "1C_13") (pintype "input"))
      (node (ref "IC105") (pin "11") (pinfunction "1F_11") (pintype "input"))
      (node (ref "IC105") (pin "13") (pinfunction "1C_13") (pintype "input"))
      (node (ref "IC130") (pin "11") (pinfunction "1F_11") (pintype "input"))
      (node (ref "IC130") (pin "13") (pinfunction "1C_13") (pintype "input"))
      (node (ref "IC131") (pin "11") (pinfunction "1F_11") (pintype "input"))
      (node (ref "IC131") (pin "13") (pinfunction "1C_13") (pintype "input"))
      (node (ref "IC132") (pin "11") (pinfunction "1F_11") (pintype "input"))
      (node (ref "IC132") (pin "13") (pinfunction "1C_13") (pintype "input"))
      (node (ref "IC97") (pin "11") (pinfunction "1F_11") (pintype "input"))
      (node (ref "IC97") (pin "13") (pinfunction "1C_13") (pintype "input"))
      (node (ref "IC98") (pin "11") (pinfunction "1F_11") (pintype "input"))
      (node (ref "IC98") (pin "13") (pinfunction "1C_13") (pintype "input"))
      (node (ref "IC99") (pin "11") (pinfunction "1F_11") (pintype "input"))
      (node (ref "IC99") (pin "13") (pinfunction "1C_13") (pintype "input"))
      (node (ref "M916_1") (pin "A2") (pinfunction "P$2_A2") (pintype "bidirectional"))
      (node (ref "M916_11") (pin "A2") (pinfunction "P$2_A2") (pintype "bidirectional"))
      (node (ref "M916_12") (pin "A2") (pinfunction "P$2_A2") (pintype "bidirectional"))
      (node (ref "M916_13") (pin "A2") (pinfunction "P$2_A2") (pintype "bidirectional"))
      (node (ref "M916_14") (pin "A2") (pinfunction "P$2_A2") (pintype "bidirectional"))
      (node (ref "M916_15") (pin "A2") (pinfunction "P$2_A2") (pintype "bidirectional"))
      (node (ref "M916_17") (pin "A2") (pinfunction "P$2_A2") (pintype "bidirectional"))
      (node (ref "M916_18") (pin "A2") (pinfunction "P$2_A2") (pintype "bidirectional"))
      (node (ref "M916_19") (pin "A2") (pinfunction "P$2_A2") (pintype "bidirectional"))
      (node (ref "M916_2") (pin "A2") (pinfunction "P$2_A2") (pintype "bidirectional"))
      (node (ref "M916_20") (pin "A2") (pinfunction "P$2_A2") (pintype "bidirectional"))
      (node (ref "M916_21") (pin "A2") (pinfunction "P$2_A2") (pintype "bidirectional"))
      (node (ref "M916_22") (pin "A2") (pinfunction "P$2_A2") (pintype "bidirectional"))
      (node (ref "M916_23") (pin "A2") (pinfunction "P$2_A2") (pintype "bidirectional"))
      (node (ref "M916_3") (pin "A2") (pinfunction "P$2_A2") (pintype "bidirectional"))
      (node (ref "M916_4") (pin "A2") (pinfunction "P$2_A2") (pintype "bidirectional"))
      (node (ref "M916_5") (pin "A2") (pinfunction "P$2_A2") (pintype "bidirectional"))
      (node (ref "M916_6") (pin "A2") (pinfunction "P$2_A2") (pintype "bidirectional"))
      (node (ref "M916_7") (pin "A2") (pinfunction "P$2_A2") (pintype "bidirectional"))
    )
    (net (code "356") (name "W+UTS") (class "Default")
      (node (ref "IC109") (pin "8") (pinfunction "O_8") (pintype "output"))
      (node (ref "IC19") (pin "1") (pinfunction "I0_1") (pintype "input"))
      (node (ref "IC20") (pin "13") (pinfunction "I3_13") (pintype "input"))
    )
    (net (code "357") (name "W-INH") (class "Default")
      (node (ref "IC7") (pin "8") (pinfunction "~{Q}_8") (pintype "output"))
    )
    (net (code "358") (name "W01") (class "Default")
      (node (ref "M916_10") (pin "J2") (pinfunction "P$2_J2") (pintype "bidirectional"))
      (node (ref "M916_17") (pin "J2") (pinfunction "P$2_J2") (pintype "bidirectional"))
    )
    (net (code "359") (name "W01-W05") (class "Default")
      (node (ref "M916_18") (pin "K1") (pinfunction "P$2_K1") (pintype "bidirectional"))
    )
    (net (code "360") (name "W02") (class "Default")
      (node (ref "M916_10") (pin "K2") (pinfunction "P$2_K2") (pintype "bidirectional"))
      (node (ref "M916_17") (pin "V2") (pinfunction "P$2_V2") (pintype "bidirectional"))
    )
    (net (code "361") (name "W03") (class "Default")
      (node (ref "M916_10") (pin "L2") (pinfunction "P$2_L2") (pintype "bidirectional"))
      (node (ref "M916_17") (pin "E2") (pinfunction "P$2_E2") (pintype "bidirectional"))
    )
    (net (code "362") (name "W04") (class "Default")
      (node (ref "M916_10") (pin "M2") (pinfunction "P$2_M2") (pintype "bidirectional"))
      (node (ref "M916_18") (pin "T2") (pinfunction "P$2_T2") (pintype "bidirectional"))
    )
    (net (code "363") (name "W05") (class "Default")
      (node (ref "M916_10") (pin "N2") (pinfunction "P$2_N2") (pintype "bidirectional"))
      (node (ref "M916_17") (pin "U2") (pinfunction "P$2_U2") (pintype "bidirectional"))
    )
    (net (code "364") (name "W06") (class "Default")
      (node (ref "M916_10") (pin "P2") (pinfunction "P$2_P2") (pintype "bidirectional"))
      (node (ref "M916_18") (pin "M2") (pinfunction "P$2_M2") (pintype "bidirectional"))
    )
    (net (code "365") (name "W07") (class "Default")
      (node (ref "M916_10") (pin "R2") (pinfunction "P$2_R2") (pintype "bidirectional"))
      (node (ref "M916_18") (pin "K2") (pinfunction "P$2_K2") (pintype "bidirectional"))
    )
    (net (code "366") (name "W08") (class "Default")
      (node (ref "M916_10") (pin "S2") (pinfunction "P$2_S2") (pintype "bidirectional"))
      (node (ref "M916_18") (pin "L1") (pinfunction "P$2_L1") (pintype "bidirectional"))
    )
    (net (code "367") (name "W09") (class "Default")
      (node (ref "M916_10") (pin "T2") (pinfunction "P$2_T2") (pintype "bidirectional"))
      (node (ref "M916_17") (pin "F2") (pinfunction "P$2_F2") (pintype "bidirectional"))
    )
    (net (code "368") (name "WB00") (class "Default")
      (node (ref "IC114") (pin "6") (pinfunction "~{Q}_6") (pintype "output"))
      (node (ref "IC130") (pin "2") (pinfunction "2A_2") (pintype "input"))
      (node (ref "M916_12") (pin "N2") (pinfunction "P$2_N2") (pintype "bidirectional"))
      (node (ref "M916_5") (pin "N2") (pinfunction "P$2_N2") (pintype "bidirectional"))
      (node (ref "M916_9") (pin "P2") (pinfunction "P$2_P2") (pintype "bidirectional"))
    )
    (net (code "369") (name "WB01") (class "Default")
      (node (ref "IC114") (pin "8") (pinfunction "~{Q}_8") (pintype "output"))
      (node (ref "IC132") (pin "1") (pinfunction "1A_1") (pintype "input"))
      (node (ref "M916_13") (pin "N2") (pinfunction "P$2_N2") (pintype "bidirectional"))
      (node (ref "M916_9") (pin "R2") (pinfunction "P$2_R2") (pintype "bidirectional"))
    )
    (net (code "370") (name "WB02") (class "Default")
      (node (ref "IC115") (pin "6") (pinfunction "~{Q}_6") (pintype "output"))
      (node (ref "IC131") (pin "2") (pinfunction "2A_2") (pintype "input"))
      (node (ref "M916_4") (pin "N2") (pinfunction "P$2_N2") (pintype "bidirectional"))
      (node (ref "M916_9") (pin "S2") (pinfunction "P$2_S2") (pintype "bidirectional"))
    )
    (net (code "371") (name "WC") (class "Default")
      (node (ref "IC138") (pin "9") (pinfunction "Q_9") (pintype "output"))
      (node (ref "IC66") (pin "1") (pinfunction "I0_1") (pintype "input"))
      (node (ref "IC68") (pin "1") (pinfunction "I0_1") (pintype "input"))
      (node (ref "M916_10") (pin "H1") (pinfunction "P$2_H1") (pintype "bidirectional"))
    )
    (net (code "372") (name "WC0") (class "Default")
      (node (ref "IC79") (pin "8") (pinfunction "O_8") (pintype "output"))
      (node (ref "IC93") (pin "9") (pinfunction "I_9") (pintype "input"))
    )
    (net (code "373") (name "WRITE_ALL") (class "Default")
      (node (ref "IC126") (pin "6") (pinfunction "O_6") (pintype "output"))
      (node (ref "IC68") (pin "13") (pinfunction "I2_13") (pintype "input"))
      (node (ref "IC7") (pin "11") (pinfunction "CLK_11") (pintype "input"))
      (node (ref "IC70") (pin "9") (pinfunction "I0_9") (pintype "input"))
    )
    (net (code "374") (name "WRITE_DATA") (class "Default")
      (node (ref "IC10") (pin "9") (pinfunction "I0_9") (pintype "input"))
      (node (ref "IC126") (pin "4") (pinfunction "O_4") (pintype "output"))
      (node (ref "IC68") (pin "4") (pinfunction "I1_4") (pintype "input"))
      (node (ref "IC70") (pin "2") (pinfunction "I1_2") (pintype "input"))
      (node (ref "IC71") (pin "4") (pinfunction "I2_4") (pintype "input"))
    )
    (net (code "375") (name "WRITE_OK") (class "Default")
      (node (ref "IC123") (pin "3") (pinfunction "I_3") (pintype "input"))
      (node (ref "IC2") (pin "5") (pinfunction "I2_5") (pintype "input"))
      (node (ref "IC78") (pin "10") (pinfunction "I1_10") (pintype "input"))
      (node (ref "M916_6") (pin "D2") (pinfunction "P$2_D2") (pintype "bidirectional"))
    )
    (net (code "376") (name "WRITE_OK+UTS") (class "Default")
      (node (ref "IC123") (pin "6") (pinfunction "O_6") (pintype "output"))
      (node (ref "IC70") (pin "13") (pinfunction "I3_13") (pintype "input"))
      (node (ref "IC70") (pin "5") (pinfunction "I3_5") (pintype "input"))
    )
    (net (code "377") (name "WRTM") (class "Default")
      (node (ref "IC104") (pin "1") (pinfunction "1A_1") (pintype "input"))
      (node (ref "IC110") (pin "1") (pinfunction "I0_1") (pintype "input"))
      (node (ref "IC126") (pin "8") (pinfunction "O_8") (pintype "output"))
      (node (ref "IC2") (pin "3") (pinfunction "I0_3") (pintype "input"))
    )
    (net (code "378") (name "WRTM+FR03") (class "Default")
      (node (ref "IC108") (pin "11") (pinfunction "I2_11") (pintype "input"))
      (node (ref "IC110") (pin "5") (pinfunction "I2_5") (pintype "input"))
      (node (ref "IC60") (pin "3") (pinfunction "O_3") (pintype "output"))
    )
    (net (code "379") (name "WR_EN") (class "Default")
      (node (ref "IC103") (pin "10") (pinfunction "1E_10") (pintype "input"))
      (node (ref "IC105") (pin "5") (pinfunction "2D_5") (pintype "input"))
      (node (ref "IC109") (pin "3") (pinfunction "I0_3") (pintype "input"))
      (node (ref "IC116") (pin "6") (pinfunction "~{Q}_6") (pintype "output"))
      (node (ref "IC117") (pin "1") (pinfunction "I0_1") (pintype "input"))
      (node (ref "IC118") (pin "5") (pinfunction "I1_5") (pintype "input"))
      (node (ref "IC130") (pin "12") (pinfunction "1B_12") (pintype "input"))
      (node (ref "IC130") (pin "3") (pinfunction "2B_3") (pintype "input"))
      (node (ref "IC131") (pin "12") (pinfunction "1B_12") (pintype "input"))
      (node (ref "IC131") (pin "3") (pinfunction "2B_3") (pintype "input"))
      (node (ref "IC132") (pin "12") (pinfunction "1B_12") (pintype "input"))
      (node (ref "IC132") (pin "3") (pinfunction "2B_3") (pintype "input"))
      (node (ref "M916_10") (pin "F1") (pinfunction "P$2_F1") (pintype "bidirectional"))
      (node (ref "M916_13") (pin "R2") (pinfunction "P$2_R2") (pintype "bidirectional"))
      (node (ref "M916_4") (pin "R2") (pinfunction "P$2_R2") (pintype "bidirectional"))
      (node (ref "M916_5") (pin "R2") (pinfunction "P$2_R2") (pintype "bidirectional"))
    )
    (net (code "380") (name "XOR_TO_LPB") (class "Default")
      (node (ref "IC103") (pin "12") (pinfunction "1B_12") (pintype "input"))
      (node (ref "IC103") (pin "9") (pinfunction "1D_9") (pintype "input"))
      (node (ref "IC105") (pin "3") (pinfunction "2B_3") (pintype "input"))
      (node (ref "IC105") (pin "4") (pinfunction "2C_4") (pintype "input"))
      (node (ref "IC142") (pin "6") (pinfunction "O_6") (pintype "output"))
    )
    (net (code "381") (name "XSAD") (class "Default")
      (node (ref "IC14") (pin "12") (pinfunction "O_12") (pintype "output"))
      (node (ref "IC9") (pin "5") (pinfunction "I3_5") (pintype "input"))
    )
    (net (code "382") (name "XSA_DY") (class "Default")
      (node (ref "IC124") (pin "6") (pinfunction "O_6") (pintype "output"))
      (node (ref "IC5") (pin "11") (pinfunction "CLK_11") (pintype "input"))
      (node (ref "IC76") (pin "11") (pinfunction "CLK_11") (pintype "input"))
      (node (ref "IC76") (pin "3") (pinfunction "CLK_3") (pintype "input"))
    )
    (net (code "383") (name "XSTA") (class "Default")
      (node (ref "IC138") (pin "11") (pinfunction "CLK_11") (pintype "input"))
      (node (ref "IC56") (pin "1") (pinfunction "CLK_1") (pintype "input"))
      (node (ref "IC56") (pin "5") (pinfunction "CLK_5") (pintype "input"))
      (node (ref "IC57") (pin "1") (pinfunction "CLK_1") (pintype "input"))
      (node (ref "IC57") (pin "5") (pinfunction "CLK_5") (pintype "input"))
      (node (ref "IC58") (pin "1") (pinfunction "CLK_1") (pintype "input"))
      (node (ref "IC58") (pin "5") (pinfunction "CLK_5") (pintype "input"))
      (node (ref "IC88") (pin "4") (pinfunction "O_4") (pintype "output"))
      (node (ref "IC95") (pin "1") (pinfunction "CLK_1") (pintype "input"))
      (node (ref "IC95") (pin "5") (pinfunction "CLK_5") (pintype "input"))
      (node (ref "IC96") (pin "1") (pinfunction "CLK_1") (pintype "input"))
      (node (ref "IC96") (pin "5") (pinfunction "CLK_5") (pintype "input"))
      (node (ref "M916_19") (pin "M2") (pinfunction "P$2_M2") (pintype "bidirectional"))
      (node (ref "M916_19") (pin "N2") (pinfunction "P$2_N2") (pintype "bidirectional"))
      (node (ref "M916_19") (pin "P2") (pinfunction "P$2_P2") (pintype "bidirectional"))
    )
    (net (code "384") (name "unconnected-(IC1A-8-Pad9)") (class "Default")
      (node (ref "IC1") (pin "9") (pinfunction "8_9") (pintype "output"))
    )
    (net (code "385") (name "unconnected-(IC1A-9-Pad10)") (class "Default")
      (node (ref "IC1") (pin "10") (pinfunction "9_10") (pintype "output"))
    )
    (net (code "386") (name "unconnected-(IC1A-10-Pad11)") (class "Default")
      (node (ref "IC1") (pin "11") (pinfunction "10_11") (pintype "output"))
    )
    (net (code "387") (name "unconnected-(IC1A-11-Pad13)") (class "Default")
      (node (ref "IC1") (pin "13") (pinfunction "11_13") (pintype "output"))
    )
    (net (code "388") (name "unconnected-(IC1A-12-Pad14)") (class "Default")
      (node (ref "IC1") (pin "14") (pinfunction "12_14") (pintype "output"))
    )
    (net (code "389") (name "unconnected-(IC1A-13-Pad15)") (class "Default")
      (node (ref "IC1") (pin "15") (pinfunction "13_15") (pintype "output"))
    )
    (net (code "390") (name "unconnected-(IC1A-14-Pad16)") (class "Default")
      (node (ref "IC1") (pin "16") (pinfunction "14_16") (pintype "output"))
    )
    (net (code "391") (name "unconnected-(IC1A-15-Pad17)") (class "Default")
      (node (ref "IC1") (pin "17") (pinfunction "15_17") (pintype "output"))
    )
    (net (code "392") (name "unconnected-(IC125A-8-Pad9)") (class "Default")
      (node (ref "IC125") (pin "9") (pinfunction "8_9") (pintype "output"))
    )
    (net (code "393") (name "unconnected-(IC125A-9-Pad10)") (class "Default")
      (node (ref "IC125") (pin "10") (pinfunction "9_10") (pintype "output"))
    )
    (net (code "394") (name "unconnected-(IC125A-10-Pad11)") (class "Default")
      (node (ref "IC125") (pin "11") (pinfunction "10_11") (pintype "output"))
    )
    (net (code "395") (name "unconnected-(IC125A-11-Pad13)") (class "Default")
      (node (ref "IC125") (pin "13") (pinfunction "11_13") (pintype "output"))
    )
    (net (code "396") (name "unconnected-(IC125A-12-Pad14)") (class "Default")
      (node (ref "IC125") (pin "14") (pinfunction "12_14") (pintype "output"))
    )
    (net (code "397") (name "unconnected-(IC125A-13-Pad15)") (class "Default")
      (node (ref "IC125") (pin "15") (pinfunction "13_15") (pintype "output"))
    )
    (net (code "398") (name "unconnected-(IC125A-14-Pad16)") (class "Default")
      (node (ref "IC125") (pin "16") (pinfunction "14_16") (pintype "output"))
    )
    (net (code "399") (name "unconnected-(IC125A-15-Pad17)") (class "Default")
      (node (ref "IC125") (pin "17") (pinfunction "15_17") (pintype "output"))
    )
    (net (code "400") (name "unconnected-(SV3-34-PadNN)") (class "Default")
      (node (ref "SV3") (pin "NN") (pinfunction "34_NN") (pintype "bidirectional"))
    )
    (net (code "401") (name "unconnected-(SV3-38-PadTT)") (class "Default")
      (node (ref "SV3") (pin "TT") (pinfunction "38_TT") (pintype "bidirectional"))
    )
    (net (code "402") (name "unconnected-(SV4-10-PadL)") (class "Default")
      (node (ref "SV4") (pin "L") (pinfunction "10_L") (pintype "bidirectional"))
    )
    (net (code "403") (name "unconnected-(SV4-14-PadR)") (class "Default")
      (node (ref "SV4") (pin "R") (pinfunction "14_R") (pintype "bidirectional"))
    )
    (net (code "404") (name "unconnected-(SV4-34-PadNN)") (class "Default")
      (node (ref "SV4") (pin "NN") (pinfunction "34_NN") (pintype "bidirectional"))
    )
    (net (code "405") (name "unconnected-(SV4-38-PadTT)") (class "Default")
      (node (ref "SV4") (pin "TT") (pinfunction "38_TT") (pintype "bidirectional"))
    )
    (net (code "406") (name "unconnected-(SV6-Pad2)") (class "Default")
      (node (ref "SV6") (pin "2") (pinfunction "2_2") (pintype "passive"))
    )
    (net (code "407") (name "unconnected-(SV6-Pad4)") (class "Default")
      (node (ref "SV6") (pin "4") (pinfunction "4_4") (pintype "passive"))
    )
    (net (code "408") (name "unconnected-(SV6-Pad16)") (class "Default")
      (node (ref "SV6") (pin "16") (pinfunction "16_16") (pintype "passive"))
    )
    (net (code "409") (name "unconnected-(SV6-Pad26)") (class "Default")
      (node (ref "SV6") (pin "26") (pinfunction "26_26") (pintype "passive"))
    )
    (net (code "410") (name "unconnected-(SV6-Pad28)") (class "Default")
      (node (ref "SV6") (pin "28") (pinfunction "28_28") (pintype "passive"))
    )
    (net (code "411") (name "unconnected-(SV6-Pad30)") (class "Default")
      (node (ref "SV6") (pin "30") (pinfunction "30_30") (pintype "passive"))
    )
    (net (code "412") (name "unconnected-(SV6-Pad32)") (class "Default")
      (node (ref "SV6") (pin "32") (pinfunction "32_32") (pintype "passive"))
    )
    (net (code "413") (name "unconnected-(SV6-Pad34)") (class "Default")
      (node (ref "SV6") (pin "34") (pinfunction "34_34") (pintype "passive"))
    )
    (net (code "414") (name "unconnected-(SV7-Pad2)") (class "Default")
      (node (ref "SV7") (pin "2") (pinfunction "2_2") (pintype "passive"))
    )
    (net (code "415") (name "unconnected-(SV7-Pad4)") (class "Default")
      (node (ref "SV7") (pin "4") (pinfunction "4_4") (pintype "passive"))
    )
    (net (code "416") (name "unconnected-(SV7-Pad6)") (class "Default")
      (node (ref "SV7") (pin "6") (pinfunction "6_6") (pintype "passive"))
    )
    (net (code "417") (name "unconnected-(SV7-Pad8)") (class "Default")
      (node (ref "SV7") (pin "8") (pinfunction "8_8") (pintype "passive"))
    )
    (net (code "418") (name "unconnected-(SV7-Pad18)") (class "Default")
      (node (ref "SV7") (pin "18") (pinfunction "18_18") (pintype "passive"))
    )
    (net (code "419") (name "unconnected-(SV7-Pad20)") (class "Default")
      (node (ref "SV7") (pin "20") (pinfunction "20_20") (pintype "passive"))
    )
    (net (code "420") (name "unconnected-(SV10-34-PadNN)") (class "Default")
      (node (ref "SV10") (pin "NN") (pinfunction "34_NN") (pintype "bidirectional"))
    )
    (net (code "421") (name "unconnected-(SV10-38-PadTT)") (class "Default")
      (node (ref "SV10") (pin "TT") (pinfunction "38_TT") (pintype "bidirectional"))
    )
    (net (code "422") (name "unconnected-(SV11-10-PadL)") (class "Default")
      (node (ref "SV11") (pin "L") (pinfunction "10_L") (pintype "bidirectional"))
    )
    (net (code "423") (name "unconnected-(SV11-14-PadR)") (class "Default")
      (node (ref "SV11") (pin "R") (pinfunction "14_R") (pintype "bidirectional"))
    )
    (net (code "424") (name "unconnected-(SV11-34-PadNN)") (class "Default")
      (node (ref "SV11") (pin "NN") (pinfunction "34_NN") (pintype "bidirectional"))
    )
    (net (code "425") (name "unconnected-(SV11-38-PadTT)") (class "Default")
      (node (ref "SV11") (pin "TT") (pinfunction "38_TT") (pintype "bidirectional"))
    )
    (net (code "426") (name "~{0_TO_AC}") (class "Default")
      (node (ref "IC46") (pin "11") (pinfunction "I0_11") (pintype "input"))
      (node (ref "IC55") (pin "6") (pinfunction "O_6") (pintype "output"))
    )
    (net (code "427") (name "~{0_TO_DTB}") (class "Default")
      (node (ref "IC100") (pin "1") (pinfunction "CLR_1") (pintype "input"))
      (node (ref "IC100") (pin "13") (pinfunction "CLR_13") (pintype "input"))
      (node (ref "IC101") (pin "1") (pinfunction "CLR_1") (pintype "input"))
      (node (ref "IC101") (pin "13") (pinfunction "CLR_13") (pintype "input"))
      (node (ref "IC102") (pin "1") (pinfunction "CLR_1") (pintype "input"))
      (node (ref "IC102") (pin "13") (pinfunction "CLR_13") (pintype "input"))
      (node (ref "IC14") (pin "11") (pinfunction "I_11") (pintype "input"))
      (node (ref "IC62") (pin "1") (pinfunction "CLR_1") (pintype "input"))
      (node (ref "IC62") (pin "13") (pinfunction "CLR_13") (pintype "input"))
      (node (ref "IC63") (pin "1") (pinfunction "CLR_1") (pintype "input"))
      (node (ref "IC63") (pin "13") (pinfunction "CLR_13") (pintype "input"))
      (node (ref "IC64") (pin "1") (pinfunction "CLR_1") (pintype "input"))
      (node (ref "IC64") (pin "13") (pinfunction "CLR_13") (pintype "input"))
      (node (ref "IC65") (pin "8") (pinfunction "O_8") (pintype "output"))
    )
    (net (code "428") (name "~{0_TO_EF}") (class "Default")
      (node (ref "IC14") (pin "4") (pinfunction "O_4") (pintype "output"))
      (node (ref "IC5") (pin "1") (pinfunction "CLR_1") (pintype "input"))
      (node (ref "IC5") (pin "13") (pinfunction "CLR_13") (pintype "input"))
      (node (ref "IC6") (pin "1") (pinfunction "CLR_1") (pintype "input"))
      (node (ref "IC6") (pin "10") (pinfunction "PRE_10") (pintype "input"))
      (node (ref "IC7") (pin "4") (pinfunction "PRE_4") (pintype "input"))
    )
    (net (code "429") (name "~{0_TO_LPB}") (class "Default")
      (node (ref "IC127") (pin "2") (pinfunction "CL_2") (pintype "input"))
      (node (ref "IC127") (pin "6") (pinfunction "CL_6") (pintype "input"))
      (node (ref "IC128") (pin "2") (pinfunction "CL_2") (pintype "input"))
      (node (ref "IC128") (pin "6") (pinfunction "CL_6") (pintype "input"))
      (node (ref "IC129") (pin "2") (pinfunction "CL_2") (pintype "input"))
      (node (ref "IC129") (pin "6") (pinfunction "CL_6") (pintype "input"))
      (node (ref "IC141") (pin "8") (pinfunction "O_8") (pintype "output"))
    )
    (net (code "430") (name "~{0_TO_STATE}") (class "Default")
      (node (ref "IC120") (pin "6") (pinfunction "O_6") (pintype "output"))
      (node (ref "M916_18") (pin "V2") (pinfunction "P$2_V2") (pintype "bidirectional"))
    )
    (net (code "431") (name "~{0_TO_STA}") (class "Default")
      (node (ref "IC15") (pin "2") (pinfunction "O_2") (pintype "output"))
      (node (ref "IC56") (pin "2") (pinfunction "CL_2") (pintype "input"))
      (node (ref "IC56") (pin "6") (pinfunction "CL_6") (pintype "input"))
      (node (ref "IC57") (pin "2") (pinfunction "CL_2") (pintype "input"))
      (node (ref "IC57") (pin "6") (pinfunction "CL_6") (pintype "input"))
      (node (ref "IC58") (pin "2") (pinfunction "CL_2") (pintype "input"))
      (node (ref "IC58") (pin "6") (pinfunction "CL_6") (pintype "input"))
      (node (ref "IC69") (pin "4") (pinfunction "I1_4") (pintype "input"))
      (node (ref "IC95") (pin "2") (pinfunction "CL_2") (pintype "input"))
      (node (ref "IC95") (pin "6") (pinfunction "CL_6") (pintype "input"))
      (node (ref "IC96") (pin "2") (pinfunction "CL_2") (pintype "input"))
    )
    (net (code "432") (name "~{0_TO_W}") (class "Default")
      (node (ref "IC67") (pin "8") (pinfunction "O_8") (pintype "output"))
      (node (ref "M916_17") (pin "H2") (pinfunction "P$2_H2") (pintype "bidirectional"))
    )
    (net (code "433") (name "~{00}") (class "Default")
      (node (ref "IC1") (pin "1") (pinfunction "0_1") (pintype "output"))
      (node (ref "IC3") (pin "1") (pinfunction "I_1") (pintype "input"))
      (node (ref "M916_15") (pin "S2") (pinfunction "P$2_S2") (pintype "bidirectional"))
    )
    (net (code "434") (name "~{01}") (class "Default")
      (node (ref "IC1") (pin "2") (pinfunction "1_2") (pintype "output"))
      (node (ref "IC3") (pin "3") (pinfunction "I_3") (pintype "input"))
      (node (ref "M916_7") (pin "N1") (pinfunction "P$2_N1") (pintype "bidirectional"))
    )
    (net (code "435") (name "~{02}") (class "Default")
      (node (ref "IC1") (pin "3") (pinfunction "2_3") (pintype "output"))
      (node (ref "IC3") (pin "5") (pinfunction "I_5") (pintype "input"))
      (node (ref "M916_7") (pin "D2") (pinfunction "P$2_D2") (pintype "bidirectional"))
    )
    (net (code "436") (name "~{03}") (class "Default")
      (node (ref "IC1") (pin "4") (pinfunction "3_4") (pintype "output"))
      (node (ref "IC3") (pin "9") (pinfunction "I_9") (pintype "input"))
      (node (ref "M916_7") (pin "E2") (pinfunction "P$2_E2") (pintype "bidirectional"))
    )
    (net (code "437") (name "~{04}") (class "Default")
      (node (ref "IC1") (pin "5") (pinfunction "4_5") (pintype "output"))
      (node (ref "IC3") (pin "11") (pinfunction "I_11") (pintype "input"))
      (node (ref "M916_7") (pin "K2") (pinfunction "P$2_K2") (pintype "bidirectional"))
    )
    (net (code "438") (name "~{05}") (class "Default")
      (node (ref "IC1") (pin "6") (pinfunction "5_6") (pintype "output"))
      (node (ref "IC3") (pin "13") (pinfunction "I_13") (pintype "input"))
      (node (ref "M916_7") (pin "L2") (pinfunction "P$2_L2") (pintype "bidirectional"))
    )
    (net (code "439") (name "~{06}") (class "Default")
      (node (ref "IC1") (pin "7") (pinfunction "6_7") (pintype "output"))
      (node (ref "IC4") (pin "1") (pinfunction "I_1") (pintype "input"))
      (node (ref "M916_7") (pin "R2") (pinfunction "P$2_R2") (pintype "bidirectional"))
    )
    (net (code "440") (name "~{07}") (class "Default")
      (node (ref "IC1") (pin "8") (pinfunction "7_8") (pintype "output"))
      (node (ref "IC4") (pin "3") (pinfunction "I_3") (pintype "input"))
      (node (ref "M916_7") (pin "S2") (pinfunction "P$2_S2") (pintype "bidirectional"))
    )
    (net (code "441") (name "~{76}") (class "Default")
      (node (ref "IC142") (pin "10") (pinfunction "I1_10") (pintype "input"))
      (node (ref "IC142") (pin "9") (pinfunction "I0_9") (pintype "input"))
      (node (ref "IC94") (pin "4") (pinfunction "O_4") (pintype "output"))
    )
    (net (code "442") (name "~{77}") (class "Default")
      (node (ref "IC142") (pin "12") (pinfunction "I2_12") (pintype "input"))
      (node (ref "IC142") (pin "13") (pinfunction "I3_13") (pintype "input"))
      (node (ref "IC94") (pin "6") (pinfunction "O_6") (pintype "output"))
    )
    (net (code "443") (name "~{ADDR_ACC}") (class "Default")
      (node (ref "IC123") (pin "8") (pinfunction "O_8") (pintype "output"))
      (node (ref "IC61") (pin "4") (pinfunction "I0_4") (pintype "input"))
    )
    (net (code "444") (name "~{B-BRK}") (class "Default")
      (node (ref "IC22") (pin "12") (pinfunction "I1_12") (pintype "input"))
      (node (ref "IC22") (pin "3") (pinfunction "I1_3") (pintype "input"))
      (node (ref "IC22") (pin "6") (pinfunction "I1_6") (pintype "input"))
      (node (ref "IC22") (pin "9") (pinfunction "I1_9") (pintype "input"))
      (node (ref "IC23") (pin "12") (pinfunction "I1_12") (pintype "input"))
      (node (ref "IC23") (pin "3") (pinfunction "I1_3") (pintype "input"))
      (node (ref "IC23") (pin "6") (pinfunction "I1_6") (pintype "input"))
      (node (ref "IC23") (pin "9") (pinfunction "I1_9") (pintype "input"))
      (node (ref "IC24") (pin "12") (pinfunction "I1_12") (pintype "input"))
      (node (ref "IC24") (pin "3") (pinfunction "I1_3") (pintype "input"))
      (node (ref "IC24") (pin "6") (pinfunction "I1_6") (pintype "input"))
      (node (ref "IC24") (pin "9") (pinfunction "I1_9") (pintype "input"))
      (node (ref "IC67") (pin "6") (pinfunction "O_6") (pintype "output"))
    )
    (net (code "445") (name "~{BAC_00}") (class "Default")
      (node (ref "IC134") (pin "1") (pinfunction "I0_1") (pintype "input"))
      (node (ref "IC16") (pin "3") (pinfunction "I_3") (pintype "input"))
      (node (ref "IC83") (pin "3") (pinfunction "O_3") (pintype "output"))
    )
    (net (code "446") (name "~{BAC_01}") (class "Default")
      (node (ref "IC134") (pin "2") (pinfunction "I1_2") (pintype "input"))
      (node (ref "IC16") (pin "9") (pinfunction "I_9") (pintype "input"))
      (node (ref "IC83") (pin "6") (pinfunction "O_6") (pintype "output"))
    )
    (net (code "447") (name "~{BAC_02}") (class "Default")
      (node (ref "IC134") (pin "3") (pinfunction "I2_3") (pintype "input"))
      (node (ref "IC16") (pin "11") (pinfunction "I_11") (pintype "input"))
      (node (ref "IC85") (pin "8") (pinfunction "O_8") (pintype "output"))
    )
    (net (code "448") (name "~{BAC_03}") (class "Default")
      (node (ref "IC134") (pin "4") (pinfunction "I3_4") (pintype "input"))
      (node (ref "IC54") (pin "1") (pinfunction "I_1") (pintype "input"))
      (node (ref "IC84") (pin "8") (pinfunction "O_8") (pintype "output"))
    )
    (net (code "449") (name "~{BAC_04}") (class "Default")
      (node (ref "IC134") (pin "5") (pinfunction "I4_5") (pintype "input"))
      (node (ref "IC54") (pin "5") (pinfunction "I_5") (pintype "input"))
      (node (ref "IC84") (pin "11") (pinfunction "O_11") (pintype "output"))
    )
    (net (code "450") (name "~{BAC_05}") (class "Default")
      (node (ref "IC54") (pin "11") (pinfunction "I_11") (pintype "input"))
      (node (ref "IC85") (pin "3") (pinfunction "O_3") (pintype "output"))
    )
    (net (code "451") (name "~{BAC_06}") (class "Default")
      (node (ref "IC54") (pin "13") (pinfunction "I_13") (pintype "input"))
      (node (ref "IC85") (pin "6") (pinfunction "O_6") (pintype "output"))
    )
    (net (code "452") (name "~{BAC_07}") (class "Default")
      (node (ref "IC55") (pin "3") (pinfunction "I_3") (pintype "input"))
      (node (ref "IC84") (pin "6") (pinfunction "O_6") (pintype "output"))
    )
    (net (code "453") (name "~{BAC_08}") (class "Default")
      (node (ref "IC16") (pin "5") (pinfunction "I_5") (pintype "input"))
      (node (ref "IC83") (pin "8") (pinfunction "O_8") (pintype "output"))
    )
    (net (code "454") (name "~{BAC_09}") (class "Default")
      (node (ref "IC16") (pin "13") (pinfunction "I_13") (pintype "input"))
      (node (ref "IC83") (pin "11") (pinfunction "O_11") (pintype "output"))
    )
    (net (code "455") (name "~{BAC_10}") (class "Default")
      (node (ref "IC11") (pin "9") (pinfunction "I0_9") (pintype "input"))
      (node (ref "IC54") (pin "3") (pinfunction "I_3") (pintype "input"))
      (node (ref "IC84") (pin "3") (pinfunction "O_3") (pintype "output"))
    )
    (net (code "456") (name "~{BAC_11}") (class "Default")
      (node (ref "IC107") (pin "10") (pinfunction "I1_10") (pintype "input"))
      (node (ref "IC54") (pin "9") (pinfunction "I_9") (pintype "input"))
      (node (ref "IC85") (pin "11") (pinfunction "O_11") (pintype "output"))
    )
    (net (code "457") (name "~{BLK_IN_SYNC}") (class "Default")
      (node (ref "IC11") (pin "1") (pinfunction "I0_1") (pintype "input"))
      (node (ref "IC112") (pin "9") (pinfunction "I_9") (pintype "input"))
      (node (ref "IC133") (pin "8") (pinfunction "O_8") (pintype "output"))
    )
    (net (code "458") (name "~{BMB_00}") (class "Default")
      (node (ref "IC79") (pin "11") (pinfunction "O_11") (pintype "output"))
      (node (ref "IC88") (pin "13") (pinfunction "I_13") (pintype "input"))
    )
    (net (code "459") (name "~{BMB_01}") (class "Default")
      (node (ref "IC80") (pin "3") (pinfunction "O_3") (pintype "output"))
      (node (ref "IC92") (pin "3") (pinfunction "I_3") (pintype "input"))
    )
    (net (code "460") (name "~{BMB_02}") (class "Default")
      (node (ref "IC82") (pin "6") (pinfunction "O_6") (pintype "output"))
      (node (ref "IC92") (pin "5") (pinfunction "I_5") (pintype "input"))
    )
    (net (code "461") (name "~{BMB_03}") (class "Default")
      (node (ref "IC81") (pin "6") (pinfunction "O_6") (pintype "output"))
      (node (ref "IC92") (pin "11") (pinfunction "I_11") (pintype "input"))
    )
    (net (code "462") (name "~{BMB_04}") (class "Default")
      (node (ref "IC81") (pin "8") (pinfunction "O_8") (pintype "output"))
      (node (ref "IC93") (pin "1") (pinfunction "I_1") (pintype "input"))
    )
    (net (code "463") (name "~{BMB_05}") (class "Default")
      (node (ref "IC81") (pin "11") (pinfunction "O_11") (pintype "output"))
      (node (ref "IC93") (pin "5") (pinfunction "I_5") (pintype "input"))
    )
    (net (code "464") (name "~{BMB_06}") (class "Default")
      (node (ref "IC82") (pin "3") (pinfunction "O_3") (pintype "output"))
      (node (ref "IC93") (pin "11") (pinfunction "I_11") (pintype "input"))
    )
    (net (code "465") (name "~{BMB_07}") (class "Default")
      (node (ref "IC81") (pin "3") (pinfunction "O_3") (pintype "output"))
      (node (ref "IC94") (pin "1") (pinfunction "I_1") (pintype "input"))
    )
    (net (code "466") (name "~{BMB_08}") (class "Default")
      (node (ref "IC80") (pin "6") (pinfunction "O_6") (pintype "output"))
      (node (ref "IC92") (pin "1") (pinfunction "I_1") (pintype "input"))
    )
    (net (code "467") (name "~{BMB_09}") (class "Default")
      (node (ref "IC80") (pin "8") (pinfunction "O_8") (pintype "output"))
      (node (ref "IC92") (pin "9") (pinfunction "I_9") (pintype "input"))
    )
    (net (code "468") (name "~{BMB_10}") (class "Default")
      (node (ref "IC80") (pin "11") (pinfunction "O_11") (pintype "output"))
      (node (ref "IC92") (pin "13") (pinfunction "I_13") (pintype "input"))
    )
    (net (code "469") (name "~{BMB_11}") (class "Default")
      (node (ref "IC82") (pin "8") (pinfunction "O_8") (pintype "output"))
      (node (ref "IC93") (pin "3") (pinfunction "I_3") (pintype "input"))
    )
    (net (code "470") (name "~{BMR00}") (class "Default")
      (node (ref "IC76") (pin "8") (pinfunction "~{Q}_8") (pintype "output"))
      (node (ref "M916_7") (pin "H1") (pinfunction "P$2_H1") (pintype "bidirectional"))
    )
    (net (code "471") (name "~{BMR01}") (class "Default")
      (node (ref "IC76") (pin "5") (pinfunction "Q_5") (pintype "output"))
      (node (ref "M916_7") (pin "A1") (pinfunction "P$2_A1") (pintype "bidirectional"))
    )
    (net (code "472") (name "~{C00}") (class "Default")
      (node (ref "IC118") (pin "2") (pinfunction "I1_2") (pintype "input"))
      (node (ref "IC18") (pin "9") (pinfunction "I0_9") (pintype "input"))
      (node (ref "IC75") (pin "11") (pinfunction "CLK_11") (pintype "input"))
      (node (ref "IC75") (pin "2") (pinfunction "D_2") (pintype "input"))
      (node (ref "IC75") (pin "6") (pinfunction "~{Q}_6") (pintype "output"))
      (node (ref "IC78") (pin "1") (pinfunction "I0_1") (pintype "input"))
    )
    (net (code "473") (name "~{C01}") (class "Default")
      (node (ref "IC109") (pin "5") (pinfunction "I2_5") (pintype "input"))
      (node (ref "IC133") (pin "4") (pinfunction "I3_4") (pintype "input"))
      (node (ref "IC18") (pin "10") (pinfunction "I1_10") (pintype "input"))
      (node (ref "IC66") (pin "4") (pinfunction "I2_4") (pintype "input"))
      (node (ref "IC74") (pin "12") (pinfunction "D_12") (pintype "input"))
      (node (ref "IC74") (pin "8") (pinfunction "~{Q}_8") (pintype "output"))
    )
    (net (code "474") (name "~{CK00}") (class "Default")
      (node (ref "IC77") (pin "12") (pinfunction "D_12") (pintype "input"))
      (node (ref "IC77") (pin "6") (pinfunction "~{Q}_6") (pintype "output"))
      (node (ref "M916_3") (pin "N2") (pinfunction "P$2_N2") (pintype "bidirectional"))
    )
    (net (code "475") (name "~{CK01}") (class "Default")
      (node (ref "IC122") (pin "2") (pinfunction "I1_2") (pintype "input"))
      (node (ref "IC122") (pin "4") (pinfunction "I2_4") (pintype "input"))
      (node (ref "IC122") (pin "5") (pinfunction "I3_5") (pintype "input"))
      (node (ref "IC77") (pin "8") (pinfunction "~{Q}_8") (pintype "output"))
    )
    (net (code "476") (name "~{CLR_DF}") (class "Default")
      (node (ref "IC138") (pin "4") (pinfunction "PRE_4") (pintype "input"))
      (node (ref "IC15") (pin "10") (pinfunction "O_10") (pintype "output"))
    )
    (net (code "477") (name "~{CLR_DTF}") (class "Default")
      (node (ref "IC112") (pin "12") (pinfunction "O_12") (pintype "output"))
      (node (ref "IC139") (pin "4") (pinfunction "PRE_4") (pintype "input"))
    )
    (net (code "478") (name "~{CSTA}") (class "Default")
      (node (ref "IC12") (pin "9") (pinfunction "I0_9") (pintype "input"))
      (node (ref "IC87") (pin "8") (pinfunction "O_8") (pintype "output"))
      (node (ref "IC88") (pin "1") (pinfunction "I_1") (pintype "input"))
    )
    (net (code "479") (name "~{DATA}") (class "Default")
      (node (ref "IC107") (pin "1") (pinfunction "I0_1") (pintype "input"))
      (node (ref "IC111") (pin "4") (pinfunction "O_4") (pintype "output"))
      (node (ref "IC121") (pin "1") (pinfunction "I0_1") (pintype "input"))
      (node (ref "IC71") (pin "2") (pinfunction "I1_2") (pintype "input"))
    )
    (net (code "480") (name "~{DB_00_B02}") (class "Default")
      (node (ref "IC22") (pin "1") (pinfunction "O_1") (pintype "output"))
      (node (ref "IC25") (pin "1") (pinfunction "I0_1") (pintype "input"))
      (node (ref "IC25") (pin "2") (pinfunction "I1_2") (pintype "input"))
    )
    (net (code "481") (name "~{DB_00}") (class "Default")
      (node (ref "IC25") (pin "3") (pinfunction "O_3") (pintype "open_collector"))
      (node (ref "SV12") (pin "D") (pinfunction "4_D") (pintype "bidirectional"))
      (node (ref "SV5") (pin "D") (pinfunction "4_D") (pintype "bidirectional"))
    )
    (net (code "482") (name "~{DB_01_B02}") (class "Default")
      (node (ref "IC22") (pin "4") (pinfunction "O_4") (pintype "output"))
      (node (ref "IC25") (pin "6") (pinfunction "I0_6") (pintype "input"))
      (node (ref "IC25") (pin "7") (pinfunction "I1_7") (pintype "input"))
    )
    (net (code "483") (name "~{DB_01}") (class "Default")
      (node (ref "IC25") (pin "5") (pinfunction "O_5") (pintype "open_collector"))
      (node (ref "SV12") (pin "J") (pinfunction "8_J") (pintype "bidirectional"))
      (node (ref "SV5") (pin "J") (pinfunction "8_J") (pintype "bidirectional"))
    )
    (net (code "484") (name "~{DB_02_B02}") (class "Default")
      (node (ref "IC22") (pin "10") (pinfunction "O_10") (pintype "output"))
      (node (ref "IC26") (pin "1") (pinfunction "I0_1") (pintype "input"))
      (node (ref "IC26") (pin "2") (pinfunction "I1_2") (pintype "input"))
    )
    (net (code "485") (name "~{DB_02}") (class "Default")
      (node (ref "IC26") (pin "3") (pinfunction "O_3") (pintype "open_collector"))
      (node (ref "SV12") (pin "N") (pinfunction "12_N") (pintype "bidirectional"))
      (node (ref "SV5") (pin "N") (pinfunction "12_N") (pintype "bidirectional"))
    )
    (net (code "486") (name "~{DB_03_B02}") (class "Default")
      (node (ref "IC22") (pin "13") (pinfunction "O_13") (pintype "output"))
      (node (ref "IC26") (pin "6") (pinfunction "I0_6") (pintype "input"))
      (node (ref "IC26") (pin "7") (pinfunction "I1_7") (pintype "input"))
    )
    (net (code "487") (name "~{DB_03}") (class "Default")
      (node (ref "IC26") (pin "5") (pinfunction "O_5") (pintype "open_collector"))
      (node (ref "SV12") (pin "T") (pinfunction "16_T") (pintype "bidirectional"))
      (node (ref "SV5") (pin "T") (pinfunction "16_T") (pintype "bidirectional"))
    )
    (net (code "488") (name "~{DB_04_B02}") (class "Default")
      (node (ref "IC23") (pin "1") (pinfunction "O_1") (pintype "output"))
      (node (ref "IC27") (pin "1") (pinfunction "I0_1") (pintype "input"))
      (node (ref "IC27") (pin "2") (pinfunction "I1_2") (pintype "input"))
    )
    (net (code "489") (name "~{DB_04}") (class "Default")
      (node (ref "IC27") (pin "3") (pinfunction "O_3") (pintype "open_collector"))
      (node (ref "SV12") (pin "X") (pinfunction "20_X") (pintype "bidirectional"))
      (node (ref "SV5") (pin "X") (pinfunction "20_X") (pintype "bidirectional"))
    )
    (net (code "490") (name "~{DB_05_B02}") (class "Default")
      (node (ref "IC23") (pin "4") (pinfunction "O_4") (pintype "output"))
      (node (ref "IC27") (pin "6") (pinfunction "I0_6") (pintype "input"))
      (node (ref "IC27") (pin "7") (pinfunction "I1_7") (pintype "input"))
    )
    (net (code "491") (name "~{DB_05}") (class "Default")
      (node (ref "IC27") (pin "5") (pinfunction "O_5") (pintype "open_collector"))
      (node (ref "SV12") (pin "BB") (pinfunction "24_BB") (pintype "bidirectional"))
      (node (ref "SV5") (pin "BB") (pinfunction "24_BB") (pintype "bidirectional"))
    )
    (net (code "492") (name "~{DB_06_B02}") (class "Default")
      (node (ref "IC23") (pin "10") (pinfunction "O_10") (pintype "output"))
      (node (ref "IC28") (pin "1") (pinfunction "I0_1") (pintype "input"))
      (node (ref "IC28") (pin "2") (pinfunction "I1_2") (pintype "input"))
    )
    (net (code "493") (name "~{DB_06}") (class "Default")
      (node (ref "IC28") (pin "3") (pinfunction "O_3") (pintype "open_collector"))
      (node (ref "SV12") (pin "FF") (pinfunction "28_FF") (pintype "bidirectional"))
      (node (ref "SV5") (pin "FF") (pinfunction "28_FF") (pintype "bidirectional"))
    )
    (net (code "494") (name "~{DB_07_B02}") (class "Default")
      (node (ref "IC23") (pin "13") (pinfunction "O_13") (pintype "output"))
      (node (ref "IC28") (pin "6") (pinfunction "I0_6") (pintype "input"))
      (node (ref "IC28") (pin "7") (pinfunction "I1_7") (pintype "input"))
    )
    (net (code "495") (name "~{DB_07}") (class "Default")
      (node (ref "IC28") (pin "5") (pinfunction "O_5") (pintype "open_collector"))
      (node (ref "SV12") (pin "LL") (pinfunction "32_LL") (pintype "bidirectional"))
      (node (ref "SV5") (pin "LL") (pinfunction "32_LL") (pintype "bidirectional"))
    )
    (net (code "496") (name "~{DB_08_B02}") (class "Default")
      (node (ref "IC24") (pin "1") (pinfunction "O_1") (pintype "output"))
      (node (ref "IC29") (pin "1") (pinfunction "I0_1") (pintype "input"))
      (node (ref "IC29") (pin "2") (pinfunction "I1_2") (pintype "input"))
    )
    (net (code "497") (name "~{DB_08}") (class "Default")
      (node (ref "IC29") (pin "3") (pinfunction "O_3") (pintype "open_collector"))
      (node (ref "SV12") (pin "RR") (pinfunction "36_RR") (pintype "bidirectional"))
      (node (ref "SV5") (pin "RR") (pinfunction "36_RR") (pintype "bidirectional"))
    )
    (net (code "498") (name "~{DB_09_B02}") (class "Default")
      (node (ref "IC24") (pin "4") (pinfunction "O_4") (pintype "output"))
      (node (ref "IC29") (pin "6") (pinfunction "I0_6") (pintype "input"))
      (node (ref "IC29") (pin "7") (pinfunction "I1_7") (pintype "input"))
    )
    (net (code "499") (name "~{DB_09}") (class "Default")
      (node (ref "IC29") (pin "5") (pinfunction "O_5") (pintype "open_collector"))
      (node (ref "SV12") (pin "F") (pinfunction "6_F") (pintype "bidirectional"))
      (node (ref "SV5") (pin "F") (pinfunction "6_F") (pintype "bidirectional"))
    )
    (net (code "500") (name "~{DB_10_B02}") (class "Default")
      (node (ref "IC24") (pin "10") (pinfunction "O_10") (pintype "output"))
      (node (ref "IC30") (pin "1") (pinfunction "I0_1") (pintype "input"))
      (node (ref "IC30") (pin "2") (pinfunction "I1_2") (pintype "input"))
    )
    (net (code "501") (name "~{DB_10}") (class "Default")
      (node (ref "IC30") (pin "3") (pinfunction "O_3") (pintype "open_collector"))
      (node (ref "SV12") (pin "L") (pinfunction "10_L") (pintype "bidirectional"))
      (node (ref "SV5") (pin "L") (pinfunction "10_L") (pintype "bidirectional"))
    )
    (net (code "502") (name "~{DB_11_B02}") (class "Default")
      (node (ref "IC24") (pin "13") (pinfunction "O_13") (pintype "output"))
      (node (ref "IC30") (pin "6") (pinfunction "I0_6") (pintype "input"))
      (node (ref "IC30") (pin "7") (pinfunction "I1_7") (pintype "input"))
    )
    (net (code "503") (name "~{DB_11}") (class "Default")
      (node (ref "IC30") (pin "5") (pinfunction "O_5") (pintype "open_collector"))
      (node (ref "SV12") (pin "R") (pinfunction "14_R") (pintype "bidirectional"))
      (node (ref "SV5") (pin "R") (pinfunction "14_R") (pintype "bidirectional"))
    )
    (net (code "504") (name "~{DF}") (class "Default")
      (node (ref "IC138") (pin "5") (pinfunction "Q_5") (pintype "output"))
      (node (ref "IC46") (pin "2") (pinfunction "I0_2") (pintype "input"))
      (node (ref "IC70") (pin "12") (pinfunction "I2_12") (pintype "input"))
    )
    (net (code "505") (name "~{DTB_00}") (class "Default")
      (node (ref "IC100") (pin "6") (pinfunction "~{Q}_6") (pintype "output"))
      (node (ref "IC22") (pin "2") (pinfunction "I0_2") (pintype "input"))
    )
    (net (code "506") (name "~{DTB_01}") (class "Default")
      (node (ref "IC100") (pin "8") (pinfunction "~{Q}_8") (pintype "output"))
      (node (ref "IC22") (pin "5") (pinfunction "I0_5") (pintype "input"))
    )
    (net (code "507") (name "~{DTB_02}") (class "Default")
      (node (ref "IC101") (pin "6") (pinfunction "~{Q}_6") (pintype "output"))
      (node (ref "IC22") (pin "8") (pinfunction "I0_8") (pintype "input"))
    )
    (net (code "508") (name "~{DTB_03}") (class "Default")
      (node (ref "IC101") (pin "8") (pinfunction "~{Q}_8") (pintype "output"))
      (node (ref "IC22") (pin "11") (pinfunction "I0_11") (pintype "input"))
    )
    (net (code "509") (name "~{DTB_04}") (class "Default")
      (node (ref "IC102") (pin "6") (pinfunction "~{Q}_6") (pintype "output"))
      (node (ref "IC23") (pin "2") (pinfunction "I0_2") (pintype "input"))
    )
    (net (code "510") (name "~{DTB_05}") (class "Default")
      (node (ref "IC102") (pin "8") (pinfunction "~{Q}_8") (pintype "output"))
      (node (ref "IC23") (pin "5") (pinfunction "I0_5") (pintype "input"))
    )
    (net (code "511") (name "~{DTB_06}") (class "Default")
      (node (ref "IC23") (pin "8") (pinfunction "I0_8") (pintype "input"))
      (node (ref "IC62") (pin "6") (pinfunction "~{Q}_6") (pintype "output"))
    )
    (net (code "512") (name "~{DTB_07}") (class "Default")
      (node (ref "IC23") (pin "11") (pinfunction "I0_11") (pintype "input"))
      (node (ref "IC64") (pin "8") (pinfunction "~{Q}_8") (pintype "output"))
    )
    (net (code "513") (name "~{DTB_08}") (class "Default")
      (node (ref "IC24") (pin "2") (pinfunction "I0_2") (pintype "input"))
      (node (ref "IC63") (pin "6") (pinfunction "~{Q}_6") (pintype "output"))
    )
    (net (code "514") (name "~{DTB_09}") (class "Default")
      (node (ref "IC24") (pin "5") (pinfunction "I0_5") (pintype "input"))
      (node (ref "IC63") (pin "8") (pinfunction "~{Q}_8") (pintype "output"))
    )
    (net (code "515") (name "~{DTB_10}") (class "Default")
      (node (ref "IC24") (pin "8") (pinfunction "I0_8") (pintype "input"))
      (node (ref "IC64") (pin "6") (pinfunction "~{Q}_6") (pintype "output"))
    )
    (net (code "516") (name "~{DTB_11}") (class "Default")
      (node (ref "IC24") (pin "11") (pinfunction "I0_11") (pintype "input"))
      (node (ref "IC62") (pin "8") (pinfunction "~{Q}_8") (pintype "output"))
    )
    (net (code "517") (name "~{DTF}") (class "Default")
      (node (ref "IC139") (pin "5") (pinfunction "Q_5") (pintype "output"))
      (node (ref "IC40") (pin "11") (pinfunction "I0_11") (pintype "input"))
      (node (ref "IC70") (pin "4") (pinfunction "I2_4") (pintype "input"))
    )
    (net (code "518") (name "~{DTSF}") (class "Default")
      (node (ref "IC88") (pin "5") (pinfunction "I_5") (pintype "input"))
      (node (ref "IC89") (pin "8") (pinfunction "O_8") (pintype "output"))
    )
    (net (code "519") (name "~{EA_00_B05}") (class "Default")
      (node (ref "IC47") (pin "1") (pinfunction "O_1") (pintype "output"))
      (node (ref "IC51") (pin "1") (pinfunction "I0_1") (pintype "input"))
      (node (ref "IC51") (pin "2") (pinfunction "I1_2") (pintype "input"))
    )
    (net (code "520") (name "~{EA_00}") (class "Default")
      (node (ref "IC51") (pin "3") (pinfunction "O_3") (pintype "open_collector"))
      (node (ref "SV12") (pin "TT") (pinfunction "38_TT") (pintype "bidirectional"))
      (node (ref "SV5") (pin "TT") (pinfunction "38_TT") (pintype "bidirectional"))
    )
    (net (code "521") (name "~{EA_01_B05}") (class "Default")
      (node (ref "IC47") (pin "4") (pinfunction "O_4") (pintype "output"))
      (node (ref "IC51") (pin "6") (pinfunction "I0_6") (pintype "input"))
      (node (ref "IC51") (pin "7") (pinfunction "I1_7") (pintype "input"))
    )
    (net (code "522") (name "~{EA_01}") (class "Default")
      (node (ref "IC51") (pin "5") (pinfunction "O_5") (pintype "open_collector"))
      (node (ref "SV12") (pin "NN") (pinfunction "34_NN") (pintype "bidirectional"))
      (node (ref "SV5") (pin "NN") (pinfunction "34_NN") (pintype "bidirectional"))
    )
    (net (code "523") (name "~{EA_02_B05}") (class "Default")
      (node (ref "IC47") (pin "10") (pinfunction "O_10") (pintype "output"))
      (node (ref "IC52") (pin "1") (pinfunction "I0_1") (pintype "input"))
      (node (ref "IC52") (pin "2") (pinfunction "I1_2") (pintype "input"))
    )
    (net (code "524") (name "~{EA_02}") (class "Default")
      (node (ref "IC52") (pin "3") (pinfunction "O_3") (pintype "open_collector"))
      (node (ref "SV12") (pin "JJ") (pinfunction "30_JJ") (pintype "bidirectional"))
      (node (ref "SV5") (pin "JJ") (pinfunction "30_JJ") (pintype "bidirectional"))
    )
    (net (code "525") (name "~{EF}") (class "Default")
      (node (ref "IC14") (pin "6") (pinfunction "O_6") (pintype "output"))
      (node (ref "IC33") (pin "8") (pinfunction "I0_8") (pintype "input"))
    )
    (net (code "526") (name "~{END}") (class "Default")
      (node (ref "IC10") (pin "4") (pinfunction "I2_4") (pintype "input"))
      (node (ref "IC39") (pin "2") (pinfunction "I0_2") (pintype "input"))
      (node (ref "IC5") (pin "6") (pinfunction "~{Q}_6") (pintype "output"))
    )
    (net (code "527") (name "~{ENI}") (class "Default")
      (node (ref "IC33") (pin "5") (pinfunction "I0_5") (pintype "input"))
      (node (ref "IC96") (pin "13") (pinfunction "~{Q}_13") (pintype "output"))
    )
    (net (code "528") (name "~{FR_00}") (class "Default")
      (node (ref "IC108") (pin "9") (pinfunction "I0_9") (pintype "input"))
      (node (ref "IC109") (pin "1") (pinfunction "I0_1") (pintype "input"))
      (node (ref "IC32") (pin "5") (pinfunction "I0_5") (pintype "input"))
      (node (ref "IC58") (pin "13") (pinfunction "~{Q}_13") (pintype "output"))
    )
    (net (code "529") (name "~{FR_01}") (class "Default")
      (node (ref "IC17") (pin "9") (pinfunction "I0_9") (pintype "input"))
      (node (ref "IC32") (pin "8") (pinfunction "I0_8") (pintype "input"))
      (node (ref "IC47") (pin "11") (pinfunction "I0_11") (pintype "input"))
      (node (ref "IC58") (pin "8") (pinfunction "~{Q}_8") (pintype "output"))
    )
    (net (code "530") (name "~{FR_02}") (class "Default")
      (node (ref "IC32") (pin "11") (pinfunction "I0_11") (pintype "input"))
      (node (ref "IC95") (pin "13") (pinfunction "~{Q}_13") (pintype "output"))
    )
    (net (code "531") (name "~{FR_03}") (class "Default")
      (node (ref "IC33") (pin "2") (pinfunction "I0_2") (pintype "input"))
      (node (ref "IC60") (pin "2") (pinfunction "I1_2") (pintype "input"))
      (node (ref "IC95") (pin "8") (pinfunction "~{Q}_8") (pintype "output"))
    )
    (net (code "532") (name "~{IM_00_B03}") (class "Default")
      (node (ref "IC31") (pin "1") (pinfunction "O_1") (pintype "output"))
      (node (ref "IC34") (pin "1") (pinfunction "I0_1") (pintype "input"))
      (node (ref "IC34") (pin "2") (pinfunction "I1_2") (pintype "input"))
    )
    (net (code "533") (name "~{IM_00_B04}") (class "Default")
      (node (ref "IC33") (pin "10") (pinfunction "O_10") (pintype "output"))
      (node (ref "IC41") (pin "1") (pinfunction "I0_1") (pintype "input"))
      (node (ref "IC41") (pin "2") (pinfunction "I1_2") (pintype "input"))
    )
    (net (code "534") (name "~{IM_00}") (class "Default")
      (node (ref "IC34") (pin "3") (pinfunction "O_3") (pintype "open_collector"))
      (node (ref "IC41") (pin "3") (pinfunction "O_3") (pintype "open_collector"))
      (node (ref "SV10") (pin "D") (pinfunction "4_D") (pintype "bidirectional"))
      (node (ref "SV3") (pin "D") (pinfunction "4_D") (pintype "bidirectional"))
    )
    (net (code "535") (name "~{IM_01_B03}") (class "Default")
      (node (ref "IC31") (pin "4") (pinfunction "O_4") (pintype "output"))
      (node (ref "IC34") (pin "6") (pinfunction "I0_6") (pintype "input"))
      (node (ref "IC34") (pin "7") (pinfunction "I1_7") (pintype "input"))
    )
    (net (code "536") (name "~{IM_01_B04}") (class "Default")
      (node (ref "IC33") (pin "13") (pinfunction "O_13") (pintype "output"))
      (node (ref "IC41") (pin "6") (pinfunction "I0_6") (pintype "input"))
      (node (ref "IC41") (pin "7") (pinfunction "I1_7") (pintype "input"))
    )
    (net (code "537") (name "~{IM_01}") (class "Default")
      (node (ref "IC34") (pin "5") (pinfunction "O_5") (pintype "open_collector"))
      (node (ref "IC41") (pin "5") (pinfunction "O_5") (pintype "open_collector"))
      (node (ref "SV10") (pin "J") (pinfunction "8_J") (pintype "bidirectional"))
      (node (ref "SV3") (pin "J") (pinfunction "8_J") (pintype "bidirectional"))
    )
    (net (code "538") (name "~{IM_02_B03}") (class "Default")
      (node (ref "IC31") (pin "10") (pinfunction "O_10") (pintype "output"))
      (node (ref "IC35") (pin "1") (pinfunction "I0_1") (pintype "input"))
      (node (ref "IC35") (pin "2") (pinfunction "I1_2") (pintype "input"))
    )
    (net (code "539") (name "~{IM_02_B04}") (class "Default")
      (node (ref "IC39") (pin "1") (pinfunction "O_1") (pintype "output"))
      (node (ref "IC42") (pin "1") (pinfunction "I0_1") (pintype "input"))
      (node (ref "IC42") (pin "2") (pinfunction "I1_2") (pintype "input"))
    )
    (net (code "540") (name "~{IM_02}") (class "Default")
      (node (ref "IC35") (pin "3") (pinfunction "O_3") (pintype "open_collector"))
      (node (ref "IC42") (pin "3") (pinfunction "O_3") (pintype "open_collector"))
      (node (ref "SV10") (pin "N") (pinfunction "12_N") (pintype "bidirectional"))
      (node (ref "SV3") (pin "N") (pinfunction "12_N") (pintype "bidirectional"))
    )
    (net (code "541") (name "~{IM_03_B03}") (class "Default")
      (node (ref "IC31") (pin "13") (pinfunction "O_13") (pintype "output"))
      (node (ref "IC35") (pin "6") (pinfunction "I0_6") (pintype "input"))
      (node (ref "IC35") (pin "7") (pinfunction "I1_7") (pintype "input"))
    )
    (net (code "542") (name "~{IM_03_B04}") (class "Default")
      (node (ref "IC39") (pin "4") (pinfunction "O_4") (pintype "output"))
      (node (ref "IC42") (pin "6") (pinfunction "I0_6") (pintype "input"))
      (node (ref "IC42") (pin "7") (pinfunction "I1_7") (pintype "input"))
    )
    (net (code "543") (name "~{IM_03}") (class "Default")
      (node (ref "IC35") (pin "5") (pinfunction "O_5") (pintype "open_collector"))
      (node (ref "IC42") (pin "5") (pinfunction "O_5") (pintype "open_collector"))
      (node (ref "SV10") (pin "T") (pinfunction "16_T") (pintype "bidirectional"))
      (node (ref "SV3") (pin "T") (pinfunction "16_T") (pintype "bidirectional"))
    )
    (net (code "544") (name "~{IM_04_B03}") (class "Default")
      (node (ref "IC32") (pin "1") (pinfunction "O_1") (pintype "output"))
      (node (ref "IC36") (pin "1") (pinfunction "I0_1") (pintype "input"))
      (node (ref "IC36") (pin "2") (pinfunction "I1_2") (pintype "input"))
    )
    (net (code "545") (name "~{IM_04_B04}") (class "Default")
      (node (ref "IC39") (pin "10") (pinfunction "O_10") (pintype "output"))
      (node (ref "IC43") (pin "1") (pinfunction "I0_1") (pintype "input"))
      (node (ref "IC43") (pin "2") (pinfunction "I1_2") (pintype "input"))
    )
    (net (code "546") (name "~{IM_04}") (class "Default")
      (node (ref "IC36") (pin "3") (pinfunction "O_3") (pintype "open_collector"))
      (node (ref "IC43") (pin "3") (pinfunction "O_3") (pintype "open_collector"))
      (node (ref "SV10") (pin "X") (pinfunction "20_X") (pintype "bidirectional"))
      (node (ref "SV3") (pin "X") (pinfunction "20_X") (pintype "bidirectional"))
    )
    (net (code "547") (name "~{IM_05_B03}") (class "Default")
      (node (ref "IC32") (pin "4") (pinfunction "O_4") (pintype "output"))
      (node (ref "IC36") (pin "6") (pinfunction "I0_6") (pintype "input"))
      (node (ref "IC36") (pin "7") (pinfunction "I1_7") (pintype "input"))
    )
    (net (code "548") (name "~{IM_05_B04}") (class "Default")
      (node (ref "IC39") (pin "13") (pinfunction "O_13") (pintype "output"))
      (node (ref "IC43") (pin "6") (pinfunction "I0_6") (pintype "input"))
      (node (ref "IC43") (pin "7") (pinfunction "I1_7") (pintype "input"))
    )
    (net (code "549") (name "~{IM_05}") (class "Default")
      (node (ref "IC36") (pin "5") (pinfunction "O_5") (pintype "open_collector"))
      (node (ref "IC43") (pin "5") (pinfunction "O_5") (pintype "open_collector"))
      (node (ref "SV10") (pin "BB") (pinfunction "24_BB") (pintype "bidirectional"))
      (node (ref "SV3") (pin "BB") (pinfunction "24_BB") (pintype "bidirectional"))
    )
    (net (code "550") (name "~{IM_06_B03}") (class "Default")
      (node (ref "IC32") (pin "10") (pinfunction "O_10") (pintype "output"))
      (node (ref "IC37") (pin "1") (pinfunction "I0_1") (pintype "input"))
      (node (ref "IC37") (pin "2") (pinfunction "I1_2") (pintype "input"))
    )
    (net (code "551") (name "~{IM_06_B04}") (class "Default")
      (node (ref "IC40") (pin "1") (pinfunction "O_1") (pintype "output"))
      (node (ref "IC44") (pin "1") (pinfunction "I0_1") (pintype "input"))
      (node (ref "IC44") (pin "2") (pinfunction "I1_2") (pintype "input"))
    )
    (net (code "552") (name "~{IM_06}") (class "Default")
      (node (ref "IC37") (pin "3") (pinfunction "O_3") (pintype "open_collector"))
      (node (ref "IC44") (pin "3") (pinfunction "O_3") (pintype "open_collector"))
      (node (ref "SV10") (pin "FF") (pinfunction "28_FF") (pintype "bidirectional"))
      (node (ref "SV3") (pin "FF") (pinfunction "28_FF") (pintype "bidirectional"))
    )
    (net (code "553") (name "~{IM_07_B03}") (class "Default")
      (node (ref "IC32") (pin "13") (pinfunction "O_13") (pintype "output"))
      (node (ref "IC37") (pin "6") (pinfunction "I0_6") (pintype "input"))
      (node (ref "IC37") (pin "7") (pinfunction "I1_7") (pintype "input"))
    )
    (net (code "554") (name "~{IM_07_B04}") (class "Default")
      (node (ref "IC40") (pin "4") (pinfunction "O_4") (pintype "output"))
      (node (ref "IC44") (pin "6") (pinfunction "I0_6") (pintype "input"))
      (node (ref "IC44") (pin "7") (pinfunction "I1_7") (pintype "input"))
    )
    (net (code "555") (name "~{IM_07}") (class "Default")
      (node (ref "IC37") (pin "5") (pinfunction "O_5") (pintype "open_collector"))
      (node (ref "IC44") (pin "5") (pinfunction "O_5") (pintype "open_collector"))
      (node (ref "SV10") (pin "LL") (pinfunction "32_LL") (pintype "bidirectional"))
      (node (ref "SV3") (pin "LL") (pinfunction "32_LL") (pintype "bidirectional"))
    )
    (net (code "556") (name "~{IM_08_B03}") (class "Default")
      (node (ref "IC33") (pin "1") (pinfunction "O_1") (pintype "output"))
      (node (ref "IC38") (pin "1") (pinfunction "I0_1") (pintype "input"))
      (node (ref "IC38") (pin "2") (pinfunction "I1_2") (pintype "input"))
    )
    (net (code "557") (name "~{IM_08_B04}") (class "Default")
      (node (ref "IC40") (pin "10") (pinfunction "O_10") (pintype "output"))
      (node (ref "IC45") (pin "1") (pinfunction "I0_1") (pintype "input"))
      (node (ref "IC45") (pin "2") (pinfunction "I1_2") (pintype "input"))
    )
    (net (code "558") (name "~{IM_08}") (class "Default")
      (node (ref "IC38") (pin "3") (pinfunction "O_3") (pintype "open_collector"))
      (node (ref "IC45") (pin "3") (pinfunction "O_3") (pintype "open_collector"))
      (node (ref "SV10") (pin "RR") (pinfunction "36_RR") (pintype "bidirectional"))
      (node (ref "SV3") (pin "RR") (pinfunction "36_RR") (pintype "bidirectional"))
    )
    (net (code "559") (name "~{IM_09_B03}") (class "Default")
      (node (ref "IC33") (pin "4") (pinfunction "O_4") (pintype "output"))
      (node (ref "IC38") (pin "6") (pinfunction "I0_6") (pintype "input"))
      (node (ref "IC38") (pin "7") (pinfunction "I1_7") (pintype "input"))
    )
    (net (code "560") (name "~{IM_09}") (class "Default")
      (node (ref "IC38") (pin "5") (pinfunction "O_5") (pintype "open_collector"))
      (node (ref "SV10") (pin "F") (pinfunction "6_F") (pintype "bidirectional"))
      (node (ref "SV3") (pin "F") (pinfunction "6_F") (pintype "bidirectional"))
    )
    (net (code "561") (name "~{IM_10}") (class "Default")
      (node (ref "SV10") (pin "L") (pinfunction "10_L") (pintype "bidirectional"))
      (node (ref "SV3") (pin "L") (pinfunction "10_L") (pintype "bidirectional"))
    )
    (net (code "562") (name "~{IM_11_B04}") (class "Default")
      (node (ref "IC40") (pin "13") (pinfunction "O_13") (pintype "output"))
      (node (ref "IC45") (pin "6") (pinfunction "I0_6") (pintype "input"))
      (node (ref "IC45") (pin "7") (pinfunction "I1_7") (pintype "input"))
    )
    (net (code "563") (name "~{IM_11}") (class "Default")
      (node (ref "IC45") (pin "5") (pinfunction "O_5") (pintype "open_collector"))
      (node (ref "SV10") (pin "R") (pinfunction "14_R") (pintype "bidirectional"))
      (node (ref "SV3") (pin "R") (pinfunction "14_R") (pintype "bidirectional"))
    )
    (net (code "564") (name "~{INT_RQ}") (class "Default")
      (node (ref "IC17") (pin "6") (pinfunction "O_6") (pintype "output"))
      (node (ref "IC46") (pin "5") (pinfunction "I0_5") (pintype "input"))
    )
    (net (code "565") (name "~{LDMF}") (class "Default")
      (node (ref "IC61") (pin "1") (pinfunction "I0_1") (pintype "input"))
      (node (ref "IC88") (pin "11") (pinfunction "I_11") (pintype "input"))
      (node (ref "IC91") (pin "3") (pinfunction "O_3") (pintype "output"))
    )
    (net (code "566") (name "~{LPB_00}") (class "Default")
      (node (ref "IC127") (pin "13") (pinfunction "~{Q}_13") (pintype "output"))
      (node (ref "IC135") (pin "1") (pinfunction "I0_1") (pintype "input"))
    )
    (net (code "567") (name "~{LPB_01}") (class "Default")
      (node (ref "IC128") (pin "13") (pinfunction "~{Q}_13") (pintype "output"))
      (node (ref "IC135") (pin "2") (pinfunction "I1_2") (pintype "input"))
    )
    (net (code "568") (name "~{LPB_02}") (class "Default")
      (node (ref "IC129") (pin "13") (pinfunction "~{Q}_13") (pintype "output"))
      (node (ref "IC135") (pin "3") (pinfunction "I2_3") (pintype "input"))
    )
    (net (code "569") (name "~{LPB_03}") (class "Default")
      (node (ref "IC127") (pin "8") (pinfunction "~{Q}_8") (pintype "output"))
      (node (ref "IC135") (pin "4") (pinfunction "I3_4") (pintype "input"))
    )
    (net (code "570") (name "~{LPB_04}") (class "Default")
      (node (ref "IC128") (pin "8") (pinfunction "~{Q}_8") (pintype "output"))
      (node (ref "IC135") (pin "5") (pinfunction "I4_5") (pintype "input"))
    )
    (net (code "571") (name "~{LPB_05}") (class "Default")
      (node (ref "IC129") (pin "8") (pinfunction "~{Q}_8") (pintype "output"))
      (node (ref "IC135") (pin "11") (pinfunction "I6_11") (pintype "input"))
      (node (ref "IC135") (pin "12") (pinfunction "I7_12") (pintype "input"))
      (node (ref "IC135") (pin "6") (pinfunction "I5_6") (pintype "input"))
    )
    (net (code "572") (name "~{M-STOP}") (class "Default")
      (node (ref "IC15") (pin "6") (pinfunction "O_6") (pintype "output"))
      (node (ref "IC76") (pin "4") (pinfunction "PRE_4") (pintype "input"))
      (node (ref "IC96") (pin "6") (pinfunction "CL_6") (pintype "input"))
      (node (ref "M916_20") (pin "L1") (pinfunction "P$2_L1") (pintype "bidirectional"))
    )
    (net (code "573") (name "~{MB_TO_DTB}") (class "Default")
      (node (ref "IC140") (pin "10") (pinfunction "I1_10") (pintype "input"))
      (node (ref "IC140") (pin "12") (pinfunction "I2_12") (pintype "input"))
      (node (ref "IC140") (pin "13") (pinfunction "I3_13") (pintype "input"))
      (node (ref "IC140") (pin "9") (pinfunction "I0_9") (pintype "input"))
      (node (ref "IC141") (pin "6") (pinfunction "O_6") (pintype "output"))
    )
    (net (code "574") (name "~{MC00}") (class "Default")
      (node (ref "IC12") (pin "13") (pinfunction "I1_13") (pintype "input"))
      (node (ref "IC69") (pin "9") (pinfunction "I0_9") (pintype "input"))
      (node (ref "IC73") (pin "6") (pinfunction "~{Q}_6") (pintype "output"))
    )
    (net (code "575") (name "~{MC01}") (class "Default")
      (node (ref "IC133") (pin "6") (pinfunction "I5_6") (pintype "input"))
      (node (ref "IC68") (pin "3") (pinfunction "I0_3") (pintype "input"))
      (node (ref "IC73") (pin "8") (pinfunction "~{Q}_8") (pintype "output"))
      (node (ref "IC91") (pin "10") (pinfunction "I1_10") (pintype "input"))
    )
    (net (code "576") (name "~{MC02}") (class "Default")
      (node (ref "IC133") (pin "11") (pinfunction "I6_11") (pintype "input"))
      (node (ref "IC73") (pin "2") (pinfunction "D_2") (pintype "input"))
      (node (ref "IC74") (pin "6") (pinfunction "~{Q}_6") (pintype "output"))
    )
    (net (code "577") (name "~{MF00}") (class "Default")
      (node (ref "IC116") (pin "8") (pinfunction "~{Q}_8") (pintype "output"))
      (node (ref "IC40") (pin "2") (pinfunction "I0_2") (pintype "input"))
      (node (ref "IC47") (pin "2") (pinfunction "I0_2") (pintype "input"))
    )
    (net (code "578") (name "~{MF01}") (class "Default")
      (node (ref "IC137") (pin "6") (pinfunction "~{Q}_6") (pintype "output"))
      (node (ref "IC40") (pin "5") (pinfunction "I0_5") (pintype "input"))
      (node (ref "IC47") (pin "5") (pinfunction "I0_5") (pintype "input"))
    )
    (net (code "579") (name "~{MF02}") (class "Default")
      (node (ref "IC137") (pin "8") (pinfunction "~{Q}_8") (pintype "output"))
      (node (ref "IC40") (pin "8") (pinfunction "I0_8") (pintype "input"))
      (node (ref "IC47") (pin "8") (pinfunction "I0_8") (pintype "input"))
    )
    (net (code "580") (name "~{MKTK}") (class "Default")
      (node (ref "IC10") (pin "1") (pinfunction "I0_1") (pintype "input"))
      (node (ref "IC33") (pin "11") (pinfunction "I0_11") (pintype "input"))
      (node (ref "IC6") (pin "9") (pinfunction "Q_9") (pintype "output"))
    )
    (net (code "581") (name "~{MKT}") (class "Default")
      (node (ref "IC116") (pin "3") (pinfunction "CLK_3") (pintype "input"))
      (node (ref "IC133") (pin "12") (pinfunction "I7_12") (pintype "input"))
      (node (ref "IC66") (pin "5") (pinfunction "I3_5") (pintype "input"))
      (node (ref "IC75") (pin "12") (pinfunction "D_12") (pintype "input"))
      (node (ref "IC75") (pin "8") (pinfunction "~{Q}_8") (pintype "output"))
    )
    (net (code "582") (name "~{MK_BLK_END}") (class "Default")
      (node (ref "IC8") (pin "4") (pinfunction "I2_4") (pintype "input"))
      (node (ref "M916_17") (pin "V1") (pinfunction "P$2_V1") (pintype "bidirectional"))
    )
    (net (code "583") (name "~{MK_BLK_MK}") (class "Default")
      (node (ref "M916_18") (pin "D2") (pinfunction "P$2_D2") (pintype "bidirectional"))
    )
    (net (code "584") (name "~{MK_BLK_START}") (class "Default")
      (node (ref "IC8") (pin "1") (pinfunction "I0_1") (pintype "input"))
      (node (ref "M916_18") (pin "F1") (pinfunction "P$2_F1") (pintype "bidirectional"))
    )
    (net (code "585") (name "~{MK_BLK_SYNC}") (class "Default")
      (node (ref "M916_17") (pin "T2") (pinfunction "P$2_T2") (pintype "bidirectional"))
    )
    (net (code "586") (name "~{MK_DATA_SYNC}") (class "Default")
      (node (ref "M916_18") (pin "J1") (pinfunction "P$2_J1") (pintype "bidirectional"))
    )
    (net (code "587") (name "~{MK_DATA}") (class "Default")
      (node (ref "IC8") (pin "2") (pinfunction "I1_2") (pintype "input"))
      (node (ref "M916_18") (pin "U2") (pinfunction "P$2_U2") (pintype "bidirectional"))
    )
    (net (code "588") (name "~{MK_END}") (class "Default")
      (node (ref "IC8") (pin "5") (pinfunction "I3_5") (pintype "input"))
      (node (ref "M916_18") (pin "H2") (pinfunction "P$2_H2") (pintype "bidirectional"))
    )
    (net (code "589") (name "~{MOVE}") (class "Default")
      (node (ref "IC124") (pin "9") (pinfunction "I_9") (pintype "input"))
      (node (ref "IC125") (pin "1") (pinfunction "0_1") (pintype "output"))
      (node (ref "IC9") (pin "12") (pinfunction "I2_12") (pintype "input"))
    )
    (net (code "590") (name "~{MR00}") (class "Default")
      (node (ref "IC31") (pin "11") (pinfunction "I0_11") (pintype "input"))
      (node (ref "IC57") (pin "8") (pinfunction "~{Q}_8") (pintype "output"))
    )
    (net (code "591") (name "~{MR01}") (class "Default")
      (node (ref "IC32") (pin "2") (pinfunction "I0_2") (pintype "input"))
      (node (ref "IC76") (pin "2") (pinfunction "D_2") (pintype "input"))
      (node (ref "IC96") (pin "8") (pinfunction "~{Q}_8") (pintype "output"))
    )
    (net (code "592") (name "~{PAR}") (class "Default")
      (node (ref "IC13") (pin "13") (pinfunction "I1_13") (pintype "input"))
      (node (ref "IC39") (pin "8") (pinfunction "I0_8") (pintype "input"))
      (node (ref "IC7") (pin "5") (pinfunction "Q_5") (pintype "output"))
    )
    (net (code "593") (name "~{PC+ES}") (class "Default")
      (node (ref "IC14") (pin "8") (pinfunction "O_8") (pintype "output"))
      (node (ref "IC69") (pin "5") (pinfunction "I2_5") (pintype "input"))
    )
    (net (code "594") (name "~{PWR_CLR}") (class "Default")
      (node (ref "IC107") (pin "13") (pinfunction "I1_13") (pintype "input"))
      (node (ref "IC116") (pin "13") (pinfunction "CLR_13") (pintype "input"))
      (node (ref "IC116") (pin "4") (pinfunction "PRE_4") (pintype "input"))
      (node (ref "IC12") (pin "1") (pinfunction "I0_1") (pintype "input"))
      (node (ref "IC12") (pin "10") (pinfunction "I1_10") (pintype "input"))
      (node (ref "IC13") (pin "9") (pinfunction "I0_9") (pintype "input"))
      (node (ref "IC137") (pin "1") (pinfunction "CLR_1") (pintype "input"))
      (node (ref "IC137") (pin "13") (pinfunction "CLR_13") (pintype "input"))
      (node (ref "IC61") (pin "5") (pinfunction "I1_5") (pintype "input"))
      (node (ref "IC91") (pin "6") (pinfunction "O_6") (pintype "output"))
      (node (ref "IC93") (pin "13") (pinfunction "I_13") (pintype "input"))
      (node (ref "M916_7") (pin "M1") (pinfunction "P$2_M1") (pintype "bidirectional"))
    )
    (net (code "595") (name "~{RDD_00}") (class "Default")
      (node (ref "M916_5") (pin "V2") (pinfunction "P$2_V2") (pintype "bidirectional"))
    )
    (net (code "596") (name "~{RDD_01}") (class "Default")
      (node (ref "M916_13") (pin "V2") (pinfunction "P$2_V2") (pintype "bidirectional"))
    )
    (net (code "597") (name "~{RDD_02}") (class "Default")
      (node (ref "M916_4") (pin "V2") (pinfunction "P$2_V2") (pintype "bidirectional"))
    )
    (net (code "598") (name "~{RDMK}") (class "Default")
      (node (ref "M916_12") (pin "V2") (pinfunction "P$2_V2") (pintype "bidirectional"))
    )
    (net (code "599") (name "~{READ_ALL}") (class "Default")
      (node (ref "IC106") (pin "13") (pinfunction "I1_13") (pintype "input"))
      (node (ref "IC125") (pin "4") (pinfunction "3_4") (pintype "output"))
      (node (ref "IC126") (pin "1") (pinfunction "I_1") (pintype "input"))
    )
    (net (code "600") (name "~{READ_DATA}") (class "Default")
      (node (ref "IC124") (pin "13") (pinfunction "I_13") (pintype "input"))
      (node (ref "IC125") (pin "3") (pinfunction "2_3") (pintype "output"))
      (node (ref "IC60") (pin "9") (pinfunction "I0_9") (pintype "input"))
      (node (ref "IC69") (pin "1") (pinfunction "I0_1") (pintype "input"))
    )
    (net (code "601") (name "~{RSTA}") (class "Default")
      (node (ref "IC31") (pin "12") (pinfunction "I1_12") (pintype "input"))
      (node (ref "IC31") (pin "3") (pinfunction "I1_3") (pintype "input"))
      (node (ref "IC31") (pin "6") (pinfunction "I1_6") (pintype "input"))
      (node (ref "IC31") (pin "9") (pinfunction "I1_9") (pintype "input"))
      (node (ref "IC32") (pin "12") (pinfunction "I1_12") (pintype "input"))
      (node (ref "IC32") (pin "3") (pinfunction "I1_3") (pintype "input"))
      (node (ref "IC32") (pin "6") (pinfunction "I1_6") (pintype "input"))
      (node (ref "IC32") (pin "9") (pinfunction "I1_9") (pintype "input"))
      (node (ref "IC33") (pin "3") (pinfunction "I1_3") (pintype "input"))
      (node (ref "IC33") (pin "6") (pinfunction "I1_6") (pintype "input"))
      (node (ref "IC55") (pin "13") (pinfunction "I_13") (pintype "input"))
      (node (ref "IC87") (pin "6") (pinfunction "O_6") (pintype "output"))
    )
    (net (code "602") (name "~{RSTB}") (class "Default")
      (node (ref "IC33") (pin "12") (pinfunction "I1_12") (pintype "input"))
      (node (ref "IC33") (pin "9") (pinfunction "I1_9") (pintype "input"))
      (node (ref "IC39") (pin "12") (pinfunction "I1_12") (pintype "input"))
      (node (ref "IC39") (pin "3") (pinfunction "I1_3") (pintype "input"))
      (node (ref "IC39") (pin "6") (pinfunction "I1_6") (pintype "input"))
      (node (ref "IC39") (pin "9") (pinfunction "I1_9") (pintype "input"))
      (node (ref "IC40") (pin "12") (pinfunction "I1_12") (pintype "input"))
      (node (ref "IC40") (pin "3") (pinfunction "I1_3") (pintype "input"))
      (node (ref "IC40") (pin "6") (pinfunction "I1_6") (pintype "input"))
      (node (ref "IC40") (pin "9") (pinfunction "I1_9") (pintype "input"))
      (node (ref "IC88") (pin "9") (pinfunction "I_9") (pintype "input"))
      (node (ref "IC89") (pin "11") (pinfunction "O_11") (pintype "output"))
    )
    (net (code "603") (name "~{SEARCH}") (class "Default")
      (node (ref "IC124") (pin "11") (pinfunction "I_11") (pintype "input"))
      (node (ref "IC125") (pin "2") (pinfunction "1_2") (pintype "output"))
      (node (ref "IC48") (pin "2") (pinfunction "I0_2") (pintype "input"))
      (node (ref "IC69") (pin "2") (pinfunction "I1_2") (pintype "input"))
    )
    (net (code "604") (name "~{SEL}") (class "Default")
      (node (ref "IC10") (pin "5") (pinfunction "I3_5") (pintype "input"))
      (node (ref "IC39") (pin "5") (pinfunction "I0_5") (pintype "input"))
      (node (ref "IC5") (pin "8") (pinfunction "~{Q}_8") (pintype "output"))
    )
    (net (code "605") (name "~{SE}") (class "Default")
      (node (ref "IC125") (pin "8") (pinfunction "7_8") (pintype "output"))
      (node (ref "IC126") (pin "11") (pinfunction "I_11") (pintype "input"))
      (node (ref "IC8") (pin "10") (pinfunction "I1_10") (pintype "input"))
    )
    (net (code "606") (name "~{SH_EN}") (class "Default")
      (node (ref "IC103") (pin "4") (pinfunction "2C_4") (pintype "input"))
      (node (ref "IC104") (pin "4") (pinfunction "2C_4") (pintype "input"))
      (node (ref "IC105") (pin "9") (pinfunction "1D_9") (pintype "input"))
      (node (ref "IC15") (pin "3") (pinfunction "I_3") (pintype "input"))
      (node (ref "IC18") (pin "11") (pinfunction "O_11") (pintype "output"))
    )
    (net (code "607") (name "~{SKP_RQ}") (class "Default")
      (node (ref "IC18") (pin "6") (pinfunction "O_6") (pintype "output"))
      (node (ref "IC46") (pin "8") (pinfunction "I0_8") (pintype "input"))
    )
    (net (code "608") (name "~{SP_DY}") (class "Default")
      (node (ref "IC115") (pin "12") (pinfunction "D_12") (pintype "input"))
      (node (ref "M916_20") (pin "F2") (pinfunction "P$2_F2") (pintype "bidirectional"))
    )
    (net (code "609") (name "~{ST_BLK_MK}") (class "Default")
      (node (ref "IC111") (pin "6") (pinfunction "O_6") (pintype "output"))
      (node (ref "IC9") (pin "1") (pinfunction "I0_1") (pintype "input"))
      (node (ref "IC9") (pin "9") (pinfunction "I0_9") (pintype "input"))
    )
    (net (code "610") (name "~{ST_CK_0P}") (class "Default")
      (node (ref "IC94") (pin "11") (pinfunction "I_11") (pintype "input"))
      (node (ref "M916_23") (pin "L2") (pinfunction "P$2_L2") (pintype "bidirectional"))
    )
    (net (code "611") (name "~{ST_CK}") (class "Default")
      (node (ref "IC111") (pin "8") (pinfunction "O_8") (pintype "output"))
      (node (ref "IC121") (pin "2") (pinfunction "I1_2") (pintype "input"))
    )
    (net (code "612") (name "~{ST_DATA}") (class "Default")
      (node (ref "IC111") (pin "10") (pinfunction "O_10") (pintype "output"))
    )
    (net (code "613") (name "~{ST_FINAL}") (class "Default")
      (node (ref "IC107") (pin "2") (pinfunction "I1_2") (pintype "input"))
      (node (ref "IC111") (pin "12") (pinfunction "O_12") (pintype "output"))
      (node (ref "IC121") (pin "4") (pinfunction "I2_4") (pintype "input"))
    )
    (net (code "614") (name "~{ST_IDLE}") (class "Default")
      (node (ref "IC112") (pin "2") (pinfunction "O_2") (pintype "output"))
      (node (ref "IC9") (pin "10") (pinfunction "I1_10") (pintype "input"))
      (node (ref "IC9") (pin "2") (pinfunction "I1_2") (pintype "input"))
    )
    (net (code "615") (name "~{ST_REV_CK}") (class "Default")
      (node (ref "IC111") (pin "2") (pinfunction "O_2") (pintype "output"))
    )
    (net (code "616") (name "~{SWTM}") (class "Default")
      (node (ref "IC104") (pin "12") (pinfunction "1B_12") (pintype "input"))
      (node (ref "IC55") (pin "2") (pinfunction "O_2") (pintype "output"))
    )
    (net (code "617") (name "~{SYNC-P}") (class "Default")
      (node (ref "IC66") (pin "8") (pinfunction "O_8") (pintype "output"))
      (node (ref "IC73") (pin "1") (pinfunction "CLR_1") (pintype "input"))
      (node (ref "IC73") (pin "13") (pinfunction "CLR_13") (pintype "input"))
      (node (ref "IC74") (pin "1") (pinfunction "CLR_1") (pintype "input"))
      (node (ref "IC74") (pin "13") (pinfunction "CLR_13") (pintype "input"))
      (node (ref "IC75") (pin "1") (pinfunction "CLR_1") (pintype "input"))
      (node (ref "IC75") (pin "13") (pinfunction "CLR_13") (pintype "input"))
    )
    (net (code "618") (name "~{SYNC}") (class "Default")
      (node (ref "M916_17") (pin "M2") (pinfunction "P$2_M2") (pintype "bidirectional"))
    )
    (net (code "619") (name "~{TIM}") (class "Default")
      (node (ref "IC10") (pin "2") (pinfunction "I1_2") (pintype "input"))
      (node (ref "IC39") (pin "11") (pinfunction "I0_11") (pintype "input"))
      (node (ref "IC6") (pin "6") (pinfunction "~{Q}_6") (pintype "output"))
    )
    (net (code "620") (name "~{TM_EN}") (class "Default")
      (node (ref "IC108") (pin "13") (pinfunction "I2_13") (pintype "input"))
      (node (ref "IC109") (pin "10") (pinfunction "I1_10") (pintype "input"))
      (node (ref "IC112") (pin "4") (pinfunction "O_4") (pintype "output"))
      (node (ref "IC61") (pin "12") (pinfunction "I0_12") (pintype "input"))
      (node (ref "IC61") (pin "9") (pinfunction "I0_9") (pintype "input"))
      (node (ref "M916_21") (pin "J2") (pinfunction "P$2_J2") (pintype "bidirectional"))
      (node (ref "M916_21") (pin "K2") (pinfunction "P$2_K2") (pintype "bidirectional"))
    )
    (net (code "621") (name "~{TP00_A}") (class "Default")
      (node (ref "IC20") (pin "1") (pinfunction "I0_1") (pintype "input"))
      (node (ref "IC20") (pin "2") (pinfunction "I1_2") (pintype "input"))
      (node (ref "IC20") (pin "4") (pinfunction "I2_4") (pintype "input"))
      (node (ref "IC20") (pin "5") (pinfunction "I3_5") (pintype "input"))
      (node (ref "M916_2") (pin "L2") (pinfunction "P$2_L2") (pintype "bidirectional"))
    )
    (net (code "622") (name "~{TP0_XTLK_DY}") (class "Default")
      (node (ref "IC15") (pin "8") (pinfunction "O_8") (pintype "output"))
      (node (ref "IC20") (pin "12") (pinfunction "I2_12") (pintype "input"))
      (node (ref "M916_2") (pin "J2") (pinfunction "P$2_J2") (pintype "bidirectional"))
      (node (ref "M916_2") (pin "K2") (pinfunction "P$2_K2") (pintype "bidirectional"))
    )
    (net (code "623") (name "~{TP00}") (class "Default")
      (node (ref "IC19") (pin "10") (pinfunction "I1_10") (pintype "input"))
      (node (ref "IC19") (pin "12") (pinfunction "I2_12") (pintype "input"))
      (node (ref "IC19") (pin "13") (pinfunction "I3_13") (pintype "input"))
      (node (ref "IC19") (pin "6") (pinfunction "O_6") (pintype "output"))
      (node (ref "IC19") (pin "9") (pinfunction "I0_9") (pintype "input"))
      (node (ref "IC75") (pin "3") (pinfunction "CLK_3") (pintype "input"))
      (node (ref "M916_18") (pin "N1") (pinfunction "P$2_N1") (pintype "bidirectional"))
    )
    (net (code "624") (name "~{TP01_A}") (class "Default")
      (node (ref "IC21") (pin "10") (pinfunction "I1_10") (pintype "input"))
      (node (ref "IC21") (pin "12") (pinfunction "I2_12") (pintype "input"))
      (node (ref "IC21") (pin "13") (pinfunction "I3_13") (pintype "input"))
      (node (ref "IC21") (pin "9") (pinfunction "I0_9") (pintype "input"))
      (node (ref "M916_11") (pin "L2") (pinfunction "P$2_L2") (pintype "bidirectional"))
    )
    (net (code "625") (name "~{TP1_XTLK_DY}") (class "Default")
      (node (ref "IC16") (pin "2") (pinfunction "O_2") (pintype "output"))
      (node (ref "IC19") (pin "2") (pinfunction "I1_2") (pintype "input"))
      (node (ref "M916_11") (pin "H2") (pinfunction "P$2_H2") (pintype "bidirectional"))
      (node (ref "M916_11") (pin "J2") (pinfunction "P$2_J2") (pintype "bidirectional"))
    )
    (net (code "626") (name "~{TP01}") (class "Default")
      (node (ref "IC20") (pin "8") (pinfunction "O_8") (pintype "output"))
      (node (ref "IC21") (pin "1") (pinfunction "I0_1") (pintype "input"))
      (node (ref "IC21") (pin "2") (pinfunction "I1_2") (pintype "input"))
      (node (ref "IC21") (pin "4") (pinfunction "I2_4") (pintype "input"))
      (node (ref "IC21") (pin "5") (pinfunction "I3_5") (pintype "input"))
      (node (ref "IC74") (pin "11") (pinfunction "CLK_11") (pintype "input"))
    )
    (net (code "627") (name "~{TS03}") (class "Default")
      (node (ref "IC89") (pin "3") (pinfunction "O_3") (pintype "output"))
      (node (ref "M916_23") (pin "H2") (pinfunction "P$2_H2") (pintype "bidirectional"))
      (node (ref "M916_23") (pin "J2") (pinfunction "P$2_J2") (pintype "bidirectional"))
      (node (ref "M916_23") (pin "K2") (pinfunction "P$2_K2") (pintype "bidirectional"))
    )
    (net (code "628") (name "~{T_00}") (class "Default")
      (node (ref "M916_15") (pin "V2") (pinfunction "P$2_V2") (pintype "bidirectional"))
      (node (ref "M916_16") (pin "V2") (pinfunction "P$2_V2") (pintype "bidirectional"))
      (node (ref "M916_8") (pin "V2") (pinfunction "P$2_V2") (pintype "bidirectional"))
    )
    (net (code "629") (name "~{T_01}") (class "Default")
      (node (ref "M916_16") (pin "M2") (pinfunction "P$2_M2") (pintype "bidirectional"))
      (node (ref "M916_7") (pin "S1") (pinfunction "P$2_S1") (pintype "bidirectional"))
      (node (ref "M916_8") (pin "M2") (pinfunction "P$2_M2") (pintype "bidirectional"))
    )
    (net (code "630") (name "~{T_02}") (class "Default")
      (node (ref "M916_16") (pin "N2") (pinfunction "P$2_N2") (pintype "bidirectional"))
      (node (ref "M916_7") (pin "H2") (pinfunction "P$2_H2") (pintype "bidirectional"))
      (node (ref "M916_8") (pin "N2") (pinfunction "P$2_N2") (pintype "bidirectional"))
    )
    (net (code "631") (name "~{T_03}") (class "Default")
      (node (ref "M916_16") (pin "P2") (pinfunction "P$2_P2") (pintype "bidirectional"))
      (node (ref "M916_7") (pin "J2") (pinfunction "P$2_J2") (pintype "bidirectional"))
      (node (ref "M916_8") (pin "P2") (pinfunction "P$2_P2") (pintype "bidirectional"))
    )
    (net (code "632") (name "~{T_04}") (class "Default")
      (node (ref "M916_16") (pin "R2") (pinfunction "P$2_R2") (pintype "bidirectional"))
      (node (ref "M916_7") (pin "N2") (pinfunction "P$2_N2") (pintype "bidirectional"))
      (node (ref "M916_8") (pin "R2") (pinfunction "P$2_R2") (pintype "bidirectional"))
    )
    (net (code "633") (name "~{T_05}") (class "Default")
      (node (ref "M916_16") (pin "S2") (pinfunction "P$2_S2") (pintype "bidirectional"))
      (node (ref "M916_7") (pin "P2") (pinfunction "P$2_P2") (pintype "bidirectional"))
      (node (ref "M916_8") (pin "S2") (pinfunction "P$2_S2") (pintype "bidirectional"))
    )
    (net (code "634") (name "~{T_06}") (class "Default")
      (node (ref "M916_16") (pin "T2") (pinfunction "P$2_T2") (pintype "bidirectional"))
      (node (ref "M916_7") (pin "U2") (pinfunction "P$2_U2") (pintype "bidirectional"))
      (node (ref "M916_8") (pin "T2") (pinfunction "P$2_T2") (pintype "bidirectional"))
    )
    (net (code "635") (name "~{T_07}") (class "Default")
      (node (ref "M916_16") (pin "U2") (pinfunction "P$2_U2") (pintype "bidirectional"))
      (node (ref "M916_7") (pin "V2") (pinfunction "P$2_V2") (pintype "bidirectional"))
      (node (ref "M916_8") (pin "U2") (pinfunction "P$2_U2") (pintype "bidirectional"))
    )
    (net (code "636") (name "~{T_FWD}") (class "Default")
      (node (ref "M916_16") (pin "H2") (pinfunction "P$2_H2") (pintype "bidirectional"))
      (node (ref "M916_7") (pin "K1") (pinfunction "P$2_K1") (pintype "bidirectional"))
      (node (ref "M916_8") (pin "E2") (pinfunction "P$2_E2") (pintype "bidirectional"))
    )
    (net (code "637") (name "~{T_GO}") (class "Default")
      (node (ref "M916_16") (pin "D2") (pinfunction "P$2_D2") (pintype "bidirectional"))
      (node (ref "M916_7") (pin "D1") (pinfunction "P$2_D1") (pintype "bidirectional"))
      (node (ref "M916_8") (pin "C2") (pinfunction "P$2_C2") (pintype "bidirectional"))
    )
    (net (code "638") (name "~{T_PWR_CLR}") (class "Default")
      (node (ref "M916_16") (pin "K2") (pinfunction "P$2_K2") (pintype "bidirectional"))
      (node (ref "M916_7") (pin "R1") (pinfunction "P$2_R1") (pintype "bidirectional"))
      (node (ref "M916_8") (pin "H2") (pinfunction "P$2_H2") (pintype "bidirectional"))
    )
    (net (code "639") (name "~{T_REV}") (class "Default")
      (node (ref "M916_16") (pin "J2") (pinfunction "P$2_J2") (pintype "bidirectional"))
      (node (ref "M916_7") (pin "L1") (pinfunction "P$2_L1") (pintype "bidirectional"))
      (node (ref "M916_8") (pin "F2") (pinfunction "P$2_F2") (pintype "bidirectional"))
    )
    (net (code "640") (name "~{T_SINGLE_UNIT}") (class "Default")
      (node (ref "M916_14") (pin "T2") (pinfunction "P$2_T2") (pintype "bidirectional"))
      (node (ref "M916_8") (pin "K2") (pinfunction "P$2_K2") (pintype "bidirectional"))
    )
    (net (code "641") (name "~{T_STOP}") (class "Default")
      (node (ref "M916_16") (pin "E2") (pinfunction "P$2_E2") (pintype "bidirectional"))
      (node (ref "M916_7") (pin "E1") (pinfunction "P$2_E1") (pintype "bidirectional"))
      (node (ref "M916_8") (pin "D2") (pinfunction "P$2_D2") (pintype "bidirectional"))
    )
    (net (code "642") (name "~{T_TRK}") (class "Default")
      (node (ref "IC61") (pin "10") (pinfunction "I1_10") (pintype "input"))
      (node (ref "M916_3") (pin "V2") (pinfunction "P$2_V2") (pintype "bidirectional"))
    )
    (net (code "643") (name "~{T_WRITE_OK}") (class "Default")
      (node (ref "M916_16") (pin "L2") (pinfunction "P$2_L2") (pintype "bidirectional"))
      (node (ref "M916_6") (pin "H2") (pinfunction "P$2_H2") (pintype "bidirectional"))
      (node (ref "M916_8") (pin "L2") (pinfunction "P$2_L2") (pintype "bidirectional"))
    )
    (net (code "644") (name "~{U+M_DY}") (class "Default")
      (node (ref "IC108") (pin "1") (pinfunction "I0_1") (pintype "input"))
      (node (ref "IC110") (pin "13") (pinfunction "I2_13") (pintype "input"))
      (node (ref "M916_20") (pin "E2") (pinfunction "P$2_E2") (pintype "bidirectional"))
      (node (ref "M916_20") (pin "N1") (pinfunction "P$2_N1") (pintype "bidirectional"))
    )
    (net (code "645") (name "~{USR_00}") (class "Default")
      (node (ref "IC31") (pin "2") (pinfunction "I0_2") (pintype "input"))
      (node (ref "IC56") (pin "13") (pinfunction "~{Q}_13") (pintype "output"))
    )
    (net (code "646") (name "~{USR_01}") (class "Default")
      (node (ref "IC31") (pin "5") (pinfunction "I0_5") (pintype "input"))
      (node (ref "IC56") (pin "8") (pinfunction "~{Q}_8") (pintype "output"))
    )
    (net (code "647") (name "~{USR_02}") (class "Default")
      (node (ref "IC31") (pin "8") (pinfunction "I0_8") (pintype "input"))
      (node (ref "IC57") (pin "13") (pinfunction "~{Q}_13") (pintype "output"))
    )
    (net (code "648") (name "~{UTS}") (class "Default")
      (node (ref "IC109") (pin "11") (pinfunction "I2_11") (pintype "input"))
      (node (ref "IC115") (pin "9") (pinfunction "Q_9") (pintype "output"))
      (node (ref "IC119") (pin "1") (pinfunction "I0_1") (pintype "input"))
      (node (ref "IC120") (pin "1") (pinfunction "I0_1") (pintype "input"))
      (node (ref "IC120") (pin "2") (pinfunction "I1_2") (pintype "input"))
      (node (ref "IC120") (pin "4") (pinfunction "I2_4") (pintype "input"))
      (node (ref "IC120") (pin "5") (pinfunction "I3_5") (pintype "input"))
      (node (ref "IC67") (pin "10") (pinfunction "I1_10") (pintype "input"))
      (node (ref "IC67") (pin "12") (pinfunction "I2_12") (pintype "input"))
      (node (ref "IC67") (pin "13") (pinfunction "I3_13") (pintype "input"))
      (node (ref "IC67") (pin "9") (pinfunction "I0_9") (pintype "input"))
    )
    (net (code "649") (name "~{W-INH}") (class "Default")
      (node (ref "IC68") (pin "2") (pinfunction "I1_2") (pintype "input"))
      (node (ref "IC7") (pin "9") (pinfunction "Q_9") (pintype "output"))
      (node (ref "IC70") (pin "10") (pinfunction "I1_10") (pintype "input"))
    )
    (net (code "650") (name "~{WB00}") (class "Default")
      (node (ref "IC103") (pin "5") (pinfunction "2D_5") (pintype "input"))
      (node (ref "IC114") (pin "5") (pinfunction "Q_5") (pintype "output"))
      (node (ref "M916_12") (pin "P2") (pinfunction "P$2_P2") (pintype "bidirectional"))
      (node (ref "M916_5") (pin "P2") (pinfunction "P$2_P2") (pintype "bidirectional"))
    )
    (net (code "651") (name "~{WB01}") (class "Default")
      (node (ref "IC105") (pin "10") (pinfunction "1E_10") (pintype "input"))
      (node (ref "IC114") (pin "9") (pinfunction "Q_9") (pintype "output"))
      (node (ref "M916_13") (pin "P2") (pinfunction "P$2_P2") (pintype "bidirectional"))
    )
    (net (code "652") (name "~{WB02}") (class "Default")
      (node (ref "IC104") (pin "5") (pinfunction "2D_5") (pintype "input"))
      (node (ref "IC115") (pin "5") (pinfunction "Q_5") (pintype "output"))
      (node (ref "M916_4") (pin "P2") (pinfunction "P$2_P2") (pintype "bidirectional"))
    )
    (net (code "653") (name "~{WC0}") (class "Default")
      (node (ref "IC138") (pin "10") (pinfunction "PRE_10") (pintype "input"))
      (node (ref "IC93") (pin "8") (pinfunction "O_8") (pintype "output"))
    )
    (net (code "654") (name "~{WC}") (class "Default")
      (node (ref "IC110") (pin "3") (pinfunction "I0_3") (pintype "input"))
      (node (ref "IC138") (pin "2") (pinfunction "D_2") (pintype "input"))
      (node (ref "IC138") (pin "8") (pinfunction "~{Q}_8") (pintype "output"))
      (node (ref "IC71") (pin "12") (pinfunction "I2_12") (pintype "input"))
    )
    (net (code "655") (name "~{WRITE_ALL}") (class "Default")
      (node (ref "IC125") (pin "6") (pinfunction "5_6") (pintype "output"))
      (node (ref "IC126") (pin "5") (pinfunction "I_5") (pintype "input"))
    )
    (net (code "656") (name "~{WRITE_DATA}") (class "Default")
      (node (ref "IC125") (pin "5") (pinfunction "4_5") (pintype "output"))
      (node (ref "IC126") (pin "3") (pinfunction "I_3") (pintype "input"))
      (node (ref "IC60") (pin "10") (pinfunction "I1_10") (pintype "input"))
    )
    (net (code "657") (name "~{WRITE_OK}") (class "Default")
      (node (ref "IC11") (pin "13") (pinfunction "I1_13") (pintype "input"))
      (node (ref "IC123") (pin "4") (pinfunction "O_4") (pintype "output"))
    )
    (net (code "658") (name "~{WRTM}") (class "Default")
      (node (ref "IC104") (pin "9") (pinfunction "1D_9") (pintype "input"))
      (node (ref "IC125") (pin "7") (pinfunction "6_7") (pintype "output"))
      (node (ref "IC126") (pin "9") (pinfunction "I_9") (pintype "input"))
      (node (ref "IC60") (pin "1") (pinfunction "I0_1") (pintype "input"))
    )
    (net (code "659") (name "~{WR_EN}") (class "Default")
      (node (ref "IC106") (pin "9") (pinfunction "I0_9") (pintype "input"))
      (node (ref "IC109") (pin "9") (pinfunction "I0_9") (pintype "input"))
      (node (ref "IC116") (pin "5") (pinfunction "Q_5") (pintype "output"))
      (node (ref "IC117") (pin "9") (pinfunction "I0_9") (pintype "input"))
      (node (ref "IC118") (pin "1") (pinfunction "I0_1") (pintype "input"))
      (node (ref "IC2") (pin "10") (pinfunction "I1_10") (pintype "input"))
    )
    (net (code "660") (name "~{XSAD}") (class "Default")
      (node (ref "IC14") (pin "13") (pinfunction "I_13") (pintype "input"))
      (node (ref "M916_19") (pin "L2") (pinfunction "P$2_L2") (pintype "bidirectional"))
    )
    (net (code "661") (name "~{XSTA}") (class "Default")
      (node (ref "IC61") (pin "2") (pinfunction "I1_2") (pintype "input"))
      (node (ref "IC87") (pin "11") (pinfunction "O_11") (pintype "output"))
      (node (ref "IC88") (pin "3") (pinfunction "I_3") (pintype "input"))
      (node (ref "M916_19") (pin "H2") (pinfunction "P$2_H2") (pintype "bidirectional"))
      (node (ref "M916_19") (pin "J2") (pinfunction "P$2_J2") (pintype "bidirectional"))
      (node (ref "M916_19") (pin "K2") (pinfunction "P$2_K2") (pintype "bidirectional"))
      (node (ref "M916_20") (pin "K2") (pinfunction "P$2_K2") (pintype "bidirectional"))
      (node (ref "M916_20") (pin "L2") (pinfunction "P$2_L2") (pintype "bidirectional"))
      (node (ref "M916_22") (pin "M2") (pinfunction "P$2_M2") (pintype "bidirectional"))
      (node (ref "M916_22") (pin "N2") (pinfunction "P$2_N2") (pintype "bidirectional"))
    )
  )
)
